# BaseBoard5.net
KiCad netlist of a schematic drawn in EAGLE
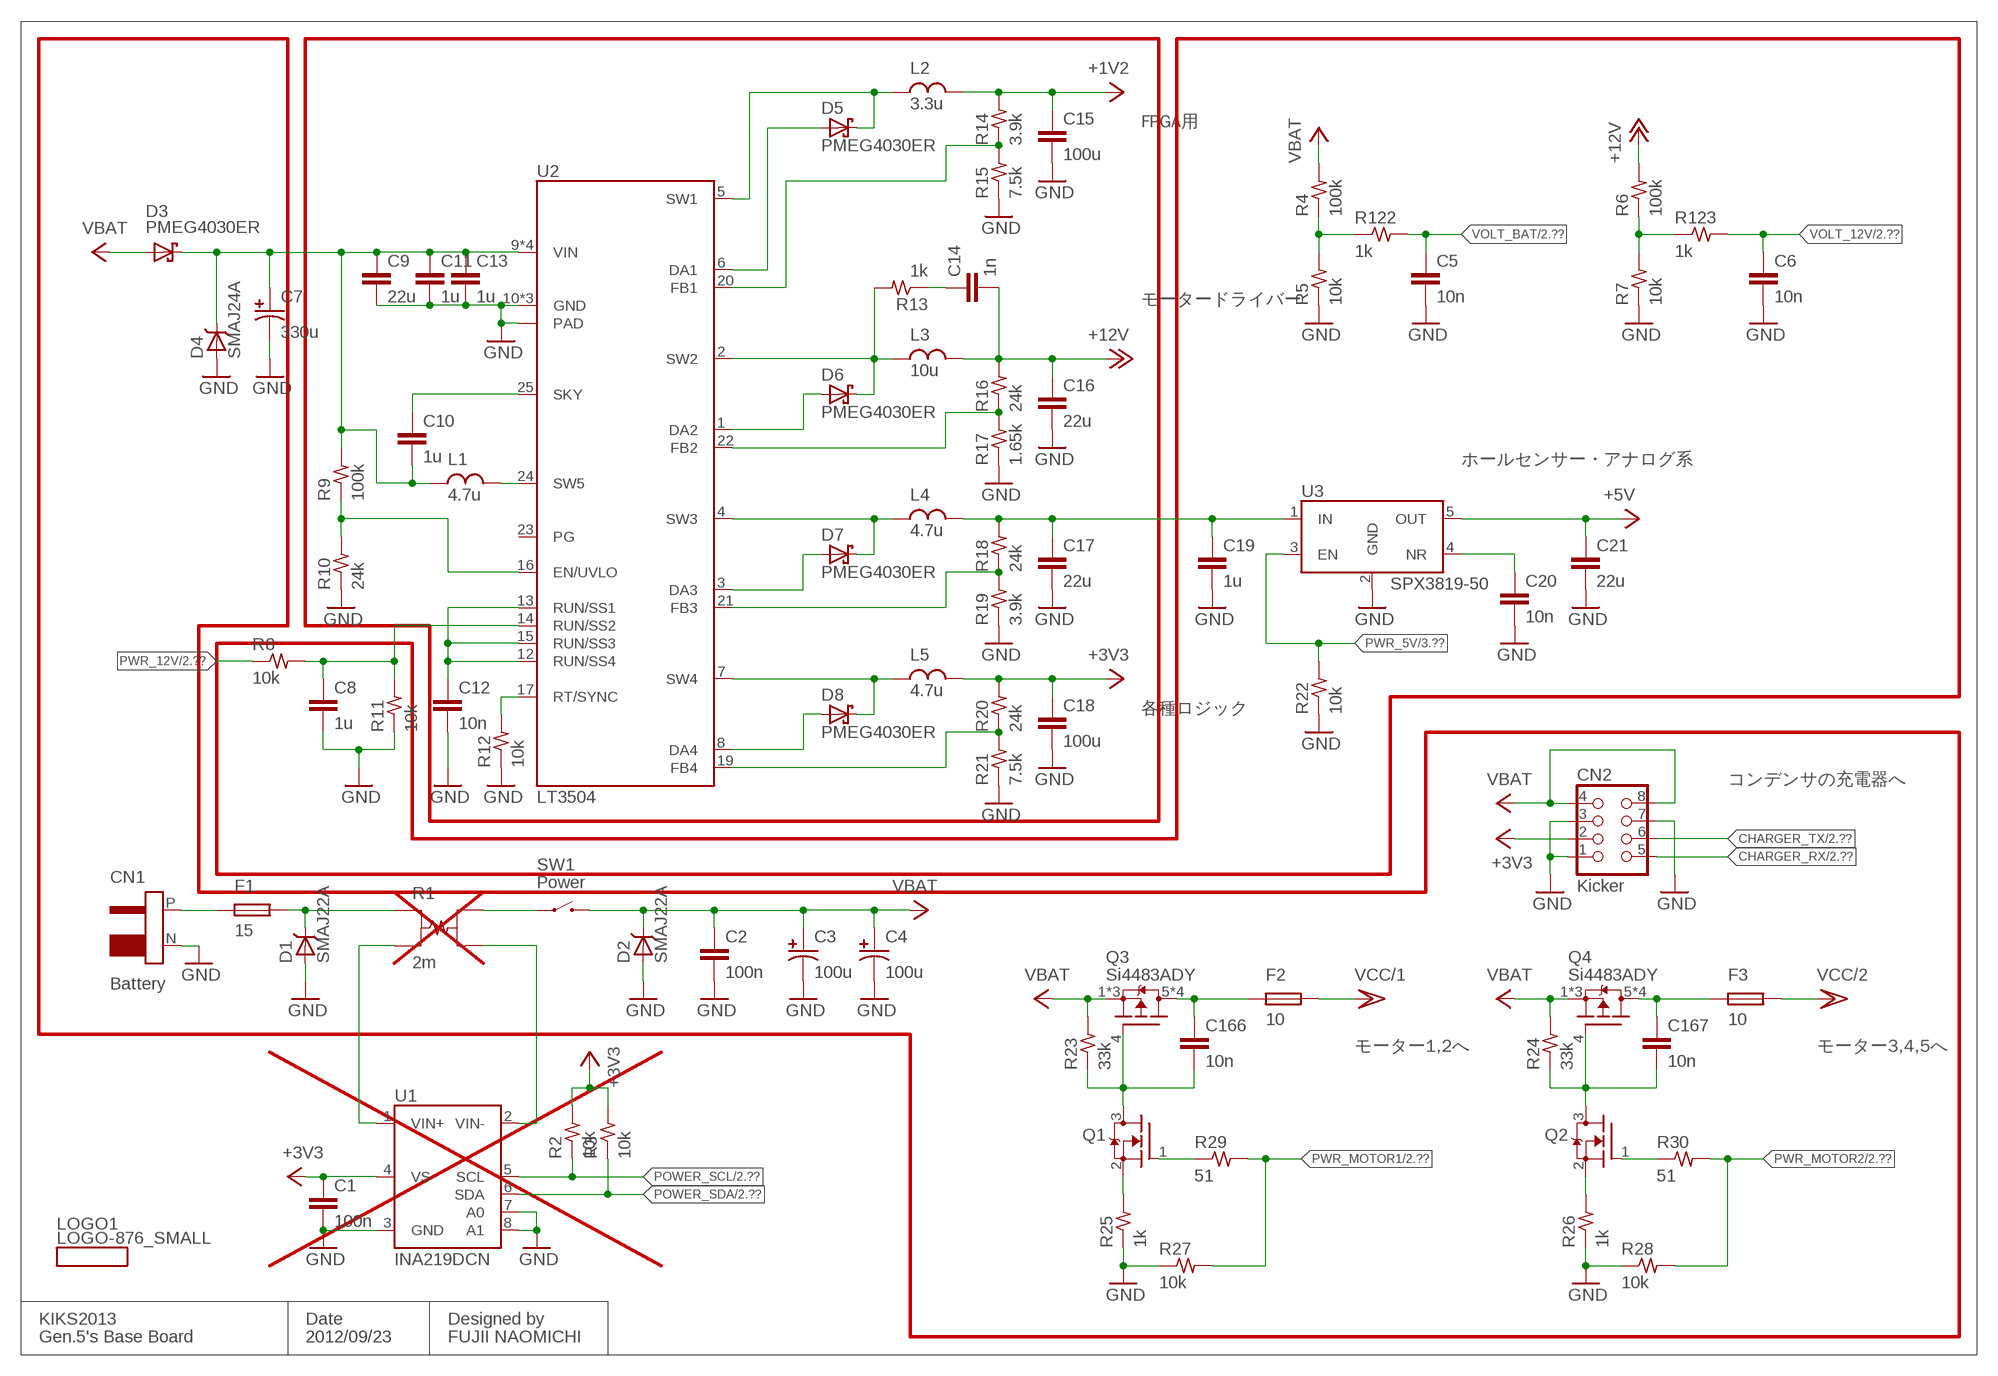
[diagram p0: schematic, sheet 1]
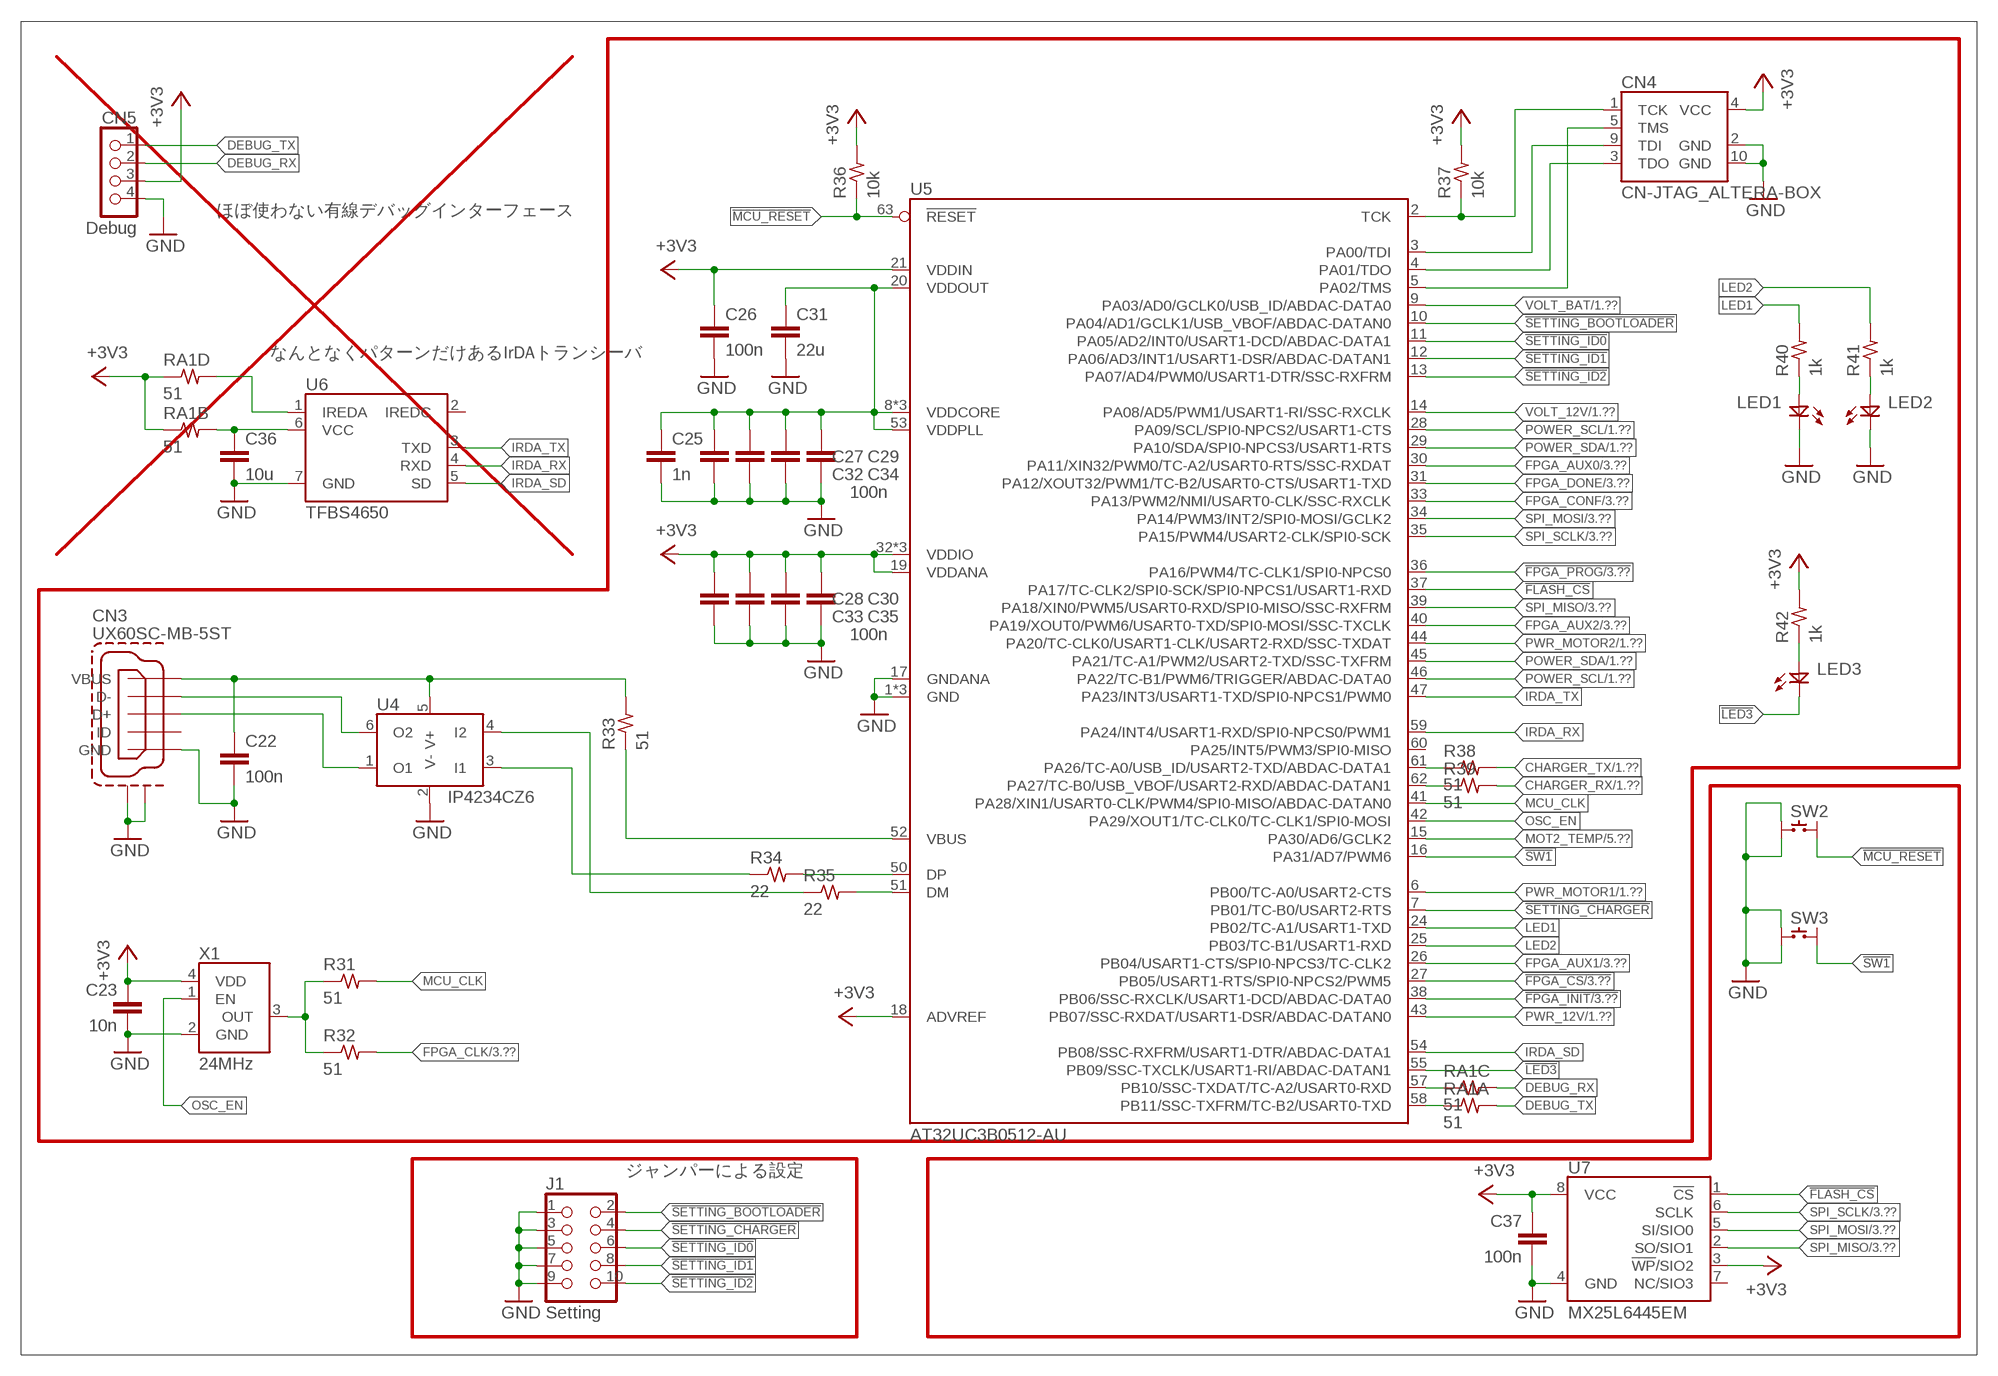
[diagram p1: schematic, sheet 2]
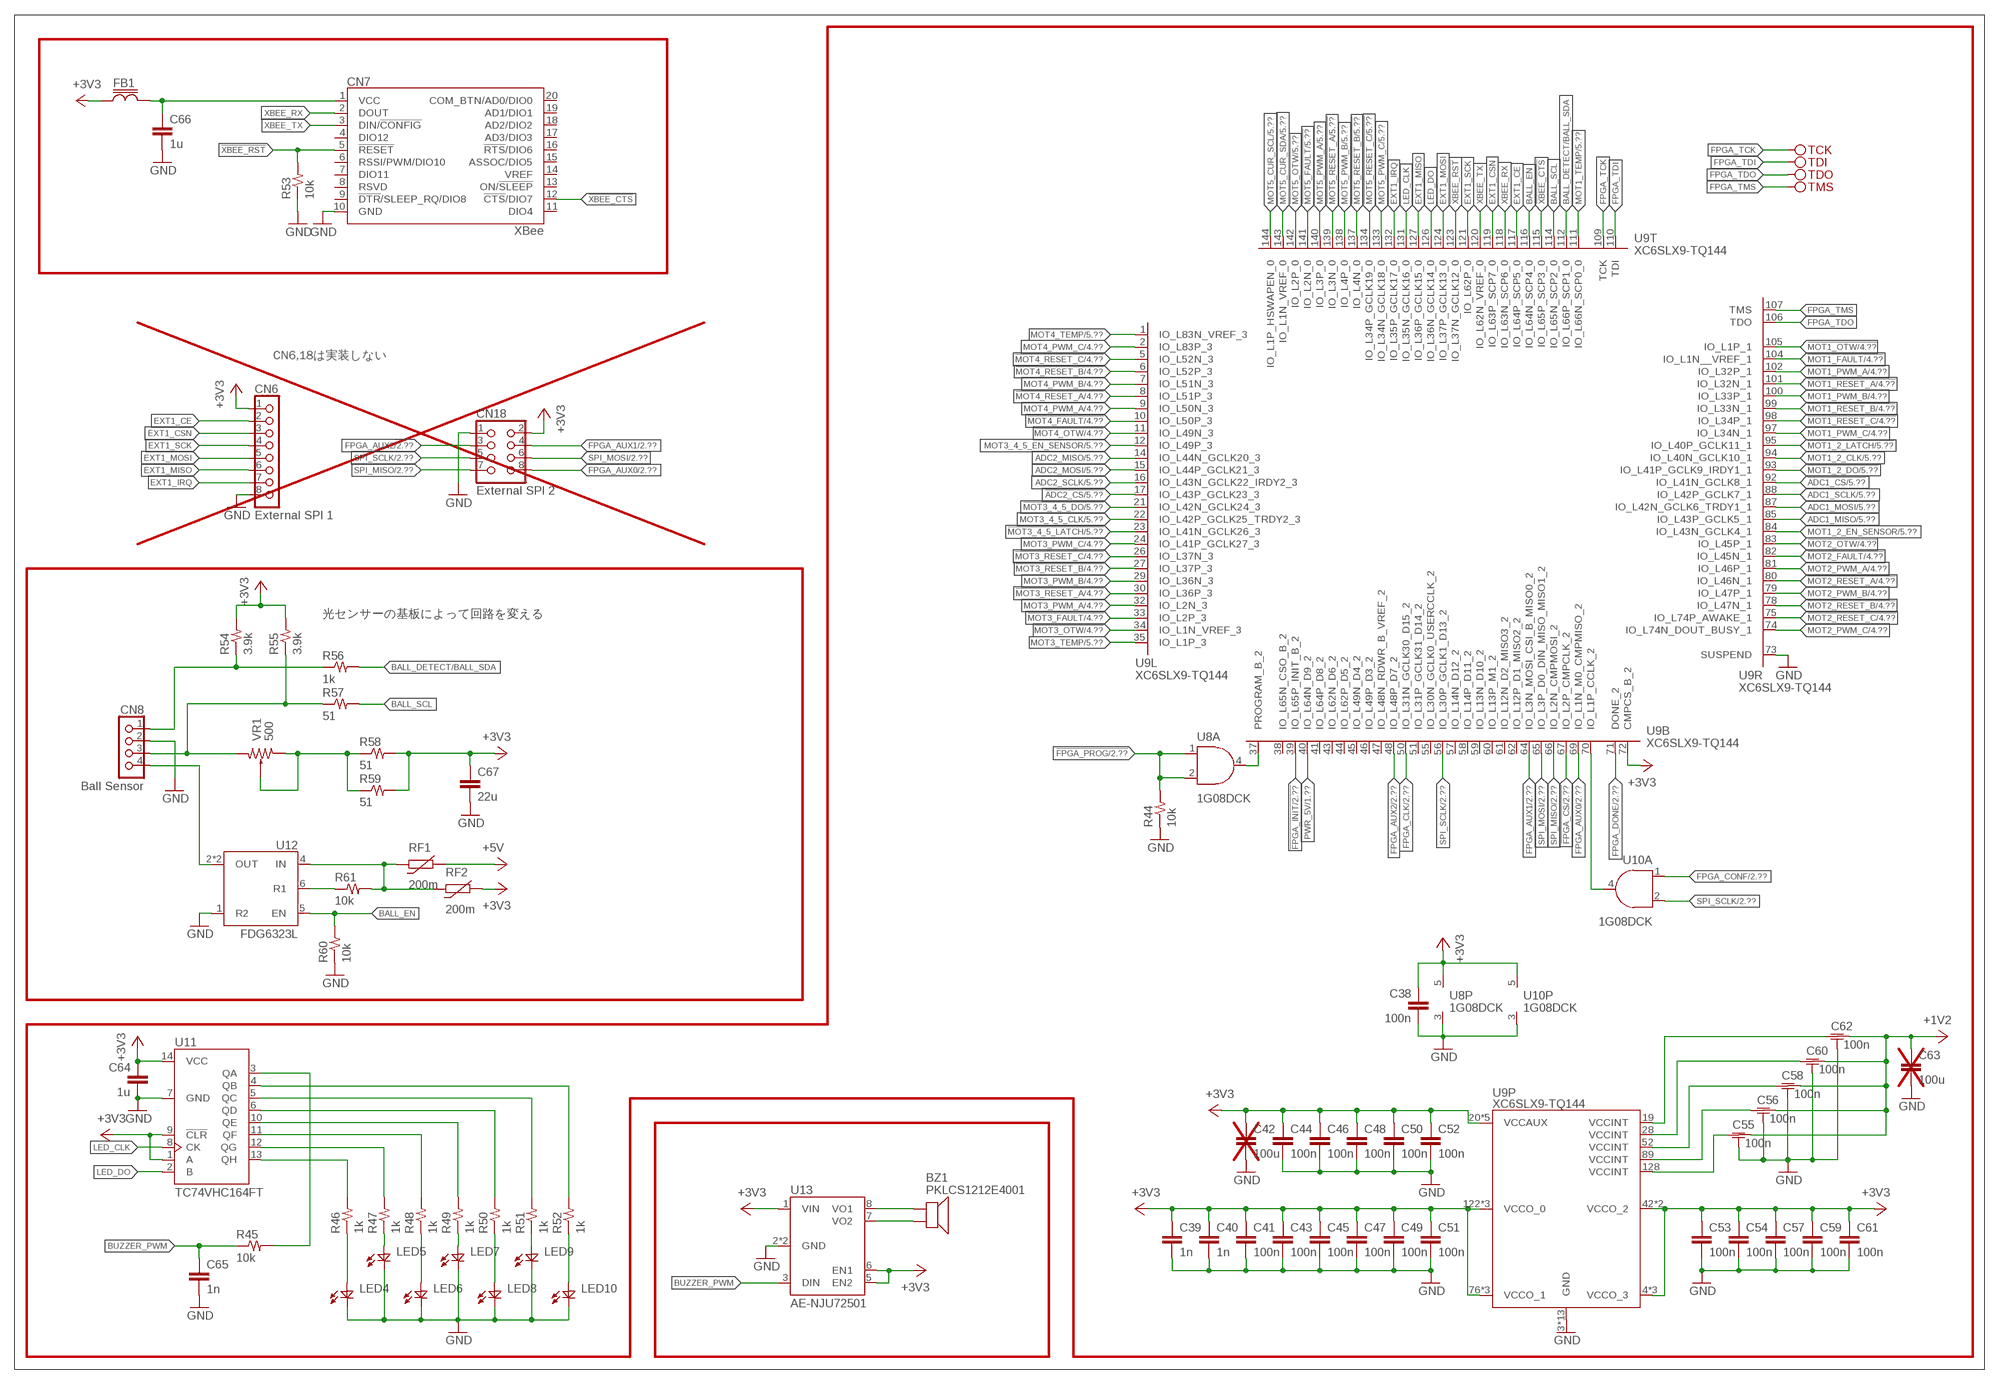
[diagram p2: schematic, sheet 3]
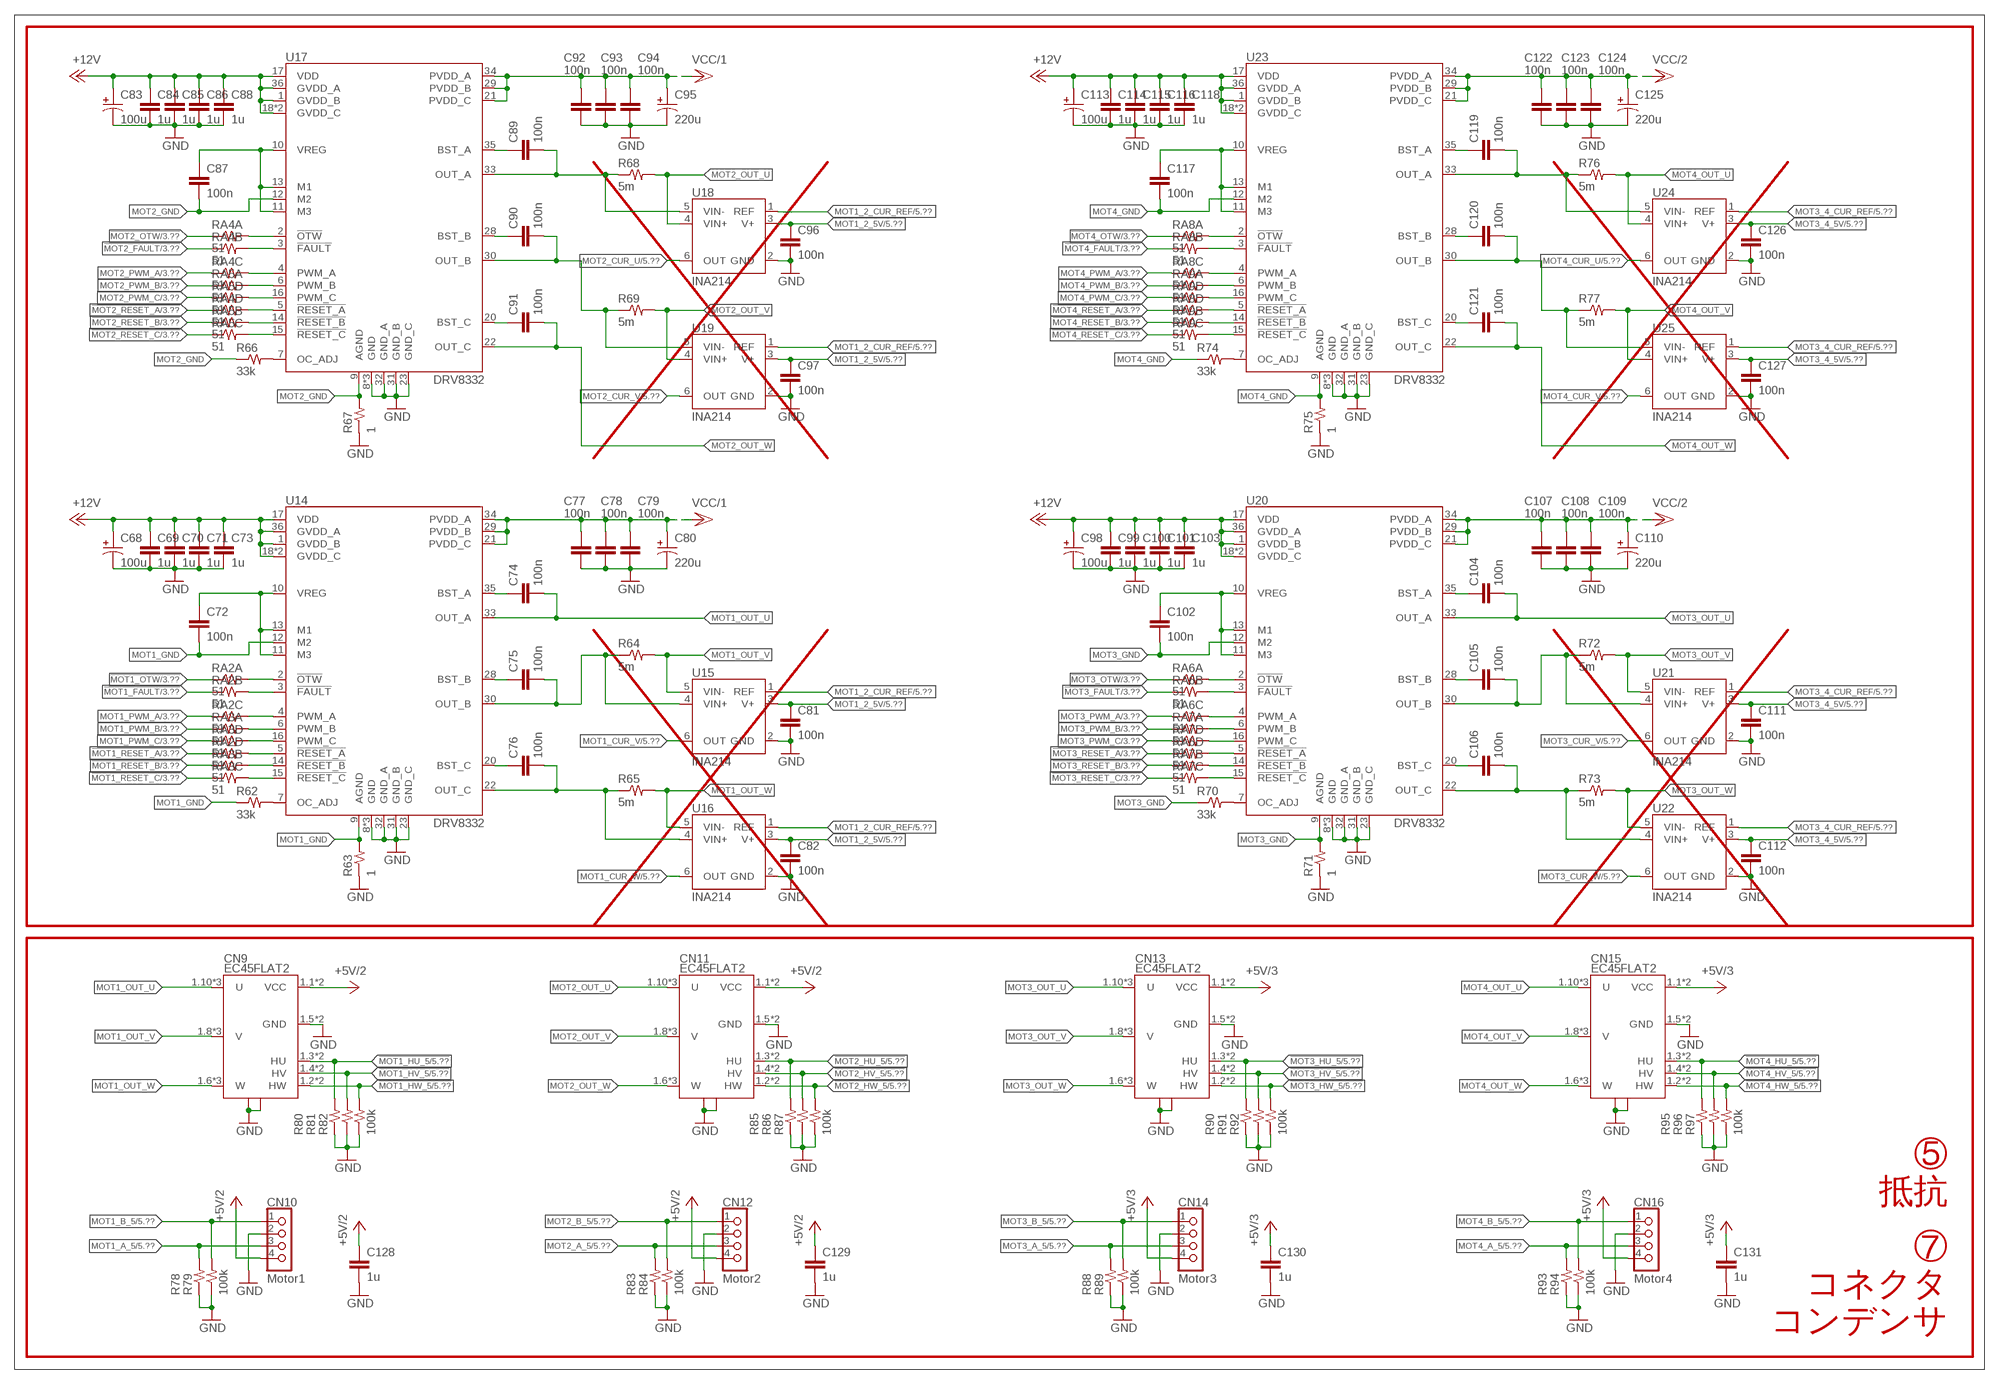
[diagram p3: schematic, sheet 4]
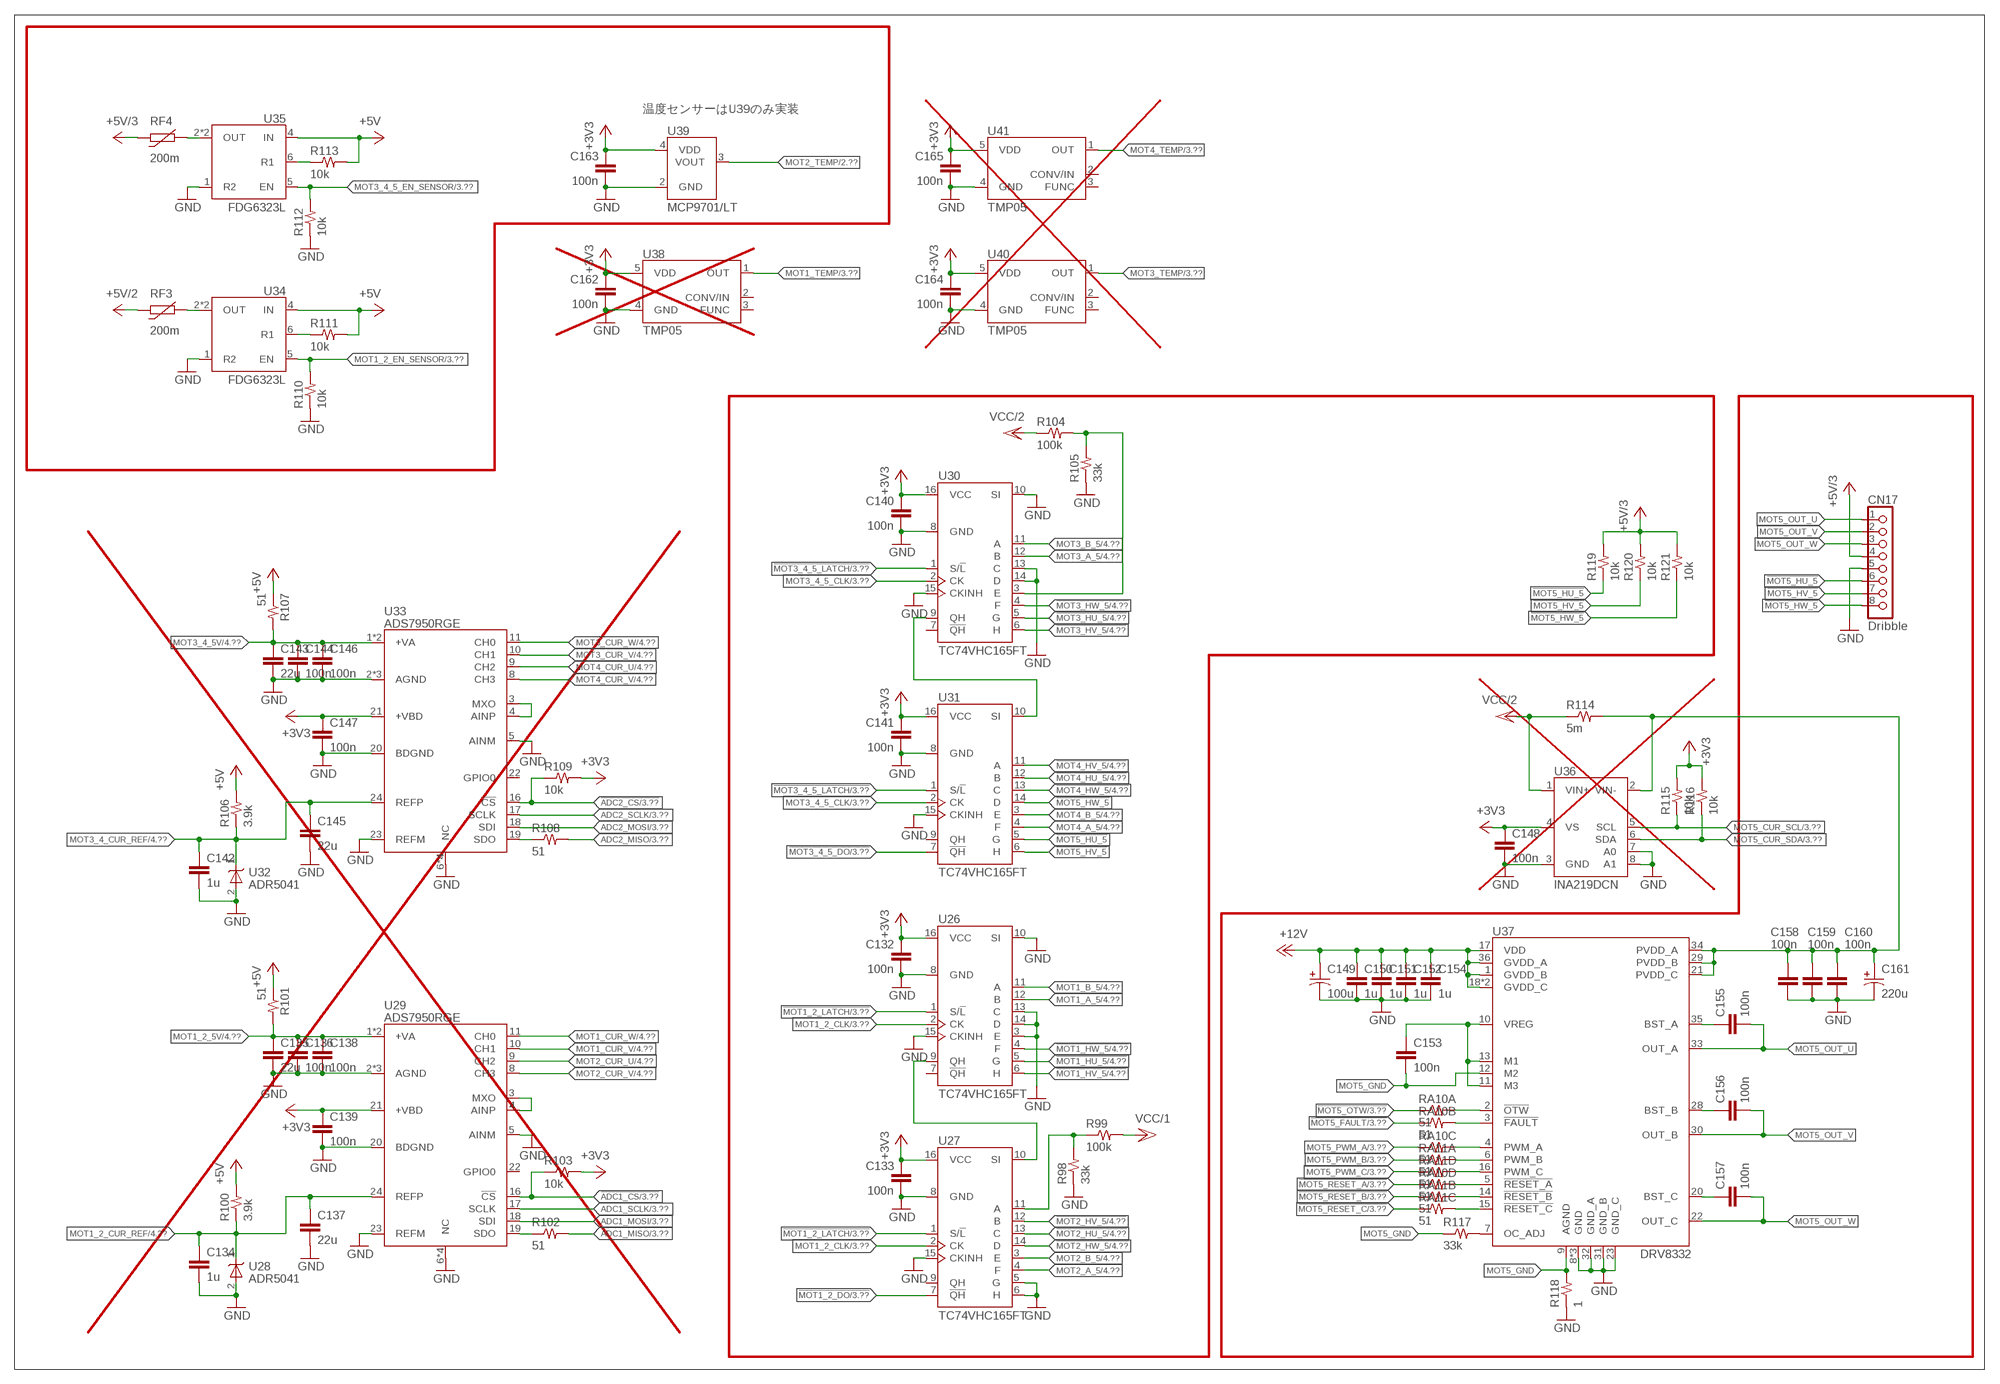
[diagram p4: schematic, sheet 5]

(export (version "E")
  (design (tool "Eeschema 10.0.6"))
  (components
    (comp (ref "C1")
      (value "100n")
      (footprint "eagle-import:1005")
      (libsource (lib "eagle-import") (part "C1005"))
    )
    (comp (ref "C2")
      (value "100n")
      (footprint "eagle-import:1608")
      (libsource (lib "eagle-import") (part "C1608"))
    )
    (comp (ref "C3")
      (value "100u")
      (footprint "eagle-import:ES-6.3")
      (libsource (lib "eagle-import") (part "CPOLS-6.3"))
    )
    (comp (ref "C4")
      (value "100u")
      (footprint "eagle-import:ES-6.3")
      (libsource (lib "eagle-import") (part "CPOLS-6.3"))
    )
    (comp (ref "C5")
      (value "10n")
      (footprint "eagle-import:1005")
      (libsource (lib "eagle-import") (part "C1005"))
    )
    (comp (ref "C6")
      (value "10n")
      (footprint "eagle-import:1005")
      (libsource (lib "eagle-import") (part "C1005"))
    )
    (comp (ref "C7")
      (value "330u")
      (footprint "eagle-import:ES2-8")
      (libsource (lib "eagle-import") (part "CPOLS2-8"))
    )
    (comp (ref "C8")
      (value "1u")
      (footprint "eagle-import:1005")
      (libsource (lib "eagle-import") (part "C1005"))
    )
    (comp (ref "C9")
      (value "22u")
      (footprint "eagle-import:3225")
      (libsource (lib "eagle-import") (part "C3225"))
    )
    (comp (ref "C10")
      (value "1u")
      (footprint "eagle-import:1608")
      (libsource (lib "eagle-import") (part "C1608"))
    )
    (comp (ref "C11")
      (value "1u")
      (footprint "eagle-import:1608")
      (libsource (lib "eagle-import") (part "C1608"))
    )
    (comp (ref "C12")
      (value "10n")
      (footprint "eagle-import:1005")
      (libsource (lib "eagle-import") (part "C1005"))
    )
    (comp (ref "C13")
      (value "1u")
      (footprint "eagle-import:1608")
      (libsource (lib "eagle-import") (part "C1608"))
    )
    (comp (ref "C14")
      (value "1n")
      (footprint "eagle-import:1005")
      (libsource (lib "eagle-import") (part "C1005"))
    )
    (comp (ref "C15")
      (value "100u")
      (footprint "eagle-import:3225")
      (libsource (lib "eagle-import") (part "C3225"))
    )
    (comp (ref "C16")
      (value "22u")
      (footprint "eagle-import:3225")
      (libsource (lib "eagle-import") (part "C3225"))
    )
    (comp (ref "C17")
      (value "22u")
      (footprint "eagle-import:3216")
      (libsource (lib "eagle-import") (part "C3216"))
    )
    (comp (ref "C18")
      (value "100u")
      (footprint "eagle-import:3225")
      (libsource (lib "eagle-import") (part "C3225"))
    )
    (comp (ref "C19")
      (value "1u")
      (footprint "eagle-import:1005")
      (libsource (lib "eagle-import") (part "C1005"))
    )
    (comp (ref "C20")
      (value "10n")
      (footprint "eagle-import:1005")
      (libsource (lib "eagle-import") (part "C1005"))
    )
    (comp (ref "C21")
      (value "22u")
      (footprint "eagle-import:3216")
      (libsource (lib "eagle-import") (part "C3216"))
    )
    (comp (ref "C166")
      (value "10n")
      (footprint "eagle-import:1005")
      (libsource (lib "eagle-import") (part "C1005"))
    )
    (comp (ref "C167")
      (value "10n")
      (footprint "eagle-import:1005")
      (libsource (lib "eagle-import") (part "C1005"))
    )
    (comp (ref "CN1")
      (value "Battery")
      (footprint "eagle-import:T-CON")
      (libsource (lib "eagle-import") (part "T-CON"))
    )
    (comp (ref "CN2")
      (value "Kicker")
      (footprint "eagle-import:43045-0800")
      (libsource (lib "eagle-import") (part "43045-0800"))
    )
    (comp (ref "D1")
      (value "SMAJ22A")
      (footprint "eagle-import:DO-214AC")
      (libsource (lib "eagle-import") (part "ZENER-DO-214AC"))
    )
    (comp (ref "D2")
      (value "SMAJ22A")
      (footprint "eagle-import:DO-214AC")
      (libsource (lib "eagle-import") (part "ZENER-DO-214AC"))
    )
    (comp (ref "D3")
      (value "PMEG4030ER")
      (footprint "eagle-import:SOD123W")
      (libsource (lib "eagle-import") (part "SBD-SDO123W"))
    )
    (comp (ref "D4")
      (value "SMAJ24A")
      (footprint "eagle-import:DO-214AC")
      (libsource (lib "eagle-import") (part "ZENER-DO-214AC"))
    )
    (comp (ref "D5")
      (value "PMEG4030ER")
      (footprint "eagle-import:SOD123W")
      (libsource (lib "eagle-import") (part "SBD-SDO123W"))
    )
    (comp (ref "D6")
      (value "PMEG4030ER")
      (footprint "eagle-import:SOD123W")
      (libsource (lib "eagle-import") (part "SBD-SDO123W"))
    )
    (comp (ref "D7")
      (value "PMEG4030ER")
      (footprint "eagle-import:SOD123W")
      (libsource (lib "eagle-import") (part "SBD-SDO123W"))
    )
    (comp (ref "D8")
      (value "PMEG4030ER")
      (footprint "eagle-import:SOD123W")
      (libsource (lib "eagle-import") (part "SBD-SDO123W"))
    )
    (comp (ref "F1")
      (value "15")
      (footprint "eagle-import:3216")
      (libsource (lib "eagle-import") (part "F3216"))
    )
    (comp (ref "F2")
      (value "10")
      (footprint "eagle-import:3216")
      (libsource (lib "eagle-import") (part "F3216"))
    )
    (comp (ref "F3")
      (value "10")
      (footprint "eagle-import:3216")
      (libsource (lib "eagle-import") (part "F3216"))
    )
    (comp (ref "L1")
      (value "4.7u")
      (footprint "eagle-import:L2520")
      (libsource (lib "eagle-import") (part "L2520"))
    )
    (comp (ref "L2")
      (value "3.3u")
      (footprint "eagle-import:L2520")
      (libsource (lib "eagle-import") (part "L2520"))
    )
    (comp (ref "L3")
      (value "10u")
      (footprint "eagle-import:L4040")
      (libsource (lib "eagle-import") (part "L40"))
    )
    (comp (ref "L4")
      (value "4.7u")
      (footprint "eagle-import:L2520")
      (libsource (lib "eagle-import") (part "L2520"))
    )
    (comp (ref "L5")
      (value "4.7u")
      (footprint "eagle-import:L2520")
      (libsource (lib "eagle-import") (part "L2520"))
    )
    (comp (ref "LOGO1")
      (value "LOGO-876_SMALL")
      (footprint "eagle-import:LOGO-876_SMALL")
      (libsource (lib "eagle-import") (part "LOGO-876_SMALL"))
    )
    (comp (ref "Q1")
      (value "MOS-N-SOT23")
      (footprint "eagle-import:SOT23-3")
      (libsource (lib "eagle-import") (part "MOS-N-SOT23"))
    )
    (comp (ref "Q2")
      (value "MOS-N-SOT23")
      (footprint "eagle-import:SOT23-3")
      (libsource (lib "eagle-import") (part "MOS-N-SOT23"))
    )
    (comp (ref "Q3")
      (value "Si4483ADY")
      (footprint "eagle-import:SOP8")
      (libsource (lib "eagle-import") (part "MOS-P-SOP8"))
    )
    (comp (ref "Q4")
      (value "Si4483ADY")
      (footprint "eagle-import:SOP8")
      (libsource (lib "eagle-import") (part "MOS-P-SOP8"))
    )
    (comp (ref "R1")
      (value "2m")
      (footprint "eagle-import:FC4L")
      (libsource (lib "eagle-import") (part "FC4L"))
    )
    (comp (ref "R2")
      (value "10k")
      (footprint "eagle-import:1005")
      (libsource (lib "eagle-import") (part "R1005"))
    )
    (comp (ref "R3")
      (value "10k")
      (footprint "eagle-import:1005")
      (libsource (lib "eagle-import") (part "R1005"))
    )
    (comp (ref "R4")
      (value "100k")
      (footprint "eagle-import:1608")
      (libsource (lib "eagle-import") (part "R1608"))
    )
    (comp (ref "R5")
      (value "10k")
      (footprint "eagle-import:1608")
      (libsource (lib "eagle-import") (part "R1608"))
    )
    (comp (ref "R6")
      (value "100k")
      (footprint "eagle-import:1608")
      (libsource (lib "eagle-import") (part "R1608"))
    )
    (comp (ref "R7")
      (value "10k")
      (footprint "eagle-import:1608")
      (libsource (lib "eagle-import") (part "R1608"))
    )
    (comp (ref "R8")
      (value "10k")
      (footprint "eagle-import:1005")
      (libsource (lib "eagle-import") (part "R1005"))
    )
    (comp (ref "R9")
      (value "100k")
      (footprint "eagle-import:1608")
      (libsource (lib "eagle-import") (part "R1608"))
    )
    (comp (ref "R10")
      (value "24k")
      (footprint "eagle-import:1608")
      (libsource (lib "eagle-import") (part "R1608"))
    )
    (comp (ref "R11")
      (value "10k")
      (footprint "eagle-import:1005")
      (libsource (lib "eagle-import") (part "R1005"))
    )
    (comp (ref "R12")
      (value "10k")
      (footprint "eagle-import:1005")
      (libsource (lib "eagle-import") (part "R1005"))
    )
    (comp (ref "R13")
      (value "1k")
      (footprint "eagle-import:1005")
      (libsource (lib "eagle-import") (part "R1005"))
    )
    (comp (ref "R14")
      (value "3.9k")
      (footprint "eagle-import:1608")
      (libsource (lib "eagle-import") (part "R1608"))
    )
    (comp (ref "R15")
      (value "7.5k")
      (footprint "eagle-import:1608")
      (libsource (lib "eagle-import") (part "R1608"))
    )
    (comp (ref "R16")
      (value "24k")
      (footprint "eagle-import:1608")
      (libsource (lib "eagle-import") (part "R1608"))
    )
    (comp (ref "R17")
      (value "1.65k")
      (footprint "eagle-import:1608")
      (libsource (lib "eagle-import") (part "R1608"))
    )
    (comp (ref "R18")
      (value "24k")
      (footprint "eagle-import:1608")
      (libsource (lib "eagle-import") (part "R1608"))
    )
    (comp (ref "R19")
      (value "3.9k")
      (footprint "eagle-import:1608")
      (libsource (lib "eagle-import") (part "R1608"))
    )
    (comp (ref "R20")
      (value "24k")
      (footprint "eagle-import:1608")
      (libsource (lib "eagle-import") (part "R1608"))
    )
    (comp (ref "R21")
      (value "7.5k")
      (footprint "eagle-import:1608")
      (libsource (lib "eagle-import") (part "R1608"))
    )
    (comp (ref "R22")
      (value "10k")
      (footprint "eagle-import:1005")
      (libsource (lib "eagle-import") (part "R1005"))
    )
    (comp (ref "R23")
      (value "33k")
      (footprint "eagle-import:1005")
      (libsource (lib "eagle-import") (part "R1005"))
    )
    (comp (ref "R24")
      (value "33k")
      (footprint "eagle-import:1005")
      (libsource (lib "eagle-import") (part "R1005"))
    )
    (comp (ref "R25")
      (value "1k")
      (footprint "eagle-import:1005")
      (libsource (lib "eagle-import") (part "R1005"))
    )
    (comp (ref "R26")
      (value "1k")
      (footprint "eagle-import:1005")
      (libsource (lib "eagle-import") (part "R1005"))
    )
    (comp (ref "R27")
      (value "10k")
      (footprint "eagle-import:1005")
      (libsource (lib "eagle-import") (part "R1005"))
    )
    (comp (ref "R28")
      (value "10k")
      (footprint "eagle-import:1005")
      (libsource (lib "eagle-import") (part "R1005"))
    )
    (comp (ref "R29")
      (value "51")
      (footprint "eagle-import:1005")
      (libsource (lib "eagle-import") (part "R1005"))
    )
    (comp (ref "R30")
      (value "51")
      (footprint "eagle-import:1005")
      (libsource (lib "eagle-import") (part "R1005"))
    )
    (comp (ref "R122")
      (value "1k")
      (footprint "eagle-import:1005")
      (libsource (lib "eagle-import") (part "R1005"))
    )
    (comp (ref "R123")
      (value "1k")
      (footprint "eagle-import:1005")
      (libsource (lib "eagle-import") (part "R1005"))
    )
    (comp (ref "SW1")
      (value "Power")
      (footprint "eagle-import:SLE6_10A4")
      (libsource (lib "eagle-import") (part "SLEA46"))
    )
    (comp (ref "U1")
      (value "INA219DCN")
      (footprint "eagle-import:SOT23-8")
      (libsource (lib "eagle-import") (part "INA219DCN"))
    )
    (comp (ref "U2")
      (value "LT3504")
      (footprint "eagle-import:QFN28-0.5-PAD")
      (libsource (lib "eagle-import") (part "LT3504"))
    )
    (comp (ref "U3")
      (value "SPX3819-50")
      (footprint "eagle-import:SOT23-5")
      (libsource (lib "eagle-import") (part "SPX3819-50"))
    )
    (comp (ref "C22")
      (value "100n")
      (footprint "eagle-import:1005")
      (libsource (lib "eagle-import") (part "C1005"))
    )
    (comp (ref "C23")
      (value "10n")
      (footprint "eagle-import:1005")
      (libsource (lib "eagle-import") (part "C1005"))
    )
    (comp (ref "C25")
      (value "1n")
      (footprint "eagle-import:1005")
      (libsource (lib "eagle-import") (part "C1005"))
    )
    (comp (ref "C26")
      (value "100n")
      (footprint "eagle-import:1005")
      (libsource (lib "eagle-import") (part "C1005"))
    )
    (comp (ref "C27")
      (value "100n")
      (footprint "eagle-import:1005")
      (libsource (lib "eagle-import") (part "C1005"))
    )
    (comp (ref "C28")
      (value "100n")
      (footprint "eagle-import:1005")
      (libsource (lib "eagle-import") (part "C1005"))
    )
    (comp (ref "C29")
      (value "100n")
      (footprint "eagle-import:1005")
      (libsource (lib "eagle-import") (part "C1005"))
    )
    (comp (ref "C30")
      (value "100n")
      (footprint "eagle-import:1005")
      (libsource (lib "eagle-import") (part "C1005"))
    )
    (comp (ref "C31")
      (value "22u")
      (footprint "eagle-import:2012")
      (libsource (lib "eagle-import") (part "C2012"))
    )
    (comp (ref "C32")
      (value "100n")
      (footprint "eagle-import:1005")
      (libsource (lib "eagle-import") (part "C1005"))
    )
    (comp (ref "C33")
      (value "100n")
      (footprint "eagle-import:1005")
      (libsource (lib "eagle-import") (part "C1005"))
    )
    (comp (ref "C34")
      (value "100n")
      (footprint "eagle-import:1005")
      (libsource (lib "eagle-import") (part "C1005"))
    )
    (comp (ref "C35")
      (value "100n")
      (footprint "eagle-import:1005")
      (libsource (lib "eagle-import") (part "C1005"))
    )
    (comp (ref "C36")
      (value "10u")
      (footprint "eagle-import:1608")
      (libsource (lib "eagle-import") (part "C1608"))
    )
    (comp (ref "C37")
      (value "100n")
      (footprint "eagle-import:1005")
      (libsource (lib "eagle-import") (part "C1005"))
    )
    (comp (ref "CN3")
      (value "UX60SC-MB-5ST")
      (footprint "eagle-import:UX60SC-MB-5ST")
      (libsource (lib "eagle-import") (part "UX60SC-MB-5ST"))
    )
    (comp (ref "CN4")
      (value "CN-JTAG_ALTERA-BOX")
      (footprint "eagle-import:PIN2X5-BOX")
      (libsource (lib "eagle-import") (part "CN-JTAG_ALTERA-BOX"))
    )
    (comp (ref "CN5")
      (value "Debug")
      (footprint "eagle-import:70553-0003")
      (libsource (lib "eagle-import") (part "70553-0003"))
    )
    (comp (ref "J1")
      (value "Setting")
      (footprint "eagle-import:PIN2X5-2.0")
      (libsource (lib "eagle-import") (part "PIN2X5-2.0"))
    )
    (comp (ref "LED1")
      (value "LED1608")
      (footprint "eagle-import:1608")
      (libsource (lib "eagle-import") (part "LED1608"))
    )
    (comp (ref "LED2")
      (value "LED1608")
      (footprint "eagle-import:1608")
      (libsource (lib "eagle-import") (part "LED1608"))
    )
    (comp (ref "LED3")
      (value "LED1608")
      (footprint "eagle-import:1608")
      (libsource (lib "eagle-import") (part "LED1608"))
    )
    (comp (ref "R31")
      (value "51")
      (footprint "eagle-import:1005")
      (libsource (lib "eagle-import") (part "R1005"))
    )
    (comp (ref "R32")
      (value "51")
      (footprint "eagle-import:1005")
      (libsource (lib "eagle-import") (part "R1005"))
    )
    (comp (ref "R33")
      (value "51")
      (footprint "eagle-import:1005")
      (libsource (lib "eagle-import") (part "R1005"))
    )
    (comp (ref "R34")
      (value "22")
      (footprint "eagle-import:1005")
      (libsource (lib "eagle-import") (part "R1005"))
    )
    (comp (ref "R35")
      (value "22")
      (footprint "eagle-import:1005")
      (libsource (lib "eagle-import") (part "R1005"))
    )
    (comp (ref "R36")
      (value "10k")
      (footprint "eagle-import:1005")
      (libsource (lib "eagle-import") (part "R1005"))
    )
    (comp (ref "R37")
      (value "10k")
      (footprint "eagle-import:1005")
      (libsource (lib "eagle-import") (part "R1005"))
    )
    (comp (ref "R38")
      (value "51")
      (footprint "eagle-import:1005")
      (libsource (lib "eagle-import") (part "R1005"))
    )
    (comp (ref "R39")
      (value "51")
      (footprint "eagle-import:1005")
      (libsource (lib "eagle-import") (part "R1005"))
    )
    (comp (ref "R40")
      (value "1k")
      (footprint "eagle-import:1005")
      (libsource (lib "eagle-import") (part "R1005"))
    )
    (comp (ref "R41")
      (value "1k")
      (footprint "eagle-import:1005")
      (libsource (lib "eagle-import") (part "R1005"))
    )
    (comp (ref "R42")
      (value "1k")
      (footprint "eagle-import:1005")
      (libsource (lib "eagle-import") (part "R1005"))
    )
    (comp (ref "RA1")
      (value "51")
      (footprint "eagle-import:1005-A4")
      (libsource (lib "eagle-import") (part "RA4"))
    )
    (comp (ref "SW2")
      (value "EVQ-P2-RECTANGLE")
      (footprint "eagle-import:EVQ-P2_P9")
      (libsource (lib "eagle-import") (part "EVQ-?P2-RECTANGLE"))
    )
    (comp (ref "SW3")
      (value "EVQ-P2-RECTANGLE")
      (footprint "eagle-import:EVQ-P2_P9")
      (libsource (lib "eagle-import") (part "EVQ-?P2-RECTANGLE"))
    )
    (comp (ref "U4")
      (value "IP4234CZ6")
      (footprint "eagle-import:SOT23-6")
      (libsource (lib "eagle-import") (part "TPD2S017"))
    )
    (comp (ref "U5")
      (value "AT32UC3B0512-AU")
      (footprint "eagle-import:QFP64-0.5")
      (libsource (lib "eagle-import") (part "AT32UC3B0512-AU"))
    )
    (comp (ref "U6")
      (value "TFBS4650")
      (footprint "eagle-import:TFBS4650")
      (libsource (lib "eagle-import") (part "TFBS4650"))
    )
    (comp (ref "U7")
      (value "MX25L6445EM")
      (footprint "eagle-import:SOP8W")
      (libsource (lib "eagle-import") (part "MX25L6445EM"))
    )
    (comp (ref "X1")
      (value "24MHz")
      (footprint "eagle-import:OSC2520")
      (libsource (lib "eagle-import") (part "ASDMB"))
    )
    (comp (ref "C68")
      (value "100u")
      (footprint "eagle-import:E2.5-6.3")
      (libsource (lib "eagle-import") (part "CPOL2.5-6.3"))
    )
    (comp (ref "C69")
      (value "1u")
      (footprint "eagle-import:1608")
      (libsource (lib "eagle-import") (part "C1608"))
    )
    (comp (ref "C70")
      (value "1u")
      (footprint "eagle-import:1608")
      (libsource (lib "eagle-import") (part "C1608"))
    )
    (comp (ref "C71")
      (value "1u")
      (footprint "eagle-import:1608")
      (libsource (lib "eagle-import") (part "C1608"))
    )
    (comp (ref "C72")
      (value "100n")
      (footprint "eagle-import:1005")
      (libsource (lib "eagle-import") (part "C1005"))
    )
    (comp (ref "C73")
      (value "1u")
      (footprint "eagle-import:1608")
      (libsource (lib "eagle-import") (part "C1608"))
    )
    (comp (ref "C74")
      (value "100n")
      (footprint "eagle-import:1608")
      (libsource (lib "eagle-import") (part "C1608"))
    )
    (comp (ref "C75")
      (value "100n")
      (footprint "eagle-import:1608")
      (libsource (lib "eagle-import") (part "C1608"))
    )
    (comp (ref "C76")
      (value "100n")
      (footprint "eagle-import:1608")
      (libsource (lib "eagle-import") (part "C1608"))
    )
    (comp (ref "C77")
      (value "100n")
      (footprint "eagle-import:1608")
      (libsource (lib "eagle-import") (part "C1608"))
    )
    (comp (ref "C78")
      (value "100n")
      (footprint "eagle-import:1608")
      (libsource (lib "eagle-import") (part "C1608"))
    )
    (comp (ref "C79")
      (value "100n")
      (footprint "eagle-import:1608")
      (libsource (lib "eagle-import") (part "C1608"))
    )
    (comp (ref "C80")
      (value "220u")
      (footprint "eagle-import:E3.5-8")
      (libsource (lib "eagle-import") (part "CPOL3.5-8"))
    )
    (comp (ref "C81")
      (value "100n")
      (footprint "eagle-import:1005")
      (libsource (lib "eagle-import") (part "C1005"))
    )
    (comp (ref "C82")
      (value "100n")
      (footprint "eagle-import:1005")
      (libsource (lib "eagle-import") (part "C1005"))
    )
    (comp (ref "C83")
      (value "100u")
      (footprint "eagle-import:E2.5-6.3")
      (libsource (lib "eagle-import") (part "CPOL2.5-6.3"))
    )
    (comp (ref "C84")
      (value "1u")
      (footprint "eagle-import:1608")
      (libsource (lib "eagle-import") (part "C1608"))
    )
    (comp (ref "C85")
      (value "1u")
      (footprint "eagle-import:1608")
      (libsource (lib "eagle-import") (part "C1608"))
    )
    (comp (ref "C86")
      (value "1u")
      (footprint "eagle-import:1608")
      (libsource (lib "eagle-import") (part "C1608"))
    )
    (comp (ref "C87")
      (value "100n")
      (footprint "eagle-import:1005")
      (libsource (lib "eagle-import") (part "C1005"))
    )
    (comp (ref "C88")
      (value "1u")
      (footprint "eagle-import:1608")
      (libsource (lib "eagle-import") (part "C1608"))
    )
    (comp (ref "C89")
      (value "100n")
      (footprint "eagle-import:1608")
      (libsource (lib "eagle-import") (part "C1608"))
    )
    (comp (ref "C90")
      (value "100n")
      (footprint "eagle-import:1608")
      (libsource (lib "eagle-import") (part "C1608"))
    )
    (comp (ref "C91")
      (value "100n")
      (footprint "eagle-import:1608")
      (libsource (lib "eagle-import") (part "C1608"))
    )
    (comp (ref "C92")
      (value "100n")
      (footprint "eagle-import:1608")
      (libsource (lib "eagle-import") (part "C1608"))
    )
    (comp (ref "C93")
      (value "100n")
      (footprint "eagle-import:1608")
      (libsource (lib "eagle-import") (part "C1608"))
    )
    (comp (ref "C94")
      (value "100n")
      (footprint "eagle-import:1608")
      (libsource (lib "eagle-import") (part "C1608"))
    )
    (comp (ref "C95")
      (value "220u")
      (footprint "eagle-import:E3.5-8")
      (libsource (lib "eagle-import") (part "CPOL3.5-8"))
    )
    (comp (ref "C96")
      (value "100n")
      (footprint "eagle-import:1005")
      (libsource (lib "eagle-import") (part "C1005"))
    )
    (comp (ref "C97")
      (value "100n")
      (footprint "eagle-import:1005")
      (libsource (lib "eagle-import") (part "C1005"))
    )
    (comp (ref "C98")
      (value "100u")
      (footprint "eagle-import:E2.5-6.3")
      (libsource (lib "eagle-import") (part "CPOL2.5-6.3"))
    )
    (comp (ref "C99")
      (value "1u")
      (footprint "eagle-import:1608")
      (libsource (lib "eagle-import") (part "C1608"))
    )
    (comp (ref "C100")
      (value "1u")
      (footprint "eagle-import:1608")
      (libsource (lib "eagle-import") (part "C1608"))
    )
    (comp (ref "C101")
      (value "1u")
      (footprint "eagle-import:1608")
      (libsource (lib "eagle-import") (part "C1608"))
    )
    (comp (ref "C102")
      (value "100n")
      (footprint "eagle-import:1005")
      (libsource (lib "eagle-import") (part "C1005"))
    )
    (comp (ref "C103")
      (value "1u")
      (footprint "eagle-import:1608")
      (libsource (lib "eagle-import") (part "C1608"))
    )
    (comp (ref "C104")
      (value "100n")
      (footprint "eagle-import:1608")
      (libsource (lib "eagle-import") (part "C1608"))
    )
    (comp (ref "C105")
      (value "100n")
      (footprint "eagle-import:1608")
      (libsource (lib "eagle-import") (part "C1608"))
    )
    (comp (ref "C106")
      (value "100n")
      (footprint "eagle-import:1608")
      (libsource (lib "eagle-import") (part "C1608"))
    )
    (comp (ref "C107")
      (value "100n")
      (footprint "eagle-import:1608")
      (libsource (lib "eagle-import") (part "C1608"))
    )
    (comp (ref "C108")
      (value "100n")
      (footprint "eagle-import:1608")
      (libsource (lib "eagle-import") (part "C1608"))
    )
    (comp (ref "C109")
      (value "100n")
      (footprint "eagle-import:1608")
      (libsource (lib "eagle-import") (part "C1608"))
    )
    (comp (ref "C110")
      (value "220u")
      (footprint "eagle-import:E3.5-8")
      (libsource (lib "eagle-import") (part "CPOL3.5-8"))
    )
    (comp (ref "C111")
      (value "100n")
      (footprint "eagle-import:1005")
      (libsource (lib "eagle-import") (part "C1005"))
    )
    (comp (ref "C112")
      (value "100n")
      (footprint "eagle-import:1005")
      (libsource (lib "eagle-import") (part "C1005"))
    )
    (comp (ref "C113")
      (value "100u")
      (footprint "eagle-import:E2.5-6.3")
      (libsource (lib "eagle-import") (part "CPOL2.5-6.3"))
    )
    (comp (ref "C114")
      (value "1u")
      (footprint "eagle-import:1608")
      (libsource (lib "eagle-import") (part "C1608"))
    )
    (comp (ref "C115")
      (value "1u")
      (footprint "eagle-import:1608")
      (libsource (lib "eagle-import") (part "C1608"))
    )
    (comp (ref "C116")
      (value "1u")
      (footprint "eagle-import:1608")
      (libsource (lib "eagle-import") (part "C1608"))
    )
    (comp (ref "C117")
      (value "100n")
      (footprint "eagle-import:1005")
      (libsource (lib "eagle-import") (part "C1005"))
    )
    (comp (ref "C118")
      (value "1u")
      (footprint "eagle-import:1608")
      (libsource (lib "eagle-import") (part "C1608"))
    )
    (comp (ref "C119")
      (value "100n")
      (footprint "eagle-import:1608")
      (libsource (lib "eagle-import") (part "C1608"))
    )
    (comp (ref "C120")
      (value "100n")
      (footprint "eagle-import:1608")
      (libsource (lib "eagle-import") (part "C1608"))
    )
    (comp (ref "C121")
      (value "100n")
      (footprint "eagle-import:1608")
      (libsource (lib "eagle-import") (part "C1608"))
    )
    (comp (ref "C122")
      (value "100n")
      (footprint "eagle-import:1608")
      (libsource (lib "eagle-import") (part "C1608"))
    )
    (comp (ref "C123")
      (value "100n")
      (footprint "eagle-import:1608")
      (libsource (lib "eagle-import") (part "C1608"))
    )
    (comp (ref "C124")
      (value "100n")
      (footprint "eagle-import:1608")
      (libsource (lib "eagle-import") (part "C1608"))
    )
    (comp (ref "C125")
      (value "220u")
      (footprint "eagle-import:E3.5-8")
      (libsource (lib "eagle-import") (part "CPOL3.5-8"))
    )
    (comp (ref "C126")
      (value "100n")
      (footprint "eagle-import:1005")
      (libsource (lib "eagle-import") (part "C1005"))
    )
    (comp (ref "C127")
      (value "100n")
      (footprint "eagle-import:1005")
      (libsource (lib "eagle-import") (part "C1005"))
    )
    (comp (ref "C128")
      (value "1u")
      (footprint "eagle-import:1005")
      (libsource (lib "eagle-import") (part "C1005"))
    )
    (comp (ref "C129")
      (value "1u")
      (footprint "eagle-import:1005")
      (libsource (lib "eagle-import") (part "C1005"))
    )
    (comp (ref "C130")
      (value "1u")
      (footprint "eagle-import:1005")
      (libsource (lib "eagle-import") (part "C1005"))
    )
    (comp (ref "C131")
      (value "1u")
      (footprint "eagle-import:1005")
      (libsource (lib "eagle-import") (part "C1005"))
    )
    (comp (ref "CN9")
      (value "EC45FLAT2")
      (footprint "eagle-import:MOTOR_COMPLEX2")
      (libsource (lib "eagle-import") (part "EC45FLAT2"))
    )
    (comp (ref "CN10")
      (value "Motor1")
      (footprint "eagle-import:53375-04")
      (libsource (lib "eagle-import") (part "53375-0410"))
    )
    (comp (ref "CN11")
      (value "EC45FLAT2")
      (footprint "eagle-import:MOTOR_COMPLEX2")
      (libsource (lib "eagle-import") (part "EC45FLAT2"))
    )
    (comp (ref "CN12")
      (value "Motor2")
      (footprint "eagle-import:53375-04")
      (libsource (lib "eagle-import") (part "53375-0410"))
    )
    (comp (ref "CN13")
      (value "EC45FLAT2")
      (footprint "eagle-import:MOTOR_COMPLEX2")
      (libsource (lib "eagle-import") (part "EC45FLAT2"))
    )
    (comp (ref "CN14")
      (value "Motor3")
      (footprint "eagle-import:53375-04")
      (libsource (lib "eagle-import") (part "53375-0410"))
    )
    (comp (ref "CN15")
      (value "EC45FLAT2")
      (footprint "eagle-import:MOTOR_COMPLEX2")
      (libsource (lib "eagle-import") (part "EC45FLAT2"))
    )
    (comp (ref "CN16")
      (value "Motor4")
      (footprint "eagle-import:53375-04")
      (libsource (lib "eagle-import") (part "53375-0410"))
    )
    (comp (ref "R62")
      (value "33k")
      (footprint "eagle-import:1608")
      (libsource (lib "eagle-import") (part "R1608"))
    )
    (comp (ref "R63")
      (value "1")
      (footprint "eagle-import:1005")
      (libsource (lib "eagle-import") (part "R1005"))
    )
    (comp (ref "R64")
      (value "5m")
      (footprint "eagle-import:3216")
      (libsource (lib "eagle-import") (part "R3216"))
    )
    (comp (ref "R65")
      (value "5m")
      (footprint "eagle-import:3216")
      (libsource (lib "eagle-import") (part "R3216"))
    )
    (comp (ref "R66")
      (value "33k")
      (footprint "eagle-import:1608")
      (libsource (lib "eagle-import") (part "R1608"))
    )
    (comp (ref "R67")
      (value "1")
      (footprint "eagle-import:1005")
      (libsource (lib "eagle-import") (part "R1005"))
    )
    (comp (ref "R68")
      (value "5m")
      (footprint "eagle-import:3216")
      (libsource (lib "eagle-import") (part "R3216"))
    )
    (comp (ref "R69")
      (value "5m")
      (footprint "eagle-import:3216")
      (libsource (lib "eagle-import") (part "R3216"))
    )
    (comp (ref "R70")
      (value "33k")
      (footprint "eagle-import:1608")
      (libsource (lib "eagle-import") (part "R1608"))
    )
    (comp (ref "R71")
      (value "1")
      (footprint "eagle-import:1005")
      (libsource (lib "eagle-import") (part "R1005"))
    )
    (comp (ref "R72")
      (value "5m")
      (footprint "eagle-import:3216")
      (libsource (lib "eagle-import") (part "R3216"))
    )
    (comp (ref "R73")
      (value "5m")
      (footprint "eagle-import:3216")
      (libsource (lib "eagle-import") (part "R3216"))
    )
    (comp (ref "R74")
      (value "33k")
      (footprint "eagle-import:1608")
      (libsource (lib "eagle-import") (part "R1608"))
    )
    (comp (ref "R75")
      (value "1")
      (footprint "eagle-import:1005")
      (libsource (lib "eagle-import") (part "R1005"))
    )
    (comp (ref "R76")
      (value "5m")
      (footprint "eagle-import:3216")
      (libsource (lib "eagle-import") (part "R3216"))
    )
    (comp (ref "R77")
      (value "5m")
      (footprint "eagle-import:3216")
      (libsource (lib "eagle-import") (part "R3216"))
    )
    (comp (ref "R78")
      (value "100k")
      (footprint "eagle-import:1005")
      (libsource (lib "eagle-import") (part "R1005"))
    )
    (comp (ref "R79")
      (value "100k")
      (footprint "eagle-import:1005")
      (libsource (lib "eagle-import") (part "R1005"))
    )
    (comp (ref "R80")
      (value "100k")
      (footprint "eagle-import:1005")
      (libsource (lib "eagle-import") (part "R1005"))
    )
    (comp (ref "R81")
      (value "100k")
      (footprint "eagle-import:1005")
      (libsource (lib "eagle-import") (part "R1005"))
    )
    (comp (ref "R82")
      (value "100k")
      (footprint "eagle-import:1005")
      (libsource (lib "eagle-import") (part "R1005"))
    )
    (comp (ref "R83")
      (value "100k")
      (footprint "eagle-import:1005")
      (libsource (lib "eagle-import") (part "R1005"))
    )
    (comp (ref "R84")
      (value "100k")
      (footprint "eagle-import:1005")
      (libsource (lib "eagle-import") (part "R1005"))
    )
    (comp (ref "R85")
      (value "100k")
      (footprint "eagle-import:1005")
      (libsource (lib "eagle-import") (part "R1005"))
    )
    (comp (ref "R86")
      (value "100k")
      (footprint "eagle-import:1005")
      (libsource (lib "eagle-import") (part "R1005"))
    )
    (comp (ref "R87")
      (value "100k")
      (footprint "eagle-import:1005")
      (libsource (lib "eagle-import") (part "R1005"))
    )
    (comp (ref "R88")
      (value "100k")
      (footprint "eagle-import:1005")
      (libsource (lib "eagle-import") (part "R1005"))
    )
    (comp (ref "R89")
      (value "100k")
      (footprint "eagle-import:1005")
      (libsource (lib "eagle-import") (part "R1005"))
    )
    (comp (ref "R90")
      (value "100k")
      (footprint "eagle-import:1005")
      (libsource (lib "eagle-import") (part "R1005"))
    )
    (comp (ref "R91")
      (value "100k")
      (footprint "eagle-import:1005")
      (libsource (lib "eagle-import") (part "R1005"))
    )
    (comp (ref "R92")
      (value "100k")
      (footprint "eagle-import:1005")
      (libsource (lib "eagle-import") (part "R1005"))
    )
    (comp (ref "R93")
      (value "100k")
      (footprint "eagle-import:1005")
      (libsource (lib "eagle-import") (part "R1005"))
    )
    (comp (ref "R94")
      (value "100k")
      (footprint "eagle-import:1005")
      (libsource (lib "eagle-import") (part "R1005"))
    )
    (comp (ref "R95")
      (value "100k")
      (footprint "eagle-import:1005")
      (libsource (lib "eagle-import") (part "R1005"))
    )
    (comp (ref "R96")
      (value "100k")
      (footprint "eagle-import:1005")
      (libsource (lib "eagle-import") (part "R1005"))
    )
    (comp (ref "R97")
      (value "100k")
      (footprint "eagle-import:1005")
      (libsource (lib "eagle-import") (part "R1005"))
    )
    (comp (ref "RA2")
      (value "51")
      (footprint "eagle-import:1005-A4")
      (libsource (lib "eagle-import") (part "RA4"))
    )
    (comp (ref "RA3")
      (value "51")
      (footprint "eagle-import:1005-A4")
      (libsource (lib "eagle-import") (part "RA4"))
    )
    (comp (ref "RA4")
      (value "51")
      (footprint "eagle-import:1005-A4")
      (libsource (lib "eagle-import") (part "RA4"))
    )
    (comp (ref "RA5")
      (value "51")
      (footprint "eagle-import:1005-A4")
      (libsource (lib "eagle-import") (part "RA4"))
    )
    (comp (ref "RA6")
      (value "51")
      (footprint "eagle-import:1005-A4")
      (libsource (lib "eagle-import") (part "RA4"))
    )
    (comp (ref "RA7")
      (value "51")
      (footprint "eagle-import:1005-A4")
      (libsource (lib "eagle-import") (part "RA4"))
    )
    (comp (ref "RA8")
      (value "51")
      (footprint "eagle-import:1005-A4")
      (libsource (lib "eagle-import") (part "RA4"))
    )
    (comp (ref "RA9")
      (value "51")
      (footprint "eagle-import:1005-A4")
      (libsource (lib "eagle-import") (part "RA4"))
    )
    (comp (ref "U14")
      (value "DRV8332")
      (footprint "eagle-import:HSSOP36")
      (libsource (lib "eagle-import") (part "DRV8332"))
    )
    (comp (ref "U15")
      (value "INA214")
      (footprint "eagle-import:SC70-6")
      (fields (field (name "GAIN") "500"))
      (libsource (lib "eagle-import") (part "INA214"))
    )
    (comp (ref "U16")
      (value "INA214")
      (footprint "eagle-import:SC70-6")
      (fields (field (name "GAIN") "500"))
      (libsource (lib "eagle-import") (part "INA214"))
    )
    (comp (ref "U17")
      (value "DRV8332")
      (footprint "eagle-import:HSSOP36")
      (libsource (lib "eagle-import") (part "DRV8332"))
    )
    (comp (ref "U18")
      (value "INA214")
      (footprint "eagle-import:SC70-6")
      (fields (field (name "GAIN") "500"))
      (libsource (lib "eagle-import") (part "INA214"))
    )
    (comp (ref "U19")
      (value "INA214")
      (footprint "eagle-import:SC70-6")
      (fields (field (name "GAIN") "500"))
      (libsource (lib "eagle-import") (part "INA214"))
    )
    (comp (ref "U20")
      (value "DRV8332")
      (footprint "eagle-import:HSSOP36")
      (libsource (lib "eagle-import") (part "DRV8332"))
    )
    (comp (ref "U21")
      (value "INA214")
      (footprint "eagle-import:SC70-6")
      (fields (field (name "GAIN") "500"))
      (libsource (lib "eagle-import") (part "INA214"))
    )
    (comp (ref "U22")
      (value "INA214")
      (footprint "eagle-import:SC70-6")
      (fields (field (name "GAIN") "500"))
      (libsource (lib "eagle-import") (part "INA214"))
    )
    (comp (ref "U23")
      (value "DRV8332")
      (footprint "eagle-import:HSSOP36")
      (libsource (lib "eagle-import") (part "DRV8332"))
    )
    (comp (ref "U24")
      (value "INA214")
      (footprint "eagle-import:SC70-6")
      (fields (field (name "GAIN") "500"))
      (libsource (lib "eagle-import") (part "INA214"))
    )
    (comp (ref "U25")
      (value "INA214")
      (footprint "eagle-import:SC70-6")
      (fields (field (name "GAIN") "500"))
      (libsource (lib "eagle-import") (part "INA214"))
    )
    (comp (ref "BZ1")
      (value "PKLCS1212E4001")
      (footprint "eagle-import:PKLCS1212")
      (libsource (lib "eagle-import") (part "PKLCS1212E4001"))
    )
    (comp (ref "C38")
      (value "100n")
      (footprint "eagle-import:1005")
      (libsource (lib "eagle-import") (part "C1005"))
    )
    (comp (ref "C39")
      (value "1n")
      (footprint "eagle-import:1005")
      (libsource (lib "eagle-import") (part "C1005"))
    )
    (comp (ref "C40")
      (value "1n")
      (footprint "eagle-import:1005")
      (libsource (lib "eagle-import") (part "C1005"))
    )
    (comp (ref "C41")
      (value "100n")
      (footprint "eagle-import:1005")
      (libsource (lib "eagle-import") (part "C1005"))
    )
    (comp (ref "C42")
      (value "100u")
      (footprint "eagle-import:3225")
      (libsource (lib "eagle-import") (part "C3225"))
    )
    (comp (ref "C43")
      (value "100n")
      (footprint "eagle-import:1005")
      (libsource (lib "eagle-import") (part "C1005"))
    )
    (comp (ref "C44")
      (value "100n")
      (footprint "eagle-import:1005")
      (libsource (lib "eagle-import") (part "C1005"))
    )
    (comp (ref "C45")
      (value "100n")
      (footprint "eagle-import:1005")
      (libsource (lib "eagle-import") (part "C1005"))
    )
    (comp (ref "C46")
      (value "100n")
      (footprint "eagle-import:1005")
      (libsource (lib "eagle-import") (part "C1005"))
    )
    (comp (ref "C47")
      (value "100n")
      (footprint "eagle-import:1005")
      (libsource (lib "eagle-import") (part "C1005"))
    )
    (comp (ref "C48")
      (value "100n")
      (footprint "eagle-import:1005")
      (libsource (lib "eagle-import") (part "C1005"))
    )
    (comp (ref "C49")
      (value "100n")
      (footprint "eagle-import:1005")
      (libsource (lib "eagle-import") (part "C1005"))
    )
    (comp (ref "C50")
      (value "100n")
      (footprint "eagle-import:1005")
      (libsource (lib "eagle-import") (part "C1005"))
    )
    (comp (ref "C51")
      (value "100n")
      (footprint "eagle-import:1005")
      (libsource (lib "eagle-import") (part "C1005"))
    )
    (comp (ref "C52")
      (value "100n")
      (footprint "eagle-import:1005")
      (libsource (lib "eagle-import") (part "C1005"))
    )
    (comp (ref "C53")
      (value "100n")
      (footprint "eagle-import:1005")
      (libsource (lib "eagle-import") (part "C1005"))
    )
    (comp (ref "C54")
      (value "100n")
      (footprint "eagle-import:1005")
      (libsource (lib "eagle-import") (part "C1005"))
    )
    (comp (ref "C55")
      (value "100n")
      (footprint "eagle-import:NFM18")
      (libsource (lib "eagle-import") (part "CT1608"))
    )
    (comp (ref "C56")
      (value "100n")
      (footprint "eagle-import:NFM18")
      (libsource (lib "eagle-import") (part "CT1608"))
    )
    (comp (ref "C57")
      (value "100n")
      (footprint "eagle-import:1005")
      (libsource (lib "eagle-import") (part "C1005"))
    )
    (comp (ref "C58")
      (value "100n")
      (footprint "eagle-import:NFM18")
      (libsource (lib "eagle-import") (part "CT1608"))
    )
    (comp (ref "C59")
      (value "100n")
      (footprint "eagle-import:1005")
      (libsource (lib "eagle-import") (part "C1005"))
    )
    (comp (ref "C60")
      (value "100n")
      (footprint "eagle-import:NFM18")
      (libsource (lib "eagle-import") (part "CT1608"))
    )
    (comp (ref "C61")
      (value "100n")
      (footprint "eagle-import:1005")
      (libsource (lib "eagle-import") (part "C1005"))
    )
    (comp (ref "C62")
      (value "100n")
      (footprint "eagle-import:NFM18")
      (libsource (lib "eagle-import") (part "CT1608"))
    )
    (comp (ref "C63")
      (value "100u")
      (footprint "eagle-import:3225")
      (libsource (lib "eagle-import") (part "C3225"))
    )
    (comp (ref "C64")
      (value "1u")
      (footprint "eagle-import:1005")
      (libsource (lib "eagle-import") (part "C1005"))
    )
    (comp (ref "C65")
      (value "1n")
      (footprint "eagle-import:1005")
      (libsource (lib "eagle-import") (part "C1005"))
    )
    (comp (ref "C66")
      (value "1u")
      (footprint "eagle-import:1608")
      (libsource (lib "eagle-import") (part "C1608"))
    )
    (comp (ref "C67")
      (value "22u")
      (footprint "eagle-import:2012")
      (libsource (lib "eagle-import") (part "C2012"))
    )
    (comp (ref "CN6")
      (value "External SPI 1")
      (footprint "eagle-import:PIN1X8")
      (libsource (lib "eagle-import") (part "PIN1X8"))
    )
    (comp (ref "CN7")
      (value "XBee")
      (footprint "eagle-import:XBEE-TH")
      (libsource (lib "eagle-import") (part "XBEE-TH"))
    )
    (comp (ref "CN8")
      (value "Ball Sensor")
      (footprint "eagle-import:53375-04")
      (libsource (lib "eagle-import") (part "53375-0410"))
    )
    (comp (ref "CN18")
      (value "External SPI 2")
      (footprint "eagle-import:PIN2X4")
      (libsource (lib "eagle-import") (part "PIN2X4"))
    )
    (comp (ref "FB1")
      (value "FB1608")
      (footprint "eagle-import:1608")
      (libsource (lib "eagle-import") (part "FB1608"))
    )
    (comp (ref "LED4")
      (value "LED1608")
      (footprint "eagle-import:1608")
      (libsource (lib "eagle-import") (part "LED1608"))
    )
    (comp (ref "LED5")
      (value "LED1608")
      (footprint "eagle-import:1608")
      (libsource (lib "eagle-import") (part "LED1608"))
    )
    (comp (ref "LED6")
      (value "LED1608")
      (footprint "eagle-import:1608")
      (libsource (lib "eagle-import") (part "LED1608"))
    )
    (comp (ref "LED7")
      (value "LED1608")
      (footprint "eagle-import:1608")
      (libsource (lib "eagle-import") (part "LED1608"))
    )
    (comp (ref "LED8")
      (value "LED1608")
      (footprint "eagle-import:1608")
      (libsource (lib "eagle-import") (part "LED1608"))
    )
    (comp (ref "LED9")
      (value "LED1608")
      (footprint "eagle-import:1608")
      (libsource (lib "eagle-import") (part "LED1608"))
    )
    (comp (ref "LED10")
      (value "LED1608")
      (footprint "eagle-import:1608")
      (libsource (lib "eagle-import") (part "LED1608"))
    )
    (comp (ref "P1")
      (value "TCK")
      (footprint "eagle-import:PAD")
      (libsource (lib "eagle-import") (part "PAD"))
    )
    (comp (ref "P2")
      (value "TDI")
      (footprint "eagle-import:PAD")
      (libsource (lib "eagle-import") (part "PAD"))
    )
    (comp (ref "P3")
      (value "TDO")
      (footprint "eagle-import:PAD")
      (libsource (lib "eagle-import") (part "PAD"))
    )
    (comp (ref "P4")
      (value "TMS")
      (footprint "eagle-import:PAD")
      (libsource (lib "eagle-import") (part "PAD"))
    )
    (comp (ref "R44")
      (value "10k")
      (footprint "eagle-import:1005")
      (libsource (lib "eagle-import") (part "R1005"))
    )
    (comp (ref "R45")
      (value "10k")
      (footprint "eagle-import:1005")
      (libsource (lib "eagle-import") (part "R1005"))
    )
    (comp (ref "R46")
      (value "1k")
      (footprint "eagle-import:1005")
      (libsource (lib "eagle-import") (part "R1005"))
    )
    (comp (ref "R47")
      (value "1k")
      (footprint "eagle-import:1005")
      (libsource (lib "eagle-import") (part "R1005"))
    )
    (comp (ref "R48")
      (value "1k")
      (footprint "eagle-import:1005")
      (libsource (lib "eagle-import") (part "R1005"))
    )
    (comp (ref "R49")
      (value "1k")
      (footprint "eagle-import:1005")
      (libsource (lib "eagle-import") (part "R1005"))
    )
    (comp (ref "R50")
      (value "1k")
      (footprint "eagle-import:1005")
      (libsource (lib "eagle-import") (part "R1005"))
    )
    (comp (ref "R51")
      (value "1k")
      (footprint "eagle-import:1005")
      (libsource (lib "eagle-import") (part "R1005"))
    )
    (comp (ref "R52")
      (value "1k")
      (footprint "eagle-import:1005")
      (libsource (lib "eagle-import") (part "R1005"))
    )
    (comp (ref "R53")
      (value "10k")
      (footprint "eagle-import:1005")
      (libsource (lib "eagle-import") (part "R1005"))
    )
    (comp (ref "R54")
      (value "3.9k")
      (footprint "eagle-import:1608")
      (libsource (lib "eagle-import") (part "R1608"))
    )
    (comp (ref "R55")
      (value "3.9k")
      (footprint "eagle-import:1608")
      (libsource (lib "eagle-import") (part "R1608"))
    )
    (comp (ref "R56")
      (value "1k")
      (footprint "eagle-import:1005")
      (libsource (lib "eagle-import") (part "R1005"))
    )
    (comp (ref "R57")
      (value "51")
      (footprint "eagle-import:1005")
      (libsource (lib "eagle-import") (part "R1005"))
    )
    (comp (ref "R58")
      (value "51")
      (footprint "eagle-import:1005")
      (libsource (lib "eagle-import") (part "R1005"))
    )
    (comp (ref "R59")
      (value "51")
      (footprint "eagle-import:1005")
      (libsource (lib "eagle-import") (part "R1005"))
    )
    (comp (ref "R60")
      (value "10k")
      (footprint "eagle-import:1005")
      (libsource (lib "eagle-import") (part "R1005"))
    )
    (comp (ref "R61")
      (value "10k")
      (footprint "eagle-import:1005")
      (libsource (lib "eagle-import") (part "R1005"))
    )
    (comp (ref "RF1")
      (value "200m")
      (footprint "eagle-import:2012")
      (libsource (lib "eagle-import") (part "RF2012"))
    )
    (comp (ref "RF2")
      (value "200m")
      (footprint "eagle-import:2012")
      (libsource (lib "eagle-import") (part "RF2012"))
    )
    (comp (ref "U8")
      (value "1G08DCK")
      (footprint "eagle-import:SC70-5")
      (libsource (lib "eagle-import") (part "1G08DCK"))
    )
    (comp (ref "U9")
      (value "XC6SLX9-TQ144")
      (footprint "eagle-import:QFP144-0.5")
      (libsource (lib "eagle-import") (part "XC6SLX9-TQ144"))
    )
    (comp (ref "U10")
      (value "1G08DCK")
      (footprint "eagle-import:SC70-5")
      (libsource (lib "eagle-import") (part "1G08DCK"))
    )
    (comp (ref "U11")
      (value "TC74VHC164FT")
      (footprint "eagle-import:TSSOP14")
      (libsource (lib "eagle-import") (part "TC74VHC164FT"))
    )
    (comp (ref "U12")
      (value "FDG6323L")
      (footprint "eagle-import:SC70-6")
      (libsource (lib "eagle-import") (part "FDG6323L"))
    )
    (comp (ref "U13")
      (value "AE-NJU72501")
      (footprint "eagle-import:AE-NJU72501")
      (libsource (lib "eagle-import") (part "AE-NJU72501"))
    )
    (comp (ref "VR1")
      (value "500")
      (footprint "eagle-import:VR")
      (libsource (lib "eagle-import") (part "VR"))
    )
    (comp (ref "C132")
      (value "100n")
      (footprint "eagle-import:1005")
      (libsource (lib "eagle-import") (part "C1005"))
    )
    (comp (ref "C133")
      (value "100n")
      (footprint "eagle-import:1005")
      (libsource (lib "eagle-import") (part "C1005"))
    )
    (comp (ref "C134")
      (value "1u")
      (footprint "eagle-import:1005")
      (libsource (lib "eagle-import") (part "C1005"))
    )
    (comp (ref "C135")
      (value "22u")
      (footprint "eagle-import:2012")
      (libsource (lib "eagle-import") (part "C2012"))
    )
    (comp (ref "C136")
      (value "100n")
      (footprint "eagle-import:1005")
      (libsource (lib "eagle-import") (part "C1005"))
    )
    (comp (ref "C137")
      (value "22u")
      (footprint "eagle-import:2012")
      (libsource (lib "eagle-import") (part "C2012"))
    )
    (comp (ref "C138")
      (value "100n")
      (footprint "eagle-import:1005")
      (libsource (lib "eagle-import") (part "C1005"))
    )
    (comp (ref "C139")
      (value "100n")
      (footprint "eagle-import:1005")
      (libsource (lib "eagle-import") (part "C1005"))
    )
    (comp (ref "C140")
      (value "100n")
      (footprint "eagle-import:1005")
      (libsource (lib "eagle-import") (part "C1005"))
    )
    (comp (ref "C141")
      (value "100n")
      (footprint "eagle-import:1005")
      (libsource (lib "eagle-import") (part "C1005"))
    )
    (comp (ref "C142")
      (value "1u")
      (footprint "eagle-import:1005")
      (libsource (lib "eagle-import") (part "C1005"))
    )
    (comp (ref "C143")
      (value "22u")
      (footprint "eagle-import:2012")
      (libsource (lib "eagle-import") (part "C2012"))
    )
    (comp (ref "C144")
      (value "100n")
      (footprint "eagle-import:1005")
      (libsource (lib "eagle-import") (part "C1005"))
    )
    (comp (ref "C145")
      (value "22u")
      (footprint "eagle-import:2012")
      (libsource (lib "eagle-import") (part "C2012"))
    )
    (comp (ref "C146")
      (value "100n")
      (footprint "eagle-import:1005")
      (libsource (lib "eagle-import") (part "C1005"))
    )
    (comp (ref "C147")
      (value "100n")
      (footprint "eagle-import:1005")
      (libsource (lib "eagle-import") (part "C1005"))
    )
    (comp (ref "C148")
      (value "100n")
      (footprint "eagle-import:1005")
      (libsource (lib "eagle-import") (part "C1005"))
    )
    (comp (ref "C149")
      (value "100u")
      (footprint "eagle-import:E2.5-6.3")
      (libsource (lib "eagle-import") (part "CPOL2.5-6.3"))
    )
    (comp (ref "C150")
      (value "1u")
      (footprint "eagle-import:1608")
      (libsource (lib "eagle-import") (part "C1608"))
    )
    (comp (ref "C151")
      (value "1u")
      (footprint "eagle-import:1608")
      (libsource (lib "eagle-import") (part "C1608"))
    )
    (comp (ref "C152")
      (value "1u")
      (footprint "eagle-import:1608")
      (libsource (lib "eagle-import") (part "C1608"))
    )
    (comp (ref "C153")
      (value "100n")
      (footprint "eagle-import:1005")
      (libsource (lib "eagle-import") (part "C1005"))
    )
    (comp (ref "C154")
      (value "1u")
      (footprint "eagle-import:1608")
      (libsource (lib "eagle-import") (part "C1608"))
    )
    (comp (ref "C155")
      (value "100n")
      (footprint "eagle-import:1608")
      (libsource (lib "eagle-import") (part "C1608"))
    )
    (comp (ref "C156")
      (value "100n")
      (footprint "eagle-import:1608")
      (libsource (lib "eagle-import") (part "C1608"))
    )
    (comp (ref "C157")
      (value "100n")
      (footprint "eagle-import:1608")
      (libsource (lib "eagle-import") (part "C1608"))
    )
    (comp (ref "C158")
      (value "100n")
      (footprint "eagle-import:1608")
      (libsource (lib "eagle-import") (part "C1608"))
    )
    (comp (ref "C159")
      (value "100n")
      (footprint "eagle-import:1608")
      (libsource (lib "eagle-import") (part "C1608"))
    )
    (comp (ref "C160")
      (value "100n")
      (footprint "eagle-import:1608")
      (libsource (lib "eagle-import") (part "C1608"))
    )
    (comp (ref "C161")
      (value "220u")
      (footprint "eagle-import:E3.5-8")
      (libsource (lib "eagle-import") (part "CPOL3.5-8"))
    )
    (comp (ref "C162")
      (value "100n")
      (footprint "eagle-import:1005")
      (libsource (lib "eagle-import") (part "C1005"))
    )
    (comp (ref "C163")
      (value "100n")
      (footprint "eagle-import:1005")
      (libsource (lib "eagle-import") (part "C1005"))
    )
    (comp (ref "C164")
      (value "100n")
      (footprint "eagle-import:1005")
      (libsource (lib "eagle-import") (part "C1005"))
    )
    (comp (ref "C165")
      (value "100n")
      (footprint "eagle-import:1005")
      (libsource (lib "eagle-import") (part "C1005"))
    )
    (comp (ref "CN17")
      (value "Dribble")
      (footprint "eagle-import:PIN1X8")
      (libsource (lib "eagle-import") (part "PIN1X8"))
    )
    (comp (ref "R98")
      (value "33k")
      (footprint "eagle-import:1005")
      (libsource (lib "eagle-import") (part "R1005"))
    )
    (comp (ref "R99")
      (value "100k")
      (footprint "eagle-import:1005")
      (libsource (lib "eagle-import") (part "R1005"))
    )
    (comp (ref "R100")
      (value "3.9k")
      (footprint "eagle-import:1608")
      (libsource (lib "eagle-import") (part "R1608"))
    )
    (comp (ref "R101")
      (value "51")
      (footprint "eagle-import:1005")
      (libsource (lib "eagle-import") (part "R1005"))
    )
    (comp (ref "R102")
      (value "51")
      (footprint "eagle-import:1005")
      (libsource (lib "eagle-import") (part "R1005"))
    )
    (comp (ref "R103")
      (value "10k")
      (footprint "eagle-import:1005")
      (libsource (lib "eagle-import") (part "R1005"))
    )
    (comp (ref "R104")
      (value "100k")
      (footprint "eagle-import:1005")
      (libsource (lib "eagle-import") (part "R1005"))
    )
    (comp (ref "R105")
      (value "33k")
      (footprint "eagle-import:1005")
      (libsource (lib "eagle-import") (part "R1005"))
    )
    (comp (ref "R106")
      (value "3.9k")
      (footprint "eagle-import:1608")
      (libsource (lib "eagle-import") (part "R1608"))
    )
    (comp (ref "R107")
      (value "51")
      (footprint "eagle-import:1005")
      (libsource (lib "eagle-import") (part "R1005"))
    )
    (comp (ref "R108")
      (value "51")
      (footprint "eagle-import:1005")
      (libsource (lib "eagle-import") (part "R1005"))
    )
    (comp (ref "R109")
      (value "10k")
      (footprint "eagle-import:1005")
      (libsource (lib "eagle-import") (part "R1005"))
    )
    (comp (ref "R110")
      (value "10k")
      (footprint "eagle-import:1005")
      (libsource (lib "eagle-import") (part "R1005"))
    )
    (comp (ref "R111")
      (value "10k")
      (footprint "eagle-import:1005")
      (libsource (lib "eagle-import") (part "R1005"))
    )
    (comp (ref "R112")
      (value "10k")
      (footprint "eagle-import:1005")
      (libsource (lib "eagle-import") (part "R1005"))
    )
    (comp (ref "R113")
      (value "10k")
      (footprint "eagle-import:1005")
      (libsource (lib "eagle-import") (part "R1005"))
    )
    (comp (ref "R114")
      (value "5m")
      (footprint "eagle-import:3216")
      (libsource (lib "eagle-import") (part "R3216"))
    )
    (comp (ref "R115")
      (value "10k")
      (footprint "eagle-import:1005")
      (libsource (lib "eagle-import") (part "R1005"))
    )
    (comp (ref "R116")
      (value "10k")
      (footprint "eagle-import:1005")
      (libsource (lib "eagle-import") (part "R1005"))
    )
    (comp (ref "R117")
      (value "33k")
      (footprint "eagle-import:1608")
      (libsource (lib "eagle-import") (part "R1608"))
    )
    (comp (ref "R118")
      (value "1")
      (footprint "eagle-import:1005")
      (libsource (lib "eagle-import") (part "R1005"))
    )
    (comp (ref "R119")
      (value "10k")
      (footprint "eagle-import:1005")
      (libsource (lib "eagle-import") (part "R1005"))
    )
    (comp (ref "R120")
      (value "10k")
      (footprint "eagle-import:1005")
      (libsource (lib "eagle-import") (part "R1005"))
    )
    (comp (ref "R121")
      (value "10k")
      (footprint "eagle-import:1005")
      (libsource (lib "eagle-import") (part "R1005"))
    )
    (comp (ref "RA10")
      (value "51")
      (footprint "eagle-import:1005-A4")
      (libsource (lib "eagle-import") (part "RA4"))
    )
    (comp (ref "RA11")
      (value "51")
      (footprint "eagle-import:1005-A4")
      (libsource (lib "eagle-import") (part "RA4"))
    )
    (comp (ref "RF3")
      (value "200m")
      (footprint "eagle-import:2012")
      (libsource (lib "eagle-import") (part "RF2012"))
    )
    (comp (ref "RF4")
      (value "200m")
      (footprint "eagle-import:2012")
      (libsource (lib "eagle-import") (part "RF2012"))
    )
    (comp (ref "U26")
      (value "TC74VHC165FT")
      (footprint "eagle-import:TSSOP16")
      (libsource (lib "eagle-import") (part "TC74VHC165FT"))
    )
    (comp (ref "U27")
      (value "TC74VHC165FT")
      (footprint "eagle-import:TSSOP16")
      (libsource (lib "eagle-import") (part "TC74VHC165FT"))
    )
    (comp (ref "U28")
      (value "ADR5041")
      (footprint "eagle-import:SC70-3")
      (libsource (lib "eagle-import") (part "ADR5041"))
    )
    (comp (ref "U29")
      (value "ADS7950RGE")
      (footprint "eagle-import:QFN24-0.5")
      (libsource (lib "eagle-import") (part "ADS7950RGE"))
    )
    (comp (ref "U30")
      (value "TC74VHC165FT")
      (footprint "eagle-import:TSSOP16")
      (libsource (lib "eagle-import") (part "TC74VHC165FT"))
    )
    (comp (ref "U31")
      (value "TC74VHC165FT")
      (footprint "eagle-import:TSSOP16")
      (libsource (lib "eagle-import") (part "TC74VHC165FT"))
    )
    (comp (ref "U32")
      (value "ADR5041")
      (footprint "eagle-import:SC70-3")
      (libsource (lib "eagle-import") (part "ADR5041"))
    )
    (comp (ref "U33")
      (value "ADS7950RGE")
      (footprint "eagle-import:QFN24-0.5")
      (libsource (lib "eagle-import") (part "ADS7950RGE"))
    )
    (comp (ref "U34")
      (value "FDG6323L")
      (footprint "eagle-import:SC70-6")
      (libsource (lib "eagle-import") (part "FDG6323L"))
    )
    (comp (ref "U35")
      (value "FDG6323L")
      (footprint "eagle-import:SC70-6")
      (libsource (lib "eagle-import") (part "FDG6323L"))
    )
    (comp (ref "U36")
      (value "INA219DCN")
      (footprint "eagle-import:SOT23-8")
      (libsource (lib "eagle-import") (part "INA219DCN"))
    )
    (comp (ref "U37")
      (value "DRV8332")
      (footprint "eagle-import:HSSOP36")
      (libsource (lib "eagle-import") (part "DRV8332"))
    )
    (comp (ref "U38")
      (value "TMP05")
      (footprint "eagle-import:SC70-5")
      (libsource (lib "eagle-import") (part "TMP05"))
    )
    (comp (ref "U39")
      (value "MCP9701/LT")
      (footprint "eagle-import:SC70-6")
      (libsource (lib "eagle-import") (part "MCP970/LT1"))
    )
    (comp (ref "U40")
      (value "TMP05")
      (footprint "eagle-import:SC70-5")
      (libsource (lib "eagle-import") (part "TMP05"))
    )
    (comp (ref "U41")
      (value "TMP05")
      (footprint "eagle-import:SC70-5")
      (libsource (lib "eagle-import") (part "TMP05"))
    )
  )
  (nets
    (net (code "1") (name "+1V2") (class "Default")
      (node (ref "C15") (pin "1") (pinfunction "1_1") (pintype "passive"))
      (node (ref "C55") (pin "2") (pinfunction "2_2") (pintype "passive"))
      (node (ref "C56") (pin "2") (pinfunction "2_2") (pintype "passive"))
      (node (ref "C58") (pin "2") (pinfunction "2_2") (pintype "passive"))
      (node (ref "C60") (pin "2") (pinfunction "2_2") (pintype "passive"))
      (node (ref "C62") (pin "2") (pinfunction "2_2") (pintype "passive"))
      (node (ref "C63") (pin "1") (pinfunction "1_1") (pintype "passive"))
      (node (ref "L2") (pin "2") (pinfunction "2_2") (pintype "passive"))
      (node (ref "R14") (pin "2") (pinfunction "2_2") (pintype "passive"))
    )
    (net (code "2") (name "+3V3") (class "Default")
      (node (ref "C1") (pin "1") (pinfunction "1_1") (pintype "passive"))
      (node (ref "C132") (pin "1") (pinfunction "1_1") (pintype "passive"))
      (node (ref "C133") (pin "1") (pinfunction "1_1") (pintype "passive"))
      (node (ref "C139") (pin "1") (pinfunction "1_1") (pintype "passive"))
      (node (ref "C140") (pin "1") (pinfunction "1_1") (pintype "passive"))
      (node (ref "C141") (pin "1") (pinfunction "1_1") (pintype "passive"))
      (node (ref "C147") (pin "1") (pinfunction "1_1") (pintype "passive"))
      (node (ref "C148") (pin "1") (pinfunction "1_1") (pintype "passive"))
      (node (ref "C162") (pin "1") (pinfunction "1_1") (pintype "passive"))
      (node (ref "C163") (pin "1") (pinfunction "1_1") (pintype "passive"))
      (node (ref "C164") (pin "1") (pinfunction "1_1") (pintype "passive"))
      (node (ref "C165") (pin "1") (pinfunction "1_1") (pintype "passive"))
      (node (ref "C18") (pin "1") (pinfunction "1_1") (pintype "passive"))
      (node (ref "C23") (pin "1") (pinfunction "1_1") (pintype "passive"))
      (node (ref "C26") (pin "1") (pinfunction "1_1") (pintype "passive"))
      (node (ref "C28") (pin "1") (pinfunction "1_1") (pintype "passive"))
      (node (ref "C30") (pin "1") (pinfunction "1_1") (pintype "passive"))
      (node (ref "C33") (pin "1") (pinfunction "1_1") (pintype "passive"))
      (node (ref "C35") (pin "1") (pinfunction "1_1") (pintype "passive"))
      (node (ref "C37") (pin "1") (pinfunction "1_1") (pintype "passive"))
      (node (ref "C38") (pin "1") (pinfunction "1_1") (pintype "passive"))
      (node (ref "C39") (pin "1") (pinfunction "1_1") (pintype "passive"))
      (node (ref "C40") (pin "1") (pinfunction "1_1") (pintype "passive"))
      (node (ref "C41") (pin "1") (pinfunction "1_1") (pintype "passive"))
      (node (ref "C42") (pin "1") (pinfunction "1_1") (pintype "passive"))
      (node (ref "C43") (pin "1") (pinfunction "1_1") (pintype "passive"))
      (node (ref "C44") (pin "1") (pinfunction "1_1") (pintype "passive"))
      (node (ref "C45") (pin "1") (pinfunction "1_1") (pintype "passive"))
      (node (ref "C46") (pin "1") (pinfunction "1_1") (pintype "passive"))
      (node (ref "C47") (pin "1") (pinfunction "1_1") (pintype "passive"))
      (node (ref "C48") (pin "1") (pinfunction "1_1") (pintype "passive"))
      (node (ref "C49") (pin "1") (pinfunction "1_1") (pintype "passive"))
      (node (ref "C50") (pin "1") (pinfunction "1_1") (pintype "passive"))
      (node (ref "C51") (pin "1") (pinfunction "1_1") (pintype "passive"))
      (node (ref "C52") (pin "1") (pinfunction "1_1") (pintype "passive"))
      (node (ref "C53") (pin "1") (pinfunction "1_1") (pintype "passive"))
      (node (ref "C54") (pin "1") (pinfunction "1_1") (pintype "passive"))
      (node (ref "C57") (pin "1") (pinfunction "1_1") (pintype "passive"))
      (node (ref "C59") (pin "1") (pinfunction "1_1") (pintype "passive"))
      (node (ref "C61") (pin "1") (pinfunction "1_1") (pintype "passive"))
      (node (ref "C64") (pin "1") (pinfunction "1_1") (pintype "passive"))
      (node (ref "C67") (pin "1") (pinfunction "1_1") (pintype "passive"))
      (node (ref "CN18") (pin "2") (pinfunction "2_2") (pintype "passive"))
      (node (ref "CN2") (pin "2") (pinfunction "2_2") (pintype "passive"))
      (node (ref "CN4") (pin "4") (pinfunction "VCC_4") (pintype "passive"))
      (node (ref "CN5") (pin "3") (pinfunction "3_3") (pintype "passive"))
      (node (ref "CN6") (pin "1") (pinfunction "1_1") (pintype "passive"))
      (node (ref "FB1") (pin "1") (pinfunction "1_1") (pintype "passive"))
      (node (ref "L5") (pin "2") (pinfunction "2_2") (pintype "passive"))
      (node (ref "R103") (pin "2") (pinfunction "2_2") (pintype "passive"))
      (node (ref "R109") (pin "2") (pinfunction "2_2") (pintype "passive"))
      (node (ref "R115") (pin "2") (pinfunction "2_2") (pintype "passive"))
      (node (ref "R116") (pin "2") (pinfunction "2_2") (pintype "passive"))
      (node (ref "R2") (pin "2") (pinfunction "2_2") (pintype "passive"))
      (node (ref "R20") (pin "2") (pinfunction "2_2") (pintype "passive"))
      (node (ref "R3") (pin "2") (pinfunction "2_2") (pintype "passive"))
      (node (ref "R36") (pin "2") (pinfunction "2_2") (pintype "passive"))
      (node (ref "R37") (pin "2") (pinfunction "2_2") (pintype "passive"))
      (node (ref "R42") (pin "2") (pinfunction "2_2") (pintype "passive"))
      (node (ref "R54") (pin "2") (pinfunction "2_2") (pintype "passive"))
      (node (ref "R55") (pin "2") (pinfunction "2_2") (pintype "passive"))
      (node (ref "R58") (pin "2") (pinfunction "2_2") (pintype "passive"))
      (node (ref "R59") (pin "2") (pinfunction "2_2") (pintype "passive"))
      (node (ref "RA1") (pin "B1") (pinfunction "1_B1") (pintype "passive"))
      (node (ref "RA1") (pin "D1") (pinfunction "1_D1") (pintype "passive"))
      (node (ref "RF2") (pin "2") (pinfunction "2_2") (pintype "passive"))
      (node (ref "U1") (pin "4") (pinfunction "VS_4") (pintype "input"))
      (node (ref "U10") (pin "5") (pinfunction "VCC_5") (pintype "bidirectional"))
      (node (ref "U11") (pin "1") (pinfunction "A_1") (pintype "bidirectional"))
      (node (ref "U11") (pin "14") (pinfunction "VCC_14") (pintype "bidirectional"))
      (node (ref "U11") (pin "9") (pinfunction "~{CLR}_9") (pintype "bidirectional"))
      (node (ref "U13") (pin "1") (pinfunction "VIN_1") (pintype "bidirectional"))
      (node (ref "U13") (pin "5") (pinfunction "EN2_5") (pintype "bidirectional"))
      (node (ref "U13") (pin "6") (pinfunction "EN1_6") (pintype "bidirectional"))
      (node (ref "U26") (pin "16") (pinfunction "VCC_16") (pintype "bidirectional"))
      (node (ref "U27") (pin "16") (pinfunction "VCC_16") (pintype "bidirectional"))
      (node (ref "U29") (pin "21") (pinfunction "+VBD_21") (pintype "bidirectional"))
      (node (ref "U30") (pin "16") (pinfunction "VCC_16") (pintype "bidirectional"))
      (node (ref "U31") (pin "16") (pinfunction "VCC_16") (pintype "bidirectional"))
      (node (ref "U33") (pin "21") (pinfunction "+VBD_21") (pintype "bidirectional"))
      (node (ref "U36") (pin "4") (pinfunction "VS_4") (pintype "input"))
      (node (ref "U38") (pin "5") (pinfunction "VDD_5") (pintype "bidirectional"))
      (node (ref "U39") (pin "4") (pinfunction "VDD_4") (pintype "bidirectional"))
      (node (ref "U40") (pin "5") (pinfunction "VDD_5") (pintype "bidirectional"))
      (node (ref "U41") (pin "5") (pinfunction "VDD_5") (pintype "bidirectional"))
      (node (ref "U5") (pin "18") (pinfunction "ADVREF_18") (pintype "bidirectional"))
      (node (ref "U5") (pin "19") (pinfunction "VDDANA_19") (pintype "bidirectional"))
      (node (ref "U5") (pin "21") (pinfunction "VDDIN_21") (pintype "bidirectional"))
      (node (ref "U5") (pin "32") (pinfunction "VDDIO_32") (pintype "bidirectional"))
      (node (ref "U5") (pin "48") (pinfunction "VDDIO_48") (pintype "bidirectional"))
      (node (ref "U5") (pin "64") (pinfunction "VDDIO_64") (pintype "bidirectional"))
      (node (ref "U7") (pin "3") (pinfunction "~{WP}/SIO2_3") (pintype "bidirectional"))
      (node (ref "U7") (pin "8") (pinfunction "VCC_8") (pintype "bidirectional"))
      (node (ref "U8") (pin "5") (pinfunction "VCC_5") (pintype "bidirectional"))
      (node (ref "U9") (pin "103") (pinfunction "VCCO_1_103") (pintype "bidirectional"))
      (node (ref "U9") (pin "122") (pinfunction "VCCO_0_122") (pintype "bidirectional"))
      (node (ref "U9") (pin "125") (pinfunction "VCCO_0_125") (pintype "bidirectional"))
      (node (ref "U9") (pin "129") (pinfunction "VCCAUX_129") (pintype "bidirectional"))
      (node (ref "U9") (pin "135") (pinfunction "VCCO_0_135") (pintype "bidirectional"))
      (node (ref "U9") (pin "18") (pinfunction "VCCO_3_18") (pintype "bidirectional"))
      (node (ref "U9") (pin "20") (pinfunction "VCCAUX_20") (pintype "bidirectional"))
      (node (ref "U9") (pin "31") (pinfunction "VCCO_3_31") (pintype "bidirectional"))
      (node (ref "U9") (pin "36") (pinfunction "VCCAUX_36") (pintype "bidirectional"))
      (node (ref "U9") (pin "4") (pinfunction "VCCO_3_4") (pintype "bidirectional"))
      (node (ref "U9") (pin "42") (pinfunction "VCCO_2_42") (pintype "bidirectional"))
      (node (ref "U9") (pin "53") (pinfunction "VCCAUX_53") (pintype "bidirectional"))
      (node (ref "U9") (pin "63") (pinfunction "VCCO_2_63") (pintype "bidirectional"))
      (node (ref "U9") (pin "72") (pinfunction "CMPCS_B_2_72") (pintype "bidirectional"))
      (node (ref "U9") (pin "76") (pinfunction "VCCO_1_76") (pintype "bidirectional"))
      (node (ref "U9") (pin "86") (pinfunction "VCCO_1_86") (pintype "bidirectional"))
      (node (ref "U9") (pin "90") (pinfunction "VCCAUX_90") (pintype "bidirectional"))
      (node (ref "X1") (pin "4") (pinfunction "VDD_4") (pintype "bidirectional"))
    )
    (net (code "3") (name "+5V") (class "Default")
      (node (ref "C21") (pin "1") (pinfunction "1_1") (pintype "passive"))
      (node (ref "R100") (pin "2") (pinfunction "2_2") (pintype "passive"))
      (node (ref "R101") (pin "1") (pinfunction "1_1") (pintype "passive"))
      (node (ref "R106") (pin "2") (pinfunction "2_2") (pintype "passive"))
      (node (ref "R107") (pin "1") (pinfunction "1_1") (pintype "passive"))
      (node (ref "R111") (pin "2") (pinfunction "2_2") (pintype "passive"))
      (node (ref "R113") (pin "2") (pinfunction "2_2") (pintype "passive"))
      (node (ref "RF1") (pin "2") (pinfunction "2_2") (pintype "passive"))
      (node (ref "U3") (pin "5") (pinfunction "OUT_5") (pintype "bidirectional"))
      (node (ref "U34") (pin "4") (pinfunction "IN_4") (pintype "bidirectional"))
      (node (ref "U35") (pin "4") (pinfunction "IN_4") (pintype "bidirectional"))
    )
    (net (code "4") (name "+5V{slash}2") (class "Default")
      (node (ref "C128") (pin "1") (pinfunction "1_1") (pintype "passive"))
      (node (ref "C129") (pin "1") (pinfunction "1_1") (pintype "passive"))
      (node (ref "CN10") (pin "4") (pinfunction "4_4") (pintype "passive"))
      (node (ref "CN11") (pin "1.1") (pinfunction "VCC_1.1") (pintype "bidirectional"))
      (node (ref "CN11") (pin "2.8") (pinfunction "VCC_2.8") (pintype "bidirectional"))
      (node (ref "CN12") (pin "4") (pinfunction "4_4") (pintype "passive"))
      (node (ref "CN9") (pin "1.1") (pinfunction "VCC_1.1") (pintype "bidirectional"))
      (node (ref "CN9") (pin "2.8") (pinfunction "VCC_2.8") (pintype "bidirectional"))
      (node (ref "RF3") (pin "1") (pinfunction "1_1") (pintype "passive"))
    )
    (net (code "5") (name "+5V{slash}3") (class "Default")
      (node (ref "C130") (pin "1") (pinfunction "1_1") (pintype "passive"))
      (node (ref "C131") (pin "1") (pinfunction "1_1") (pintype "passive"))
      (node (ref "CN13") (pin "1.1") (pinfunction "VCC_1.1") (pintype "bidirectional"))
      (node (ref "CN13") (pin "2.8") (pinfunction "VCC_2.8") (pintype "bidirectional"))
      (node (ref "CN14") (pin "4") (pinfunction "4_4") (pintype "passive"))
      (node (ref "CN15") (pin "1.1") (pinfunction "VCC_1.1") (pintype "bidirectional"))
      (node (ref "CN15") (pin "2.8") (pinfunction "VCC_2.8") (pintype "bidirectional"))
      (node (ref "CN16") (pin "4") (pinfunction "4_4") (pintype "passive"))
      (node (ref "CN17") (pin "4") (pinfunction "4_4") (pintype "passive"))
      (node (ref "R119") (pin "2") (pinfunction "2_2") (pintype "passive"))
      (node (ref "R120") (pin "2") (pinfunction "2_2") (pintype "passive"))
      (node (ref "R121") (pin "2") (pinfunction "2_2") (pintype "passive"))
      (node (ref "RF4") (pin "1") (pinfunction "1_1") (pintype "passive"))
    )
    (net (code "6") (name "+12V") (class "Default")
      (node (ref "C100") (pin "1") (pinfunction "1_1") (pintype "passive"))
      (node (ref "C101") (pin "1") (pinfunction "1_1") (pintype "passive"))
      (node (ref "C103") (pin "1") (pinfunction "1_1") (pintype "passive"))
      (node (ref "C113") (pin "P") (pinfunction "P_P") (pintype "passive"))
      (node (ref "C114") (pin "1") (pinfunction "1_1") (pintype "passive"))
      (node (ref "C115") (pin "1") (pinfunction "1_1") (pintype "passive"))
      (node (ref "C116") (pin "1") (pinfunction "1_1") (pintype "passive"))
      (node (ref "C118") (pin "1") (pinfunction "1_1") (pintype "passive"))
      (node (ref "C14") (pin "2") (pinfunction "2_2") (pintype "passive"))
      (node (ref "C149") (pin "P") (pinfunction "P_P") (pintype "passive"))
      (node (ref "C150") (pin "1") (pinfunction "1_1") (pintype "passive"))
      (node (ref "C151") (pin "1") (pinfunction "1_1") (pintype "passive"))
      (node (ref "C152") (pin "1") (pinfunction "1_1") (pintype "passive"))
      (node (ref "C154") (pin "1") (pinfunction "1_1") (pintype "passive"))
      (node (ref "C16") (pin "1") (pinfunction "1_1") (pintype "passive"))
      (node (ref "C68") (pin "P") (pinfunction "P_P") (pintype "passive"))
      (node (ref "C69") (pin "1") (pinfunction "1_1") (pintype "passive"))
      (node (ref "C70") (pin "1") (pinfunction "1_1") (pintype "passive"))
      (node (ref "C71") (pin "1") (pinfunction "1_1") (pintype "passive"))
      (node (ref "C73") (pin "1") (pinfunction "1_1") (pintype "passive"))
      (node (ref "C83") (pin "P") (pinfunction "P_P") (pintype "passive"))
      (node (ref "C84") (pin "1") (pinfunction "1_1") (pintype "passive"))
      (node (ref "C85") (pin "1") (pinfunction "1_1") (pintype "passive"))
      (node (ref "C86") (pin "1") (pinfunction "1_1") (pintype "passive"))
      (node (ref "C88") (pin "1") (pinfunction "1_1") (pintype "passive"))
      (node (ref "C98") (pin "P") (pinfunction "P_P") (pintype "passive"))
      (node (ref "C99") (pin "1") (pinfunction "1_1") (pintype "passive"))
      (node (ref "L3") (pin "2") (pinfunction "2_2") (pintype "passive"))
      (node (ref "R16") (pin "2") (pinfunction "2_2") (pintype "passive"))
      (node (ref "R6") (pin "2") (pinfunction "2_2") (pintype "passive"))
      (node (ref "U14") (pin "1") (pinfunction "GVDD_B_1") (pintype "bidirectional"))
      (node (ref "U14") (pin "17") (pinfunction "VDD_17") (pintype "bidirectional"))
      (node (ref "U14") (pin "18") (pinfunction "GVDD_C_18") (pintype "bidirectional"))
      (node (ref "U14") (pin "19") (pinfunction "GVDD_C_19") (pintype "bidirectional"))
      (node (ref "U14") (pin "36") (pinfunction "GVDD_A_36") (pintype "bidirectional"))
      (node (ref "U17") (pin "1") (pinfunction "GVDD_B_1") (pintype "bidirectional"))
      (node (ref "U17") (pin "17") (pinfunction "VDD_17") (pintype "bidirectional"))
      (node (ref "U17") (pin "18") (pinfunction "GVDD_C_18") (pintype "bidirectional"))
      (node (ref "U17") (pin "19") (pinfunction "GVDD_C_19") (pintype "bidirectional"))
      (node (ref "U17") (pin "36") (pinfunction "GVDD_A_36") (pintype "bidirectional"))
      (node (ref "U20") (pin "1") (pinfunction "GVDD_B_1") (pintype "bidirectional"))
      (node (ref "U20") (pin "17") (pinfunction "VDD_17") (pintype "bidirectional"))
      (node (ref "U20") (pin "18") (pinfunction "GVDD_C_18") (pintype "bidirectional"))
      (node (ref "U20") (pin "19") (pinfunction "GVDD_C_19") (pintype "bidirectional"))
      (node (ref "U20") (pin "36") (pinfunction "GVDD_A_36") (pintype "bidirectional"))
      (node (ref "U23") (pin "1") (pinfunction "GVDD_B_1") (pintype "bidirectional"))
      (node (ref "U23") (pin "17") (pinfunction "VDD_17") (pintype "bidirectional"))
      (node (ref "U23") (pin "18") (pinfunction "GVDD_C_18") (pintype "bidirectional"))
      (node (ref "U23") (pin "19") (pinfunction "GVDD_C_19") (pintype "bidirectional"))
      (node (ref "U23") (pin "36") (pinfunction "GVDD_A_36") (pintype "bidirectional"))
      (node (ref "U37") (pin "1") (pinfunction "GVDD_B_1") (pintype "bidirectional"))
      (node (ref "U37") (pin "17") (pinfunction "VDD_17") (pintype "bidirectional"))
      (node (ref "U37") (pin "18") (pinfunction "GVDD_C_18") (pintype "bidirectional"))
      (node (ref "U37") (pin "19") (pinfunction "GVDD_C_19") (pintype "bidirectional"))
      (node (ref "U37") (pin "36") (pinfunction "GVDD_A_36") (pintype "bidirectional"))
    )
    (net (code "7") (name "ADC1_MISO") (class "Default")
      (node (ref "R102") (pin "2") (pinfunction "2_2") (pintype "passive"))
      (node (ref "U9") (pin "85") (pinfunction "IO_L43P_GCLK5_1_85") (pintype "bidirectional"))
    )
    (net (code "8") (name "ADC1_MOSI") (class "Default")
      (node (ref "U29") (pin "18") (pinfunction "SDI_18") (pintype "bidirectional"))
      (node (ref "U9") (pin "87") (pinfunction "IO_L42N_GCLK6_TRDY1_1_87") (pintype "bidirectional"))
    )
    (net (code "9") (name "ADC1_SCLK") (class "Default")
      (node (ref "U29") (pin "17") (pinfunction "SCLK_17") (pintype "bidirectional"))
      (node (ref "U9") (pin "88") (pinfunction "IO_L42P_GCLK7_1_88") (pintype "bidirectional"))
    )
    (net (code "10") (name "ADC2_MISO") (class "Default")
      (node (ref "R108") (pin "2") (pinfunction "2_2") (pintype "passive"))
      (node (ref "U9") (pin "14") (pinfunction "IO_L44N_GCLK20_3_14") (pintype "bidirectional"))
    )
    (net (code "11") (name "ADC2_MOSI") (class "Default")
      (node (ref "U33") (pin "18") (pinfunction "SDI_18") (pintype "bidirectional"))
      (node (ref "U9") (pin "15") (pinfunction "IO_L44P_GCLK21_3_15") (pintype "bidirectional"))
    )
    (net (code "12") (name "ADC2_SCLK") (class "Default")
      (node (ref "U33") (pin "17") (pinfunction "SCLK_17") (pintype "bidirectional"))
      (node (ref "U9") (pin "16") (pinfunction "IO_L43N_GCLK22_IRDY2_3_16") (pintype "bidirectional"))
    )
    (net (code "13") (name "BALL_DETECT{slash}BALL_SDA") (class "Default")
      (node (ref "R56") (pin "2") (pinfunction "2_2") (pintype "passive"))
      (node (ref "U9") (pin "112") (pinfunction "IO_L66P_SCP1_0_112") (pintype "bidirectional"))
    )
    (net (code "14") (name "BALL_EN") (class "Default")
      (node (ref "R60") (pin "2") (pinfunction "2_2") (pintype "passive"))
      (node (ref "U12") (pin "5") (pinfunction "EN_5") (pintype "bidirectional"))
      (node (ref "U9") (pin "116") (pinfunction "IO_L64N_SCP4_0_116") (pintype "bidirectional"))
    )
    (net (code "15") (name "BALL_SCL") (class "Default")
      (node (ref "R57") (pin "2") (pinfunction "2_2") (pintype "passive"))
      (node (ref "U9") (pin "114") (pinfunction "IO_L65N_SCP2_0_114") (pintype "bidirectional"))
    )
    (net (code "16") (name "BUZZER_PWM") (class "Default")
      (node (ref "C65") (pin "1") (pinfunction "1_1") (pintype "passive"))
      (node (ref "R45") (pin "1") (pinfunction "1_1") (pintype "passive"))
      (node (ref "U13") (pin "3") (pinfunction "DIN_3") (pintype "bidirectional"))
    )
    (net (code "17") (name "CHARGER_RX") (class "Default")
      (node (ref "CN2") (pin "5") (pinfunction "5_5") (pintype "passive"))
      (node (ref "R39") (pin "2") (pinfunction "2_2") (pintype "passive"))
    )
    (net (code "18") (name "CHARGER_TX") (class "Default")
      (node (ref "CN2") (pin "6") (pinfunction "6_6") (pintype "passive"))
      (node (ref "R38") (pin "2") (pinfunction "2_2") (pintype "passive"))
    )
    (net (code "19") (name "DEBUG_RX") (class "Default")
      (node (ref "CN5") (pin "2") (pinfunction "2_2") (pintype "passive"))
      (node (ref "RA1") (pin "C2") (pinfunction "2_C2") (pintype "passive"))
    )
    (net (code "20") (name "DEBUG_TX") (class "Default")
      (node (ref "CN5") (pin "1") (pinfunction "1_1") (pintype "passive"))
      (node (ref "RA1") (pin "A2") (pinfunction "2_A2") (pintype "passive"))
    )
    (net (code "21") (name "EXT1_CE") (class "Default")
      (node (ref "CN6") (pin "2") (pinfunction "2_2") (pintype "passive"))
      (node (ref "U9") (pin "117") (pinfunction "IO_L64P_SCP5_0_117") (pintype "bidirectional"))
    )
    (net (code "22") (name "EXT1_CSN") (class "Default")
      (node (ref "CN6") (pin "3") (pinfunction "3_3") (pintype "passive"))
      (node (ref "U9") (pin "119") (pinfunction "IO_L63P_SCP7_0_119") (pintype "bidirectional"))
    )
    (net (code "23") (name "EXT1_IRQ") (class "Default")
      (node (ref "CN6") (pin "7") (pinfunction "7_7") (pintype "passive"))
      (node (ref "U9") (pin "132") (pinfunction "IO_L35P_GCLK17_0_132") (pintype "bidirectional"))
    )
    (net (code "24") (name "EXT1_MISO") (class "Default")
      (node (ref "CN6") (pin "6") (pinfunction "6_6") (pintype "passive"))
      (node (ref "U9") (pin "127") (pinfunction "IO_L36P_GCLK15_0_127") (pintype "bidirectional"))
    )
    (net (code "25") (name "EXT1_MOSI") (class "Default")
      (node (ref "CN6") (pin "5") (pinfunction "5_5") (pintype "passive"))
      (node (ref "U9") (pin "124") (pinfunction "IO_L37P_GCLK13_0_124") (pintype "bidirectional"))
    )
    (net (code "26") (name "EXT1_SCK") (class "Default")
      (node (ref "CN6") (pin "4") (pinfunction "4_4") (pintype "passive"))
      (node (ref "U9") (pin "121") (pinfunction "IO_L62P_0_121") (pintype "bidirectional"))
    )
    (net (code "27") (name "FPGA_AUX0") (class "Default")
      (node (ref "CN18") (pin "8") (pinfunction "8_8") (pintype "passive"))
      (node (ref "U5") (pin "30") (pinfunction "PA11/XIN32/PWM0/TC-A2/USART0-RTS/SSC-RXDAT_30") (pintype "bidirectional"))
      (node (ref "U9") (pin "69") (pinfunction "IO_L1N_M0_CMPMISO_2_69") (pintype "bidirectional"))
    )
    (net (code "28") (name "FPGA_AUX1") (class "Default")
      (node (ref "CN18") (pin "4") (pinfunction "4_4") (pintype "passive"))
      (node (ref "U5") (pin "26") (pinfunction "PB04/USART1-CTS/SPI0-NPCS3/TC-CLK2_26") (pintype "bidirectional"))
      (node (ref "U9") (pin "64") (pinfunction "IO_L3N_MOSI_CSI_B_MISO0_2_64") (pintype "bidirectional"))
    )
    (net (code "29") (name "FPGA_AUX2") (class "Default")
      (node (ref "CN18") (pin "3") (pinfunction "3_3") (pintype "passive"))
      (node (ref "U5") (pin "40") (pinfunction "PA19/XOUT0/PWM6/USART0-TXD/SPI0-MOSI/SSC-TXCLK_40") (pintype "bidirectional"))
      (node (ref "U9") (pin "48") (pinfunction "IO_L48P_D7_2_48") (pintype "bidirectional"))
    )
    (net (code "30") (name "FPGA_CLK") (class "Default")
      (node (ref "R32") (pin "2") (pinfunction "2_2") (pintype "passive"))
      (node (ref "U9") (pin "50") (pinfunction "IO_L31N_GCLK30_D15_2_50") (pintype "bidirectional"))
    )
    (net (code "31") (name "FPGA_CONF") (class "Default")
      (node (ref "U10") (pin "1") (pinfunction "A_1") (pintype "bidirectional"))
      (node (ref "U5") (pin "33") (pinfunction "PA13/PWM2/NMI/USART0-CLK/SSC-RXCLK_33") (pintype "bidirectional"))
    )
    (net (code "32") (name "FPGA_DONE") (class "Default")
      (node (ref "U5") (pin "31") (pinfunction "PA12/XOUT32/PWM1/TC-B2/USART0-CTS/USART1-TXD_31") (pintype "bidirectional"))
      (node (ref "U9") (pin "71") (pinfunction "DONE_2_71") (pintype "bidirectional"))
    )
    (net (code "33") (name "FPGA_TCK") (class "Default")
      (node (ref "P1") (pin "1") (pinfunction "P$1_1") (pintype "passive"))
      (node (ref "U9") (pin "109") (pinfunction "TCK_109") (pintype "bidirectional"))
    )
    (net (code "34") (name "FPGA_TDI") (class "Default")
      (node (ref "P2") (pin "1") (pinfunction "P$1_1") (pintype "passive"))
      (node (ref "U9") (pin "110") (pinfunction "TDI_110") (pintype "bidirectional"))
    )
    (net (code "35") (name "FPGA_TDO") (class "Default")
      (node (ref "P3") (pin "1") (pinfunction "P$1_1") (pintype "passive"))
      (node (ref "U9") (pin "106") (pinfunction "TDO_106") (pintype "bidirectional"))
    )
    (net (code "36") (name "FPGA_TMS") (class "Default")
      (node (ref "P4") (pin "1") (pinfunction "P$1_1") (pintype "passive"))
      (node (ref "U9") (pin "107") (pinfunction "TMS_107") (pintype "bidirectional"))
    )
    (net (code "37") (name "GND") (class "Default")
      (node (ref "C1") (pin "2") (pinfunction "2_2") (pintype "passive"))
      (node (ref "C100") (pin "2") (pinfunction "2_2") (pintype "passive"))
      (node (ref "C101") (pin "2") (pinfunction "2_2") (pintype "passive"))
      (node (ref "C103") (pin "2") (pinfunction "2_2") (pintype "passive"))
      (node (ref "C107") (pin "2") (pinfunction "2_2") (pintype "passive"))
      (node (ref "C108") (pin "2") (pinfunction "2_2") (pintype "passive"))
      (node (ref "C109") (pin "2") (pinfunction "2_2") (pintype "passive"))
      (node (ref "C11") (pin "2") (pinfunction "2_2") (pintype "passive"))
      (node (ref "C110") (pin "N") (pinfunction "N_N") (pintype "passive"))
      (node (ref "C111") (pin "2") (pinfunction "2_2") (pintype "passive"))
      (node (ref "C112") (pin "2") (pinfunction "2_2") (pintype "passive"))
      (node (ref "C113") (pin "N") (pinfunction "N_N") (pintype "passive"))
      (node (ref "C114") (pin "2") (pinfunction "2_2") (pintype "passive"))
      (node (ref "C115") (pin "2") (pinfunction "2_2") (pintype "passive"))
      (node (ref "C116") (pin "2") (pinfunction "2_2") (pintype "passive"))
      (node (ref "C118") (pin "2") (pinfunction "2_2") (pintype "passive"))
      (node (ref "C12") (pin "2") (pinfunction "2_2") (pintype "passive"))
      (node (ref "C122") (pin "2") (pinfunction "2_2") (pintype "passive"))
      (node (ref "C123") (pin "2") (pinfunction "2_2") (pintype "passive"))
      (node (ref "C124") (pin "2") (pinfunction "2_2") (pintype "passive"))
      (node (ref "C125") (pin "N") (pinfunction "N_N") (pintype "passive"))
      (node (ref "C126") (pin "2") (pinfunction "2_2") (pintype "passive"))
      (node (ref "C127") (pin "2") (pinfunction "2_2") (pintype "passive"))
      (node (ref "C128") (pin "2") (pinfunction "2_2") (pintype "passive"))
      (node (ref "C129") (pin "2") (pinfunction "2_2") (pintype "passive"))
      (node (ref "C13") (pin "2") (pinfunction "2_2") (pintype "passive"))
      (node (ref "C130") (pin "2") (pinfunction "2_2") (pintype "passive"))
      (node (ref "C131") (pin "2") (pinfunction "2_2") (pintype "passive"))
      (node (ref "C132") (pin "2") (pinfunction "2_2") (pintype "passive"))
      (node (ref "C133") (pin "2") (pinfunction "2_2") (pintype "passive"))
      (node (ref "C134") (pin "2") (pinfunction "2_2") (pintype "passive"))
      (node (ref "C135") (pin "2") (pinfunction "2_2") (pintype "passive"))
      (node (ref "C136") (pin "2") (pinfunction "2_2") (pintype "passive"))
      (node (ref "C137") (pin "2") (pinfunction "2_2") (pintype "passive"))
      (node (ref "C138") (pin "2") (pinfunction "2_2") (pintype "passive"))
      (node (ref "C139") (pin "2") (pinfunction "2_2") (pintype "passive"))
      (node (ref "C140") (pin "2") (pinfunction "2_2") (pintype "passive"))
      (node (ref "C141") (pin "2") (pinfunction "2_2") (pintype "passive"))
      (node (ref "C142") (pin "2") (pinfunction "2_2") (pintype "passive"))
      (node (ref "C143") (pin "2") (pinfunction "2_2") (pintype "passive"))
      (node (ref "C144") (pin "2") (pinfunction "2_2") (pintype "passive"))
      (node (ref "C145") (pin "2") (pinfunction "2_2") (pintype "passive"))
      (node (ref "C146") (pin "2") (pinfunction "2_2") (pintype "passive"))
      (node (ref "C147") (pin "2") (pinfunction "2_2") (pintype "passive"))
      (node (ref "C148") (pin "2") (pinfunction "2_2") (pintype "passive"))
      (node (ref "C149") (pin "N") (pinfunction "N_N") (pintype "passive"))
      (node (ref "C15") (pin "2") (pinfunction "2_2") (pintype "passive"))
      (node (ref "C150") (pin "2") (pinfunction "2_2") (pintype "passive"))
      (node (ref "C151") (pin "2") (pinfunction "2_2") (pintype "passive"))
      (node (ref "C152") (pin "2") (pinfunction "2_2") (pintype "passive"))
      (node (ref "C154") (pin "2") (pinfunction "2_2") (pintype "passive"))
      (node (ref "C158") (pin "2") (pinfunction "2_2") (pintype "passive"))
      (node (ref "C159") (pin "2") (pinfunction "2_2") (pintype "passive"))
      (node (ref "C16") (pin "2") (pinfunction "2_2") (pintype "passive"))
      (node (ref "C160") (pin "2") (pinfunction "2_2") (pintype "passive"))
      (node (ref "C161") (pin "N") (pinfunction "N_N") (pintype "passive"))
      (node (ref "C162") (pin "2") (pinfunction "2_2") (pintype "passive"))
      (node (ref "C163") (pin "2") (pinfunction "2_2") (pintype "passive"))
      (node (ref "C164") (pin "2") (pinfunction "2_2") (pintype "passive"))
      (node (ref "C165") (pin "2") (pinfunction "2_2") (pintype "passive"))
      (node (ref "C17") (pin "2") (pinfunction "2_2") (pintype "passive"))
      (node (ref "C18") (pin "2") (pinfunction "2_2") (pintype "passive"))
      (node (ref "C19") (pin "2") (pinfunction "2_2") (pintype "passive"))
      (node (ref "C2") (pin "2") (pinfunction "2_2") (pintype "passive"))
      (node (ref "C20") (pin "2") (pinfunction "2_2") (pintype "passive"))
      (node (ref "C21") (pin "2") (pinfunction "2_2") (pintype "passive"))
      (node (ref "C22") (pin "2") (pinfunction "2_2") (pintype "passive"))
      (node (ref "C23") (pin "2") (pinfunction "2_2") (pintype "passive"))
      (node (ref "C25") (pin "2") (pinfunction "2_2") (pintype "passive"))
      (node (ref "C26") (pin "2") (pinfunction "2_2") (pintype "passive"))
      (node (ref "C27") (pin "2") (pinfunction "2_2") (pintype "passive"))
      (node (ref "C28") (pin "2") (pinfunction "2_2") (pintype "passive"))
      (node (ref "C29") (pin "2") (pinfunction "2_2") (pintype "passive"))
      (node (ref "C3") (pin "N") (pinfunction "N_N") (pintype "passive"))
      (node (ref "C30") (pin "2") (pinfunction "2_2") (pintype "passive"))
      (node (ref "C31") (pin "2") (pinfunction "2_2") (pintype "passive"))
      (node (ref "C32") (pin "2") (pinfunction "2_2") (pintype "passive"))
      (node (ref "C33") (pin "2") (pinfunction "2_2") (pintype "passive"))
      (node (ref "C34") (pin "2") (pinfunction "2_2") (pintype "passive"))
      (node (ref "C35") (pin "2") (pinfunction "2_2") (pintype "passive"))
      (node (ref "C36") (pin "2") (pinfunction "2_2") (pintype "passive"))
      (node (ref "C37") (pin "2") (pinfunction "2_2") (pintype "passive"))
      (node (ref "C38") (pin "2") (pinfunction "2_2") (pintype "passive"))
      (node (ref "C39") (pin "2") (pinfunction "2_2") (pintype "passive"))
      (node (ref "C4") (pin "N") (pinfunction "N_N") (pintype "passive"))
      (node (ref "C40") (pin "2") (pinfunction "2_2") (pintype "passive"))
      (node (ref "C41") (pin "2") (pinfunction "2_2") (pintype "passive"))
      (node (ref "C42") (pin "2") (pinfunction "2_2") (pintype "passive"))
      (node (ref "C43") (pin "2") (pinfunction "2_2") (pintype "passive"))
      (node (ref "C44") (pin "2") (pinfunction "2_2") (pintype "passive"))
      (node (ref "C45") (pin "2") (pinfunction "2_2") (pintype "passive"))
      (node (ref "C46") (pin "2") (pinfunction "2_2") (pintype "passive"))
      (node (ref "C47") (pin "2") (pinfunction "2_2") (pintype "passive"))
      (node (ref "C48") (pin "2") (pinfunction "2_2") (pintype "passive"))
      (node (ref "C49") (pin "2") (pinfunction "2_2") (pintype "passive"))
      (node (ref "C5") (pin "2") (pinfunction "2_2") (pintype "passive"))
      (node (ref "C50") (pin "2") (pinfunction "2_2") (pintype "passive"))
      (node (ref "C51") (pin "2") (pinfunction "2_2") (pintype "passive"))
      (node (ref "C52") (pin "2") (pinfunction "2_2") (pintype "passive"))
      (node (ref "C53") (pin "2") (pinfunction "2_2") (pintype "passive"))
      (node (ref "C54") (pin "2") (pinfunction "2_2") (pintype "passive"))
      (node (ref "C55") (pin "GND") (pinfunction "GND_GND") (pintype "passive"))
      (node (ref "C56") (pin "GND") (pinfunction "GND_GND") (pintype "passive"))
      (node (ref "C57") (pin "2") (pinfunction "2_2") (pintype "passive"))
      (node (ref "C58") (pin "GND") (pinfunction "GND_GND") (pintype "passive"))
      (node (ref "C59") (pin "2") (pinfunction "2_2") (pintype "passive"))
      (node (ref "C6") (pin "2") (pinfunction "2_2") (pintype "passive"))
      (node (ref "C60") (pin "GND") (pinfunction "GND_GND") (pintype "passive"))
      (node (ref "C61") (pin "2") (pinfunction "2_2") (pintype "passive"))
      (node (ref "C62") (pin "GND") (pinfunction "GND_GND") (pintype "passive"))
      (node (ref "C63") (pin "2") (pinfunction "2_2") (pintype "passive"))
      (node (ref "C64") (pin "2") (pinfunction "2_2") (pintype "passive"))
      (node (ref "C65") (pin "2") (pinfunction "2_2") (pintype "passive"))
      (node (ref "C66") (pin "2") (pinfunction "2_2") (pintype "passive"))
      (node (ref "C67") (pin "2") (pinfunction "2_2") (pintype "passive"))
      (node (ref "C68") (pin "N") (pinfunction "N_N") (pintype "passive"))
      (node (ref "C69") (pin "2") (pinfunction "2_2") (pintype "passive"))
      (node (ref "C7") (pin "N") (pinfunction "N_N") (pintype "passive"))
      (node (ref "C70") (pin "2") (pinfunction "2_2") (pintype "passive"))
      (node (ref "C71") (pin "2") (pinfunction "2_2") (pintype "passive"))
      (node (ref "C73") (pin "2") (pinfunction "2_2") (pintype "passive"))
      (node (ref "C77") (pin "2") (pinfunction "2_2") (pintype "passive"))
      (node (ref "C78") (pin "2") (pinfunction "2_2") (pintype "passive"))
      (node (ref "C79") (pin "2") (pinfunction "2_2") (pintype "passive"))
      (node (ref "C8") (pin "2") (pinfunction "2_2") (pintype "passive"))
      (node (ref "C80") (pin "N") (pinfunction "N_N") (pintype "passive"))
      (node (ref "C81") (pin "2") (pinfunction "2_2") (pintype "passive"))
      (node (ref "C82") (pin "2") (pinfunction "2_2") (pintype "passive"))
      (node (ref "C83") (pin "N") (pinfunction "N_N") (pintype "passive"))
      (node (ref "C84") (pin "2") (pinfunction "2_2") (pintype "passive"))
      (node (ref "C85") (pin "2") (pinfunction "2_2") (pintype "passive"))
      (node (ref "C86") (pin "2") (pinfunction "2_2") (pintype "passive"))
      (node (ref "C88") (pin "2") (pinfunction "2_2") (pintype "passive"))
      (node (ref "C9") (pin "2") (pinfunction "2_2") (pintype "passive"))
      (node (ref "C92") (pin "2") (pinfunction "2_2") (pintype "passive"))
      (node (ref "C93") (pin "2") (pinfunction "2_2") (pintype "passive"))
      (node (ref "C94") (pin "2") (pinfunction "2_2") (pintype "passive"))
      (node (ref "C95") (pin "N") (pinfunction "N_N") (pintype "passive"))
      (node (ref "C96") (pin "2") (pinfunction "2_2") (pintype "passive"))
      (node (ref "C97") (pin "2") (pinfunction "2_2") (pintype "passive"))
      (node (ref "C98") (pin "N") (pinfunction "N_N") (pintype "passive"))
      (node (ref "C99") (pin "2") (pinfunction "2_2") (pintype "passive"))
      (node (ref "CN1") (pin "N") (pinfunction "N_N") (pintype "passive"))
      (node (ref "CN10") (pin "2") (pinfunction "2_2") (pintype "passive"))
      (node (ref "CN11") (pin "1.5") (pinfunction "GND_1.5") (pintype "bidirectional"))
      (node (ref "CN11") (pin "2.1") (pinfunction "GND_2.1") (pintype "bidirectional"))
      (node (ref "CN11") (pin "S1") (pinfunction "S1_S1") (pintype "bidirectional"))
      (node (ref "CN11") (pin "S2") (pinfunction "S2_S2") (pintype "bidirectional"))
      (node (ref "CN12") (pin "2") (pinfunction "2_2") (pintype "passive"))
      (node (ref "CN13") (pin "1.5") (pinfunction "GND_1.5") (pintype "bidirectional"))
      (node (ref "CN13") (pin "2.1") (pinfunction "GND_2.1") (pintype "bidirectional"))
      (node (ref "CN13") (pin "S1") (pinfunction "S1_S1") (pintype "bidirectional"))
      (node (ref "CN13") (pin "S2") (pinfunction "S2_S2") (pintype "bidirectional"))
      (node (ref "CN14") (pin "2") (pinfunction "2_2") (pintype "passive"))
      (node (ref "CN15") (pin "1.5") (pinfunction "GND_1.5") (pintype "bidirectional"))
      (node (ref "CN15") (pin "2.1") (pinfunction "GND_2.1") (pintype "bidirectional"))
      (node (ref "CN15") (pin "S1") (pinfunction "S1_S1") (pintype "bidirectional"))
      (node (ref "CN15") (pin "S2") (pinfunction "S2_S2") (pintype "bidirectional"))
      (node (ref "CN16") (pin "2") (pinfunction "2_2") (pintype "passive"))
      (node (ref "CN17") (pin "5") (pinfunction "5_5") (pintype "passive"))
      (node (ref "CN18") (pin "1") (pinfunction "1_1") (pintype "passive"))
      (node (ref "CN2") (pin "1") (pinfunction "1_1") (pintype "passive"))
      (node (ref "CN2") (pin "3") (pinfunction "3_3") (pintype "passive"))
      (node (ref "CN2") (pin "7") (pinfunction "7_7") (pintype "passive"))
      (node (ref "CN3") (pin "5") (pinfunction "GND_5") (pintype "passive"))
      (node (ref "CN3") (pin "S1") (pinfunction "S1_S1") (pintype "passive"))
      (node (ref "CN3") (pin "S2") (pinfunction "S2_S2") (pintype "passive"))
      (node (ref "CN4") (pin "10") (pinfunction "GND_10") (pintype "passive"))
      (node (ref "CN4") (pin "2") (pinfunction "GND_2") (pintype "passive"))
      (node (ref "CN5") (pin "4") (pinfunction "4_4") (pintype "passive"))
      (node (ref "CN6") (pin "8") (pinfunction "8_8") (pintype "passive"))
      (node (ref "CN7") (pin "10") (pinfunction "GND_10") (pintype "bidirectional"))
      (node (ref "CN8") (pin "2") (pinfunction "2_2") (pintype "passive"))
      (node (ref "CN9") (pin "1.5") (pinfunction "GND_1.5") (pintype "bidirectional"))
      (node (ref "CN9") (pin "2.1") (pinfunction "GND_2.1") (pintype "bidirectional"))
      (node (ref "CN9") (pin "S1") (pinfunction "S1_S1") (pintype "bidirectional"))
      (node (ref "CN9") (pin "S2") (pinfunction "S2_S2") (pintype "bidirectional"))
      (node (ref "D1") (pin "A") (pinfunction "A_A") (pintype "passive"))
      (node (ref "D2") (pin "A") (pinfunction "A_A") (pintype "passive"))
      (node (ref "D4") (pin "A") (pinfunction "A_A") (pintype "passive"))
      (node (ref "J1") (pin "1") (pinfunction "1_1") (pintype "passive"))
      (node (ref "J1") (pin "3") (pinfunction "3_3") (pintype "passive"))
      (node (ref "J1") (pin "5") (pinfunction "5_5") (pintype "passive"))
      (node (ref "J1") (pin "7") (pinfunction "7_7") (pintype "passive"))
      (node (ref "J1") (pin "9") (pinfunction "9_9") (pintype "passive"))
      (node (ref "LED1") (pin "K") (pinfunction "K_K") (pintype "passive"))
      (node (ref "LED10") (pin "K") (pinfunction "K_K") (pintype "passive"))
      (node (ref "LED2") (pin "K") (pinfunction "K_K") (pintype "passive"))
      (node (ref "LED4") (pin "K") (pinfunction "K_K") (pintype "passive"))
      (node (ref "LED5") (pin "K") (pinfunction "K_K") (pintype "passive"))
      (node (ref "LED6") (pin "K") (pinfunction "K_K") (pintype "passive"))
      (node (ref "LED7") (pin "K") (pinfunction "K_K") (pintype "passive"))
      (node (ref "LED8") (pin "K") (pinfunction "K_K") (pintype "passive"))
      (node (ref "LED9") (pin "K") (pinfunction "K_K") (pintype "passive"))
      (node (ref "R10") (pin "1") (pinfunction "1_1") (pintype "passive"))
      (node (ref "R105") (pin "1") (pinfunction "1_1") (pintype "passive"))
      (node (ref "R11") (pin "1") (pinfunction "1_1") (pintype "passive"))
      (node (ref "R110") (pin "1") (pinfunction "1_1") (pintype "passive"))
      (node (ref "R112") (pin "1") (pinfunction "1_1") (pintype "passive"))
      (node (ref "R118") (pin "1") (pinfunction "1_1") (pintype "passive"))
      (node (ref "R12") (pin "1") (pinfunction "1_1") (pintype "passive"))
      (node (ref "R15") (pin "1") (pinfunction "1_1") (pintype "passive"))
      (node (ref "R17") (pin "1") (pinfunction "1_1") (pintype "passive"))
      (node (ref "R19") (pin "1") (pinfunction "1_1") (pintype "passive"))
      (node (ref "R21") (pin "1") (pinfunction "1_1") (pintype "passive"))
      (node (ref "R22") (pin "1") (pinfunction "1_1") (pintype "passive"))
      (node (ref "R25") (pin "1") (pinfunction "1_1") (pintype "passive"))
      (node (ref "R26") (pin "1") (pinfunction "1_1") (pintype "passive"))
      (node (ref "R27") (pin "1") (pinfunction "1_1") (pintype "passive"))
      (node (ref "R28") (pin "1") (pinfunction "1_1") (pintype "passive"))
      (node (ref "R44") (pin "1") (pinfunction "1_1") (pintype "passive"))
      (node (ref "R5") (pin "1") (pinfunction "1_1") (pintype "passive"))
      (node (ref "R53") (pin "1") (pinfunction "1_1") (pintype "passive"))
      (node (ref "R60") (pin "1") (pinfunction "1_1") (pintype "passive"))
      (node (ref "R63") (pin "1") (pinfunction "1_1") (pintype "passive"))
      (node (ref "R67") (pin "1") (pinfunction "1_1") (pintype "passive"))
      (node (ref "R7") (pin "1") (pinfunction "1_1") (pintype "passive"))
      (node (ref "R71") (pin "1") (pinfunction "1_1") (pintype "passive"))
      (node (ref "R75") (pin "1") (pinfunction "1_1") (pintype "passive"))
      (node (ref "R78") (pin "1") (pinfunction "1_1") (pintype "passive"))
      (node (ref "R79") (pin "1") (pinfunction "1_1") (pintype "passive"))
      (node (ref "R80") (pin "1") (pinfunction "1_1") (pintype "passive"))
      (node (ref "R81") (pin "1") (pinfunction "1_1") (pintype "passive"))
      (node (ref "R82") (pin "1") (pinfunction "1_1") (pintype "passive"))
      (node (ref "R83") (pin "1") (pinfunction "1_1") (pintype "passive"))
      (node (ref "R84") (pin "1") (pinfunction "1_1") (pintype "passive"))
      (node (ref "R85") (pin "1") (pinfunction "1_1") (pintype "passive"))
      (node (ref "R86") (pin "1") (pinfunction "1_1") (pintype "passive"))
      (node (ref "R87") (pin "1") (pinfunction "1_1") (pintype "passive"))
      (node (ref "R88") (pin "1") (pinfunction "1_1") (pintype "passive"))
      (node (ref "R89") (pin "1") (pinfunction "1_1") (pintype "passive"))
      (node (ref "R90") (pin "1") (pinfunction "1_1") (pintype "passive"))
      (node (ref "R91") (pin "1") (pinfunction "1_1") (pintype "passive"))
      (node (ref "R92") (pin "1") (pinfunction "1_1") (pintype "passive"))
      (node (ref "R93") (pin "1") (pinfunction "1_1") (pintype "passive"))
      (node (ref "R94") (pin "1") (pinfunction "1_1") (pintype "passive"))
      (node (ref "R95") (pin "1") (pinfunction "1_1") (pintype "passive"))
      (node (ref "R96") (pin "1") (pinfunction "1_1") (pintype "passive"))
      (node (ref "R97") (pin "1") (pinfunction "1_1") (pintype "passive"))
      (node (ref "R98") (pin "1") (pinfunction "1_1") (pintype "passive"))
      (node (ref "SW2") (pin "A1") (pinfunction "A1_A1") (pintype "passive"))
      (node (ref "SW2") (pin "A2") (pinfunction "A2_A2") (pintype "passive"))
      (node (ref "SW3") (pin "A1") (pinfunction "A1_A1") (pintype "passive"))
      (node (ref "SW3") (pin "A2") (pinfunction "A2_A2") (pintype "passive"))
      (node (ref "U1") (pin "3") (pinfunction "GND_3") (pintype "input"))
      (node (ref "U1") (pin "7") (pinfunction "A0_7") (pintype "input"))
      (node (ref "U1") (pin "8") (pinfunction "A1_8") (pintype "input"))
      (node (ref "U10") (pin "3") (pinfunction "GND_3") (pintype "bidirectional"))
      (node (ref "U11") (pin "7") (pinfunction "GND_7") (pintype "bidirectional"))
      (node (ref "U12") (pin "1") (pinfunction "R2_1") (pintype "bidirectional"))
      (node (ref "U13") (pin "2") (pinfunction "GND_2") (pintype "bidirectional"))
      (node (ref "U13") (pin "4") (pinfunction "GND_4") (pintype "bidirectional"))
      (node (ref "U14") (pin "23") (pinfunction "GND_C_23") (pintype "bidirectional"))
      (node (ref "U14") (pin "24") (pinfunction "GND_24") (pintype "bidirectional"))
      (node (ref "U14") (pin "25") (pinfunction "GND_25") (pintype "bidirectional"))
      (node (ref "U14") (pin "31") (pinfunction "GND_B_31") (pintype "bidirectional"))
      (node (ref "U14") (pin "32") (pinfunction "GND_A_32") (pintype "bidirectional"))
      (node (ref "U14") (pin "8") (pinfunction "GND_8") (pintype "bidirectional"))
      (node (ref "U15") (pin "2") (pinfunction "GND_2") (pintype "input"))
      (node (ref "U16") (pin "2") (pinfunction "GND_2") (pintype "input"))
      (node (ref "U17") (pin "23") (pinfunction "GND_C_23") (pintype "bidirectional"))
      (node (ref "U17") (pin "24") (pinfunction "GND_24") (pintype "bidirectional"))
      (node (ref "U17") (pin "25") (pinfunction "GND_25") (pintype "bidirectional"))
      (node (ref "U17") (pin "31") (pinfunction "GND_B_31") (pintype "bidirectional"))
      (node (ref "U17") (pin "32") (pinfunction "GND_A_32") (pintype "bidirectional"))
      (node (ref "U17") (pin "8") (pinfunction "GND_8") (pintype "bidirectional"))
      (node (ref "U18") (pin "2") (pinfunction "GND_2") (pintype "input"))
      (node (ref "U19") (pin "2") (pinfunction "GND_2") (pintype "input"))
      (node (ref "U2") (pin "10") (pinfunction "GND_10") (pintype "bidirectional"))
      (node (ref "U2") (pin "18") (pinfunction "GND_18") (pintype "bidirectional"))
      (node (ref "U2") (pin "27") (pinfunction "GND_27") (pintype "bidirectional"))
      (node (ref "U2") (pin "PAD") (pinfunction "PAD_PAD") (pintype "bidirectional"))
      (node (ref "U20") (pin "23") (pinfunction "GND_C_23") (pintype "bidirectional"))
      (node (ref "U20") (pin "24") (pinfunction "GND_24") (pintype "bidirectional"))
      (node (ref "U20") (pin "25") (pinfunction "GND_25") (pintype "bidirectional"))
      (node (ref "U20") (pin "31") (pinfunction "GND_B_31") (pintype "bidirectional"))
      (node (ref "U20") (pin "32") (pinfunction "GND_A_32") (pintype "bidirectional"))
      (node (ref "U20") (pin "8") (pinfunction "GND_8") (pintype "bidirectional"))
      (node (ref "U21") (pin "2") (pinfunction "GND_2") (pintype "input"))
      (node (ref "U22") (pin "2") (pinfunction "GND_2") (pintype "input"))
      (node (ref "U23") (pin "23") (pinfunction "GND_C_23") (pintype "bidirectional"))
      (node (ref "U23") (pin "24") (pinfunction "GND_24") (pintype "bidirectional"))
      (node (ref "U23") (pin "25") (pinfunction "GND_25") (pintype "bidirectional"))
      (node (ref "U23") (pin "31") (pinfunction "GND_B_31") (pintype "bidirectional"))
      (node (ref "U23") (pin "32") (pinfunction "GND_A_32") (pintype "bidirectional"))
      (node (ref "U23") (pin "8") (pinfunction "GND_8") (pintype "bidirectional"))
      (node (ref "U24") (pin "2") (pinfunction "GND_2") (pintype "input"))
      (node (ref "U25") (pin "2") (pinfunction "GND_2") (pintype "input"))
      (node (ref "U26") (pin "10") (pinfunction "SI_10") (pintype "bidirectional"))
      (node (ref "U26") (pin "13") (pinfunction "C_13") (pintype "bidirectional"))
      (node (ref "U26") (pin "14") (pinfunction "D_14") (pintype "bidirectional"))
      (node (ref "U26") (pin "15") (pinfunction "CKINH_15") (pintype "bidirectional"))
      (node (ref "U26") (pin "3") (pinfunction "E_3") (pintype "bidirectional"))
      (node (ref "U26") (pin "8") (pinfunction "GND_8") (pintype "bidirectional"))
      (node (ref "U27") (pin "15") (pinfunction "CKINH_15") (pintype "bidirectional"))
      (node (ref "U27") (pin "5") (pinfunction "G_5") (pintype "bidirectional"))
      (node (ref "U27") (pin "6") (pinfunction "H_6") (pintype "bidirectional"))
      (node (ref "U27") (pin "8") (pinfunction "GND_8") (pintype "bidirectional"))
      (node (ref "U28") (pin "2") (pinfunction "A_2") (pintype "passive"))
      (node (ref "U29") (pin "12") (pinfunction "NC_12") (pintype "bidirectional"))
      (node (ref "U29") (pin "13") (pinfunction "NC_13") (pintype "bidirectional"))
      (node (ref "U29") (pin "15") (pinfunction "AGND_15") (pintype "bidirectional"))
      (node (ref "U29") (pin "2") (pinfunction "AGND_2") (pintype "bidirectional"))
      (node (ref "U29") (pin "20") (pinfunction "BDGND_20") (pintype "bidirectional"))
      (node (ref "U29") (pin "23") (pinfunction "REFM_23") (pintype "bidirectional"))
      (node (ref "U29") (pin "5") (pinfunction "AINM_5") (pintype "bidirectional"))
      (node (ref "U29") (pin "6") (pinfunction "NC_6") (pintype "bidirectional"))
      (node (ref "U29") (pin "7") (pinfunction "NC_7") (pintype "bidirectional"))
      (node (ref "U29") (pin "P") (pinfunction "AGND_P") (pintype "bidirectional"))
      (node (ref "U3") (pin "2") (pinfunction "GND_2") (pintype "bidirectional"))
      (node (ref "U30") (pin "10") (pinfunction "SI_10") (pintype "bidirectional"))
      (node (ref "U30") (pin "13") (pinfunction "C_13") (pintype "bidirectional"))
      (node (ref "U30") (pin "14") (pinfunction "D_14") (pintype "bidirectional"))
      (node (ref "U30") (pin "15") (pinfunction "CKINH_15") (pintype "bidirectional"))
      (node (ref "U30") (pin "8") (pinfunction "GND_8") (pintype "bidirectional"))
      (node (ref "U31") (pin "15") (pinfunction "CKINH_15") (pintype "bidirectional"))
      (node (ref "U31") (pin "8") (pinfunction "GND_8") (pintype "bidirectional"))
      (node (ref "U32") (pin "2") (pinfunction "A_2") (pintype "passive"))
      (node (ref "U33") (pin "12") (pinfunction "NC_12") (pintype "bidirectional"))
      (node (ref "U33") (pin "13") (pinfunction "NC_13") (pintype "bidirectional"))
      (node (ref "U33") (pin "15") (pinfunction "AGND_15") (pintype "bidirectional"))
      (node (ref "U33") (pin "2") (pinfunction "AGND_2") (pintype "bidirectional"))
      (node (ref "U33") (pin "20") (pinfunction "BDGND_20") (pintype "bidirectional"))
      (node (ref "U33") (pin "23") (pinfunction "REFM_23") (pintype "bidirectional"))
      (node (ref "U33") (pin "5") (pinfunction "AINM_5") (pintype "bidirectional"))
      (node (ref "U33") (pin "6") (pinfunction "NC_6") (pintype "bidirectional"))
      (node (ref "U33") (pin "7") (pinfunction "NC_7") (pintype "bidirectional"))
      (node (ref "U33") (pin "P") (pinfunction "AGND_P") (pintype "bidirectional"))
      (node (ref "U34") (pin "1") (pinfunction "R2_1") (pintype "bidirectional"))
      (node (ref "U35") (pin "1") (pinfunction "R2_1") (pintype "bidirectional"))
      (node (ref "U36") (pin "3") (pinfunction "GND_3") (pintype "input"))
      (node (ref "U36") (pin "7") (pinfunction "A0_7") (pintype "input"))
      (node (ref "U36") (pin "8") (pinfunction "A1_8") (pintype "input"))
      (node (ref "U37") (pin "23") (pinfunction "GND_C_23") (pintype "bidirectional"))
      (node (ref "U37") (pin "24") (pinfunction "GND_24") (pintype "bidirectional"))
      (node (ref "U37") (pin "25") (pinfunction "GND_25") (pintype "bidirectional"))
      (node (ref "U37") (pin "31") (pinfunction "GND_B_31") (pintype "bidirectional"))
      (node (ref "U37") (pin "32") (pinfunction "GND_A_32") (pintype "bidirectional"))
      (node (ref "U37") (pin "8") (pinfunction "GND_8") (pintype "bidirectional"))
      (node (ref "U38") (pin "4") (pinfunction "GND_4") (pintype "bidirectional"))
      (node (ref "U39") (pin "2") (pinfunction "GND_2") (pintype "bidirectional"))
      (node (ref "U4") (pin "2") (pinfunction "V-_2") (pintype "bidirectional"))
      (node (ref "U40") (pin "4") (pinfunction "GND_4") (pintype "bidirectional"))
      (node (ref "U41") (pin "4") (pinfunction "GND_4") (pintype "bidirectional"))
      (node (ref "U5") (pin "1") (pinfunction "GND_1") (pintype "bidirectional"))
      (node (ref "U5") (pin "17") (pinfunction "GNDANA_17") (pintype "bidirectional"))
      (node (ref "U5") (pin "23") (pinfunction "GND_23") (pintype "bidirectional"))
      (node (ref "U5") (pin "49") (pinfunction "GND_49") (pintype "bidirectional"))
      (node (ref "U6") (pin "7") (pinfunction "GND_7") (pintype "bidirectional"))
      (node (ref "U7") (pin "4") (pinfunction "GND_4") (pintype "bidirectional"))
      (node (ref "U8") (pin "3") (pinfunction "GND_3") (pintype "bidirectional"))
      (node (ref "U9") (pin "108") (pinfunction "GND_108") (pintype "bidirectional"))
      (node (ref "U9") (pin "113") (pinfunction "GND_113") (pintype "bidirectional"))
      (node (ref "U9") (pin "13") (pinfunction "GND_13") (pintype "bidirectional"))
      (node (ref "U9") (pin "130") (pinfunction "GND_130") (pintype "bidirectional"))
      (node (ref "U9") (pin "136") (pinfunction "GND_136") (pintype "bidirectional"))
      (node (ref "U9") (pin "25") (pinfunction "GND_25") (pintype "bidirectional"))
      (node (ref "U9") (pin "3") (pinfunction "GND_3") (pintype "bidirectional"))
      (node (ref "U9") (pin "49") (pinfunction "GND_49") (pintype "bidirectional"))
      (node (ref "U9") (pin "54") (pinfunction "GND_54") (pintype "bidirectional"))
      (node (ref "U9") (pin "68") (pinfunction "GND_68") (pintype "bidirectional"))
      (node (ref "U9") (pin "73") (pinfunction "SUSPEND_73") (pintype "bidirectional"))
      (node (ref "U9") (pin "77") (pinfunction "GND_77") (pintype "bidirectional"))
      (node (ref "U9") (pin "91") (pinfunction "GND_91") (pintype "bidirectional"))
      (node (ref "U9") (pin "96") (pinfunction "GND_96") (pintype "bidirectional"))
      (node (ref "X1") (pin "2") (pinfunction "GND_2") (pintype "bidirectional"))
    )
    (net (code "38") (name "IRDA_RX") (class "Default")
      (node (ref "U5") (pin "59") (pinfunction "PA24/INT4/USART1-RXD/SPI0-NPCS0/PWM1_59") (pintype "bidirectional"))
      (node (ref "U6") (pin "4") (pinfunction "RXD_4") (pintype "bidirectional"))
    )
    (net (code "39") (name "IRDA_SD") (class "Default")
      (node (ref "U5") (pin "54") (pinfunction "PB08/SSC-RXFRM/USART1-DTR/ABDAC-DATA1_54") (pintype "bidirectional"))
      (node (ref "U6") (pin "5") (pinfunction "SD_5") (pintype "bidirectional"))
    )
    (net (code "40") (name "IRDA_TX") (class "Default")
      (node (ref "U5") (pin "47") (pinfunction "PA23/INT3/USART1-TXD/SPI0-NPCS1/PWM0_47") (pintype "bidirectional"))
      (node (ref "U6") (pin "3") (pinfunction "TXD_3") (pintype "bidirectional"))
    )
    (net (code "41") (name "LED1") (class "Default")
      (node (ref "R40") (pin "2") (pinfunction "2_2") (pintype "passive"))
      (node (ref "U5") (pin "24") (pinfunction "PB02/TC-A1/USART1-TXD_24") (pintype "bidirectional"))
    )
    (net (code "42") (name "LED2") (class "Default")
      (node (ref "R41") (pin "2") (pinfunction "2_2") (pintype "passive"))
      (node (ref "U5") (pin "25") (pinfunction "PB03/TC-B1/USART1-RXD_25") (pintype "bidirectional"))
    )
    (net (code "43") (name "LED_CLK") (class "Default")
      (node (ref "U11") (pin "8") (pinfunction "CK_8") (pintype "bidirectional"))
      (node (ref "U9") (pin "131") (pinfunction "IO_L35N_GCLK16_0_131") (pintype "bidirectional"))
    )
    (net (code "44") (name "LED_DO") (class "Default")
      (node (ref "U11") (pin "2") (pinfunction "B_2") (pintype "bidirectional"))
      (node (ref "U9") (pin "126") (pinfunction "IO_L36N_GCLK14_0_126") (pintype "bidirectional"))
    )
    (net (code "45") (name "MCU_CLK") (class "Default")
      (node (ref "R31") (pin "2") (pinfunction "2_2") (pintype "passive"))
      (node (ref "U5") (pin "41") (pinfunction "PA28/XIN1/USART0-CLK/PWM4/SPI0-MISO/ABDAC-DATAN0_41") (pintype "bidirectional"))
    )
    (net (code "46") (name "MOT1_2_5V") (class "Default")
      (node (ref "C135") (pin "1") (pinfunction "1_1") (pintype "passive"))
      (node (ref "C136") (pin "1") (pinfunction "1_1") (pintype "passive"))
      (node (ref "C138") (pin "1") (pinfunction "1_1") (pintype "passive"))
      (node (ref "C81") (pin "1") (pinfunction "1_1") (pintype "passive"))
      (node (ref "C82") (pin "1") (pinfunction "1_1") (pintype "passive"))
      (node (ref "C96") (pin "1") (pinfunction "1_1") (pintype "passive"))
      (node (ref "C97") (pin "1") (pinfunction "1_1") (pintype "passive"))
      (node (ref "R101") (pin "2") (pinfunction "2_2") (pintype "passive"))
      (node (ref "U15") (pin "3") (pinfunction "V+_3") (pintype "input"))
      (node (ref "U16") (pin "3") (pinfunction "V+_3") (pintype "input"))
      (node (ref "U18") (pin "3") (pinfunction "V+_3") (pintype "input"))
      (node (ref "U19") (pin "3") (pinfunction "V+_3") (pintype "input"))
      (node (ref "U29") (pin "1") (pinfunction "+VA_1") (pintype "bidirectional"))
      (node (ref "U29") (pin "14") (pinfunction "+VA_14") (pintype "bidirectional"))
    )
    (net (code "47") (name "MOT1_2_CLK") (class "Default")
      (node (ref "U26") (pin "2") (pinfunction "CK_2") (pintype "bidirectional"))
      (node (ref "U27") (pin "2") (pinfunction "CK_2") (pintype "bidirectional"))
      (node (ref "U9") (pin "94") (pinfunction "IO_L40N_GCLK10_1_94") (pintype "bidirectional"))
    )
    (net (code "48") (name "MOT1_2_CUR_REF") (class "Default")
      (node (ref "C134") (pin "1") (pinfunction "1_1") (pintype "passive"))
      (node (ref "C137") (pin "1") (pinfunction "1_1") (pintype "passive"))
      (node (ref "R100") (pin "1") (pinfunction "1_1") (pintype "passive"))
      (node (ref "U15") (pin "1") (pinfunction "REF_1") (pintype "input"))
      (node (ref "U16") (pin "1") (pinfunction "REF_1") (pintype "input"))
      (node (ref "U18") (pin "1") (pinfunction "REF_1") (pintype "input"))
      (node (ref "U19") (pin "1") (pinfunction "REF_1") (pintype "input"))
      (node (ref "U28") (pin "1") (pinfunction "K_1") (pintype "passive"))
      (node (ref "U29") (pin "24") (pinfunction "REFP_24") (pintype "bidirectional"))
    )
    (net (code "49") (name "MOT1_2_EN_SENSOR") (class "Default")
      (node (ref "R110") (pin "2") (pinfunction "2_2") (pintype "passive"))
      (node (ref "U34") (pin "5") (pinfunction "EN_5") (pintype "bidirectional"))
      (node (ref "U9") (pin "84") (pinfunction "IO_L43N_GCLK4_1_84") (pintype "bidirectional"))
    )
    (net (code "50") (name "MOT1_A_5") (class "Default")
      (node (ref "CN10") (pin "3") (pinfunction "3_3") (pintype "passive"))
      (node (ref "R78") (pin "2") (pinfunction "2_2") (pintype "passive"))
      (node (ref "U26") (pin "12") (pinfunction "B_12") (pintype "bidirectional"))
    )
    (net (code "51") (name "MOT1_B_5") (class "Default")
      (node (ref "CN10") (pin "1") (pinfunction "1_1") (pintype "passive"))
      (node (ref "R79") (pin "2") (pinfunction "2_2") (pintype "passive"))
      (node (ref "U26") (pin "11") (pinfunction "A_11") (pintype "bidirectional"))
    )
    (net (code "52") (name "MOT1_CUR_V") (class "Default")
      (node (ref "U15") (pin "6") (pinfunction "OUT_6") (pintype "output"))
      (node (ref "U29") (pin "10") (pinfunction "CH1_10") (pintype "bidirectional"))
    )
    (net (code "53") (name "MOT1_CUR_W") (class "Default")
      (node (ref "U16") (pin "6") (pinfunction "OUT_6") (pintype "output"))
      (node (ref "U29") (pin "11") (pinfunction "CH0_11") (pintype "bidirectional"))
    )
    (net (code "54") (name "MOT1_GND") (class "Default")
      (node (ref "C72") (pin "2") (pinfunction "2_2") (pintype "passive"))
      (node (ref "R62") (pin "1") (pinfunction "1_1") (pintype "passive"))
      (node (ref "R63") (pin "2") (pinfunction "2_2") (pintype "passive"))
      (node (ref "U14") (pin "12") (pinfunction "M2_12") (pintype "bidirectional"))
      (node (ref "U14") (pin "9") (pinfunction "AGND_9") (pintype "bidirectional"))
    )
    (net (code "55") (name "MOT1_OUT_U") (class "Default")
      (node (ref "C74") (pin "2") (pinfunction "2_2") (pintype "passive"))
      (node (ref "CN9") (pin "1.10") (pinfunction "U_1.10") (pintype "bidirectional"))
      (node (ref "CN9") (pin "1.11") (pinfunction "U_1.11") (pintype "bidirectional"))
      (node (ref "CN9") (pin "2.5") (pinfunction "U_2.5") (pintype "bidirectional"))
      (node (ref "U14") (pin "33") (pinfunction "OUT_A_33") (pintype "bidirectional"))
    )
    (net (code "56") (name "MOT1_OUT_V") (class "Default")
      (node (ref "CN9") (pin "1.8") (pinfunction "V_1.8") (pintype "bidirectional"))
      (node (ref "CN9") (pin "1.9") (pinfunction "V_1.9") (pintype "bidirectional"))
      (node (ref "CN9") (pin "2.6") (pinfunction "V_2.6") (pintype "bidirectional"))
      (node (ref "R64") (pin "2") (pinfunction "2_2") (pintype "passive"))
      (node (ref "U15") (pin "5") (pinfunction "VIN-_5") (pintype "input"))
    )
    (net (code "57") (name "MOT1_OUT_W") (class "Default")
      (node (ref "CN9") (pin "1.6") (pinfunction "W_1.6") (pintype "bidirectional"))
      (node (ref "CN9") (pin "1.7") (pinfunction "W_1.7") (pintype "bidirectional"))
      (node (ref "CN9") (pin "2.7") (pinfunction "W_2.7") (pintype "bidirectional"))
      (node (ref "R65") (pin "2") (pinfunction "2_2") (pintype "passive"))
      (node (ref "U16") (pin "5") (pinfunction "VIN-_5") (pintype "input"))
    )
    (net (code "58") (name "MOT1_PWM_A") (class "Default")
      (node (ref "RA2") (pin "C1") (pinfunction "1_C1") (pintype "passive"))
      (node (ref "U9") (pin "102") (pinfunction "IO_L32P_1_102") (pintype "bidirectional"))
    )
    (net (code "59") (name "MOT1_PWM_B") (class "Default")
      (node (ref "RA3") (pin "A1") (pinfunction "1_A1") (pintype "passive"))
      (node (ref "U9") (pin "100") (pinfunction "IO_L33P_1_100") (pintype "bidirectional"))
    )
    (net (code "60") (name "MOT1_PWM_C") (class "Default")
      (node (ref "RA3") (pin "D1") (pinfunction "1_D1") (pintype "passive"))
      (node (ref "U9") (pin "97") (pinfunction "IO_L34N_1_97") (pintype "bidirectional"))
    )
    (net (code "61") (name "MOT1_TEMP") (class "Default")
      (node (ref "U38") (pin "1") (pinfunction "OUT_1") (pintype "bidirectional"))
      (node (ref "U9") (pin "111") (pinfunction "IO_L66N_SCP0_0_111") (pintype "bidirectional"))
    )
    (net (code "62") (name "MOT2_A_5") (class "Default")
      (node (ref "CN12") (pin "3") (pinfunction "3_3") (pintype "passive"))
      (node (ref "R83") (pin "2") (pinfunction "2_2") (pintype "passive"))
      (node (ref "U27") (pin "4") (pinfunction "F_4") (pintype "bidirectional"))
    )
    (net (code "63") (name "MOT2_B_5") (class "Default")
      (node (ref "CN12") (pin "1") (pinfunction "1_1") (pintype "passive"))
      (node (ref "R84") (pin "2") (pinfunction "2_2") (pintype "passive"))
      (node (ref "U27") (pin "3") (pinfunction "E_3") (pintype "bidirectional"))
    )
    (net (code "64") (name "MOT2_CUR_U") (class "Default")
      (node (ref "U18") (pin "6") (pinfunction "OUT_6") (pintype "output"))
      (node (ref "U29") (pin "9") (pinfunction "CH2_9") (pintype "bidirectional"))
    )
    (net (code "65") (name "MOT2_CUR_V") (class "Default")
      (node (ref "U19") (pin "6") (pinfunction "OUT_6") (pintype "output"))
      (node (ref "U29") (pin "8") (pinfunction "CH3_8") (pintype "bidirectional"))
    )
    (net (code "66") (name "MOT2_GND") (class "Default")
      (node (ref "C87") (pin "2") (pinfunction "2_2") (pintype "passive"))
      (node (ref "R66") (pin "1") (pinfunction "1_1") (pintype "passive"))
      (node (ref "R67") (pin "2") (pinfunction "2_2") (pintype "passive"))
      (node (ref "U17") (pin "12") (pinfunction "M2_12") (pintype "bidirectional"))
      (node (ref "U17") (pin "9") (pinfunction "AGND_9") (pintype "bidirectional"))
    )
    (net (code "67") (name "MOT2_OUT_U") (class "Default")
      (node (ref "CN11") (pin "1.10") (pinfunction "U_1.10") (pintype "bidirectional"))
      (node (ref "CN11") (pin "1.11") (pinfunction "U_1.11") (pintype "bidirectional"))
      (node (ref "CN11") (pin "2.5") (pinfunction "U_2.5") (pintype "bidirectional"))
      (node (ref "R68") (pin "2") (pinfunction "2_2") (pintype "passive"))
      (node (ref "U18") (pin "4") (pinfunction "VIN+_4") (pintype "input"))
    )
    (net (code "68") (name "MOT2_OUT_V") (class "Default")
      (node (ref "CN11") (pin "1.8") (pinfunction "V_1.8") (pintype "bidirectional"))
      (node (ref "CN11") (pin "1.9") (pinfunction "V_1.9") (pintype "bidirectional"))
      (node (ref "CN11") (pin "2.6") (pinfunction "V_2.6") (pintype "bidirectional"))
      (node (ref "R69") (pin "2") (pinfunction "2_2") (pintype "passive"))
      (node (ref "U19") (pin "4") (pinfunction "VIN+_4") (pintype "input"))
    )
    (net (code "69") (name "MOT2_OUT_W") (class "Default")
      (node (ref "C91") (pin "2") (pinfunction "2_2") (pintype "passive"))
      (node (ref "CN11") (pin "1.6") (pinfunction "W_1.6") (pintype "bidirectional"))
      (node (ref "CN11") (pin "1.7") (pinfunction "W_1.7") (pintype "bidirectional"))
      (node (ref "CN11") (pin "2.7") (pinfunction "W_2.7") (pintype "bidirectional"))
      (node (ref "U17") (pin "22") (pinfunction "OUT_C_22") (pintype "bidirectional"))
    )
    (net (code "70") (name "MOT2_PWM_A") (class "Default")
      (node (ref "RA4") (pin "C1") (pinfunction "1_C1") (pintype "passive"))
      (node (ref "U9") (pin "81") (pinfunction "IO_L46P_1_81") (pintype "bidirectional"))
    )
    (net (code "71") (name "MOT2_PWM_B") (class "Default")
      (node (ref "RA5") (pin "A1") (pinfunction "1_A1") (pintype "passive"))
      (node (ref "U9") (pin "79") (pinfunction "IO_L47P_1_79") (pintype "bidirectional"))
    )
    (net (code "72") (name "MOT2_PWM_C") (class "Default")
      (node (ref "RA5") (pin "D1") (pinfunction "1_D1") (pintype "passive"))
      (node (ref "U9") (pin "74") (pinfunction "IO_L74N_DOUT_BUSY_1_74") (pintype "bidirectional"))
    )
    (net (code "73") (name "MOT2_TEMP") (class "Default")
      (node (ref "U39") (pin "3") (pinfunction "VOUT_3") (pintype "bidirectional"))
      (node (ref "U5") (pin "15") (pinfunction "PA30/AD6/GCLK2_15") (pintype "bidirectional"))
    )
    (net (code "74") (name "MOT3_4_5V") (class "Default")
      (node (ref "C111") (pin "1") (pinfunction "1_1") (pintype "passive"))
      (node (ref "C112") (pin "1") (pinfunction "1_1") (pintype "passive"))
      (node (ref "C126") (pin "1") (pinfunction "1_1") (pintype "passive"))
      (node (ref "C127") (pin "1") (pinfunction "1_1") (pintype "passive"))
      (node (ref "C143") (pin "1") (pinfunction "1_1") (pintype "passive"))
      (node (ref "C144") (pin "1") (pinfunction "1_1") (pintype "passive"))
      (node (ref "C146") (pin "1") (pinfunction "1_1") (pintype "passive"))
      (node (ref "R107") (pin "2") (pinfunction "2_2") (pintype "passive"))
      (node (ref "U21") (pin "3") (pinfunction "V+_3") (pintype "input"))
      (node (ref "U22") (pin "3") (pinfunction "V+_3") (pintype "input"))
      (node (ref "U24") (pin "3") (pinfunction "V+_3") (pintype "input"))
      (node (ref "U25") (pin "3") (pinfunction "V+_3") (pintype "input"))
      (node (ref "U33") (pin "1") (pinfunction "+VA_1") (pintype "bidirectional"))
      (node (ref "U33") (pin "14") (pinfunction "+VA_14") (pintype "bidirectional"))
    )
    (net (code "75") (name "MOT3_4_5_CLK") (class "Default")
      (node (ref "U30") (pin "2") (pinfunction "CK_2") (pintype "bidirectional"))
      (node (ref "U31") (pin "2") (pinfunction "CK_2") (pintype "bidirectional"))
      (node (ref "U9") (pin "22") (pinfunction "IO_L42P_GCLK25_TRDY2_3_22") (pintype "bidirectional"))
    )
    (net (code "76") (name "MOT3_4_5_EN_SENSOR") (class "Default")
      (node (ref "R112") (pin "2") (pinfunction "2_2") (pintype "passive"))
      (node (ref "U35") (pin "5") (pinfunction "EN_5") (pintype "bidirectional"))
      (node (ref "U9") (pin "12") (pinfunction "IO_L49P_3_12") (pintype "bidirectional"))
    )
    (net (code "77") (name "MOT3_4_CUR_REF") (class "Default")
      (node (ref "C142") (pin "1") (pinfunction "1_1") (pintype "passive"))
      (node (ref "C145") (pin "1") (pinfunction "1_1") (pintype "passive"))
      (node (ref "R106") (pin "1") (pinfunction "1_1") (pintype "passive"))
      (node (ref "U21") (pin "1") (pinfunction "REF_1") (pintype "input"))
      (node (ref "U22") (pin "1") (pinfunction "REF_1") (pintype "input"))
      (node (ref "U24") (pin "1") (pinfunction "REF_1") (pintype "input"))
      (node (ref "U25") (pin "1") (pinfunction "REF_1") (pintype "input"))
      (node (ref "U32") (pin "1") (pinfunction "K_1") (pintype "passive"))
      (node (ref "U33") (pin "24") (pinfunction "REFP_24") (pintype "bidirectional"))
    )
    (net (code "78") (name "MOT3_A_5") (class "Default")
      (node (ref "CN14") (pin "3") (pinfunction "3_3") (pintype "passive"))
      (node (ref "R88") (pin "2") (pinfunction "2_2") (pintype "passive"))
      (node (ref "U30") (pin "12") (pinfunction "B_12") (pintype "bidirectional"))
    )
    (net (code "79") (name "MOT3_B_5") (class "Default")
      (node (ref "CN14") (pin "1") (pinfunction "1_1") (pintype "passive"))
      (node (ref "R89") (pin "2") (pinfunction "2_2") (pintype "passive"))
      (node (ref "U30") (pin "11") (pinfunction "A_11") (pintype "bidirectional"))
    )
    (net (code "80") (name "MOT3_CUR_V") (class "Default")
      (node (ref "U21") (pin "6") (pinfunction "OUT_6") (pintype "output"))
      (node (ref "U33") (pin "10") (pinfunction "CH1_10") (pintype "bidirectional"))
    )
    (net (code "81") (name "MOT3_CUR_W") (class "Default")
      (node (ref "U22") (pin "6") (pinfunction "OUT_6") (pintype "output"))
      (node (ref "U33") (pin "11") (pinfunction "CH0_11") (pintype "bidirectional"))
    )
    (net (code "82") (name "MOT3_GND") (class "Default")
      (node (ref "C102") (pin "2") (pinfunction "2_2") (pintype "passive"))
      (node (ref "R70") (pin "1") (pinfunction "1_1") (pintype "passive"))
      (node (ref "R71") (pin "2") (pinfunction "2_2") (pintype "passive"))
      (node (ref "U20") (pin "12") (pinfunction "M2_12") (pintype "bidirectional"))
      (node (ref "U20") (pin "9") (pinfunction "AGND_9") (pintype "bidirectional"))
    )
    (net (code "83") (name "MOT3_OUT_U") (class "Default")
      (node (ref "C104") (pin "2") (pinfunction "2_2") (pintype "passive"))
      (node (ref "CN13") (pin "1.10") (pinfunction "U_1.10") (pintype "bidirectional"))
      (node (ref "CN13") (pin "1.11") (pinfunction "U_1.11") (pintype "bidirectional"))
      (node (ref "CN13") (pin "2.5") (pinfunction "U_2.5") (pintype "bidirectional"))
      (node (ref "U20") (pin "33") (pinfunction "OUT_A_33") (pintype "bidirectional"))
    )
    (net (code "84") (name "MOT3_OUT_V") (class "Default")
      (node (ref "CN13") (pin "1.8") (pinfunction "V_1.8") (pintype "bidirectional"))
      (node (ref "CN13") (pin "1.9") (pinfunction "V_1.9") (pintype "bidirectional"))
      (node (ref "CN13") (pin "2.6") (pinfunction "V_2.6") (pintype "bidirectional"))
      (node (ref "R72") (pin "2") (pinfunction "2_2") (pintype "passive"))
      (node (ref "U21") (pin "5") (pinfunction "VIN-_5") (pintype "input"))
    )
    (net (code "85") (name "MOT3_OUT_W") (class "Default")
      (node (ref "CN13") (pin "1.6") (pinfunction "W_1.6") (pintype "bidirectional"))
      (node (ref "CN13") (pin "1.7") (pinfunction "W_1.7") (pintype "bidirectional"))
      (node (ref "CN13") (pin "2.7") (pinfunction "W_2.7") (pintype "bidirectional"))
      (node (ref "R73") (pin "2") (pinfunction "2_2") (pintype "passive"))
      (node (ref "U22") (pin "5") (pinfunction "VIN-_5") (pintype "input"))
    )
    (net (code "86") (name "MOT3_PWM_A") (class "Default")
      (node (ref "RA6") (pin "C1") (pinfunction "1_C1") (pintype "passive"))
      (node (ref "U9") (pin "32") (pinfunction "IO_L2N_3_32") (pintype "bidirectional"))
    )
    (net (code "87") (name "MOT3_PWM_B") (class "Default")
      (node (ref "RA7") (pin "A1") (pinfunction "1_A1") (pintype "passive"))
      (node (ref "U9") (pin "29") (pinfunction "IO_L36N_3_29") (pintype "bidirectional"))
    )
    (net (code "88") (name "MOT3_PWM_C") (class "Default")
      (node (ref "RA7") (pin "D1") (pinfunction "1_D1") (pintype "passive"))
      (node (ref "U9") (pin "24") (pinfunction "IO_L41P_GCLK27_3_24") (pintype "bidirectional"))
    )
    (net (code "89") (name "MOT3_TEMP") (class "Default")
      (node (ref "U40") (pin "1") (pinfunction "OUT_1") (pintype "bidirectional"))
      (node (ref "U9") (pin "35") (pinfunction "IO_L1P_3_35") (pintype "bidirectional"))
    )
    (net (code "90") (name "MOT4_A_5") (class "Default")
      (node (ref "CN16") (pin "3") (pinfunction "3_3") (pintype "passive"))
      (node (ref "R93") (pin "2") (pinfunction "2_2") (pintype "passive"))
      (node (ref "U31") (pin "4") (pinfunction "F_4") (pintype "bidirectional"))
    )
    (net (code "91") (name "MOT4_B_5") (class "Default")
      (node (ref "CN16") (pin "1") (pinfunction "1_1") (pintype "passive"))
      (node (ref "R94") (pin "2") (pinfunction "2_2") (pintype "passive"))
      (node (ref "U31") (pin "3") (pinfunction "E_3") (pintype "bidirectional"))
    )
    (net (code "92") (name "MOT4_CUR_U") (class "Default")
      (node (ref "U24") (pin "6") (pinfunction "OUT_6") (pintype "output"))
      (node (ref "U33") (pin "9") (pinfunction "CH2_9") (pintype "bidirectional"))
    )
    (net (code "93") (name "MOT4_CUR_V") (class "Default")
      (node (ref "U25") (pin "6") (pinfunction "OUT_6") (pintype "output"))
      (node (ref "U33") (pin "8") (pinfunction "CH3_8") (pintype "bidirectional"))
    )
    (net (code "94") (name "MOT4_GND") (class "Default")
      (node (ref "C117") (pin "2") (pinfunction "2_2") (pintype "passive"))
      (node (ref "R74") (pin "1") (pinfunction "1_1") (pintype "passive"))
      (node (ref "R75") (pin "2") (pinfunction "2_2") (pintype "passive"))
      (node (ref "U23") (pin "12") (pinfunction "M2_12") (pintype "bidirectional"))
      (node (ref "U23") (pin "9") (pinfunction "AGND_9") (pintype "bidirectional"))
    )
    (net (code "95") (name "MOT4_OUT_U") (class "Default")
      (node (ref "CN15") (pin "1.10") (pinfunction "U_1.10") (pintype "bidirectional"))
      (node (ref "CN15") (pin "1.11") (pinfunction "U_1.11") (pintype "bidirectional"))
      (node (ref "CN15") (pin "2.5") (pinfunction "U_2.5") (pintype "bidirectional"))
      (node (ref "R76") (pin "2") (pinfunction "2_2") (pintype "passive"))
      (node (ref "U24") (pin "4") (pinfunction "VIN+_4") (pintype "input"))
    )
    (net (code "96") (name "MOT4_OUT_V") (class "Default")
      (node (ref "CN15") (pin "1.8") (pinfunction "V_1.8") (pintype "bidirectional"))
      (node (ref "CN15") (pin "1.9") (pinfunction "V_1.9") (pintype "bidirectional"))
      (node (ref "CN15") (pin "2.6") (pinfunction "V_2.6") (pintype "bidirectional"))
      (node (ref "R77") (pin "2") (pinfunction "2_2") (pintype "passive"))
      (node (ref "U25") (pin "4") (pinfunction "VIN+_4") (pintype "input"))
    )
    (net (code "97") (name "MOT4_OUT_W") (class "Default")
      (node (ref "C121") (pin "2") (pinfunction "2_2") (pintype "passive"))
      (node (ref "CN15") (pin "1.6") (pinfunction "W_1.6") (pintype "bidirectional"))
      (node (ref "CN15") (pin "1.7") (pinfunction "W_1.7") (pintype "bidirectional"))
      (node (ref "CN15") (pin "2.7") (pinfunction "W_2.7") (pintype "bidirectional"))
      (node (ref "U23") (pin "22") (pinfunction "OUT_C_22") (pintype "bidirectional"))
    )
    (net (code "98") (name "MOT4_PWM_A") (class "Default")
      (node (ref "RA8") (pin "C1") (pinfunction "1_C1") (pintype "passive"))
      (node (ref "U9") (pin "9") (pinfunction "IO_L50N_3_9") (pintype "bidirectional"))
    )
    (net (code "99") (name "MOT4_PWM_B") (class "Default")
      (node (ref "RA9") (pin "A1") (pinfunction "1_A1") (pintype "passive"))
      (node (ref "U9") (pin "7") (pinfunction "IO_L51N_3_7") (pintype "bidirectional"))
    )
    (net (code "100") (name "MOT4_PWM_C") (class "Default")
      (node (ref "RA9") (pin "D1") (pinfunction "1_D1") (pintype "passive"))
      (node (ref "U9") (pin "2") (pinfunction "IO_L83P_3_2") (pintype "bidirectional"))
    )
    (net (code "101") (name "MOT4_TEMP") (class "Default")
      (node (ref "U41") (pin "1") (pinfunction "OUT_1") (pintype "bidirectional"))
      (node (ref "U9") (pin "1") (pinfunction "IO_L83N_VREF_3_1") (pintype "bidirectional"))
    )
    (net (code "102") (name "MOT5_CUR_SCL") (class "Default")
      (node (ref "R115") (pin "1") (pinfunction "1_1") (pintype "passive"))
      (node (ref "U36") (pin "5") (pinfunction "SCL_5") (pintype "bidirectional"))
      (node (ref "U9") (pin "144") (pinfunction "IO_L1P_HSWAPEN_0_144") (pintype "bidirectional"))
    )
    (net (code "103") (name "MOT5_CUR_SDA") (class "Default")
      (node (ref "R116") (pin "1") (pinfunction "1_1") (pintype "passive"))
      (node (ref "U36") (pin "6") (pinfunction "SDA_6") (pintype "bidirectional"))
      (node (ref "U9") (pin "143") (pinfunction "IO_L1N_VREF_0_143") (pintype "bidirectional"))
    )
    (net (code "104") (name "MOT5_GND") (class "Default")
      (node (ref "C153") (pin "2") (pinfunction "2_2") (pintype "passive"))
      (node (ref "R117") (pin "1") (pinfunction "1_1") (pintype "passive"))
      (node (ref "R118") (pin "2") (pinfunction "2_2") (pintype "passive"))
      (node (ref "U37") (pin "12") (pinfunction "M2_12") (pintype "bidirectional"))
      (node (ref "U37") (pin "9") (pinfunction "AGND_9") (pintype "bidirectional"))
    )
    (net (code "105") (name "MOT5_OUT_U") (class "Default")
      (node (ref "C155") (pin "2") (pinfunction "2_2") (pintype "passive"))
      (node (ref "CN17") (pin "1") (pinfunction "1_1") (pintype "passive"))
      (node (ref "U37") (pin "33") (pinfunction "OUT_A_33") (pintype "bidirectional"))
    )
    (net (code "106") (name "MOT5_OUT_V") (class "Default")
      (node (ref "C156") (pin "2") (pinfunction "2_2") (pintype "passive"))
      (node (ref "CN17") (pin "2") (pinfunction "2_2") (pintype "passive"))
      (node (ref "U37") (pin "30") (pinfunction "OUT_B_30") (pintype "bidirectional"))
    )
    (net (code "107") (name "MOT5_OUT_W") (class "Default")
      (node (ref "C157") (pin "2") (pinfunction "2_2") (pintype "passive"))
      (node (ref "CN17") (pin "3") (pinfunction "3_3") (pintype "passive"))
      (node (ref "U37") (pin "22") (pinfunction "OUT_C_22") (pintype "bidirectional"))
    )
    (net (code "108") (name "MOT5_PWM_A") (class "Default")
      (node (ref "RA10") (pin "C1") (pinfunction "1_C1") (pintype "passive"))
      (node (ref "U9") (pin "140") (pinfunction "IO_L3P_0_140") (pintype "bidirectional"))
    )
    (net (code "109") (name "MOT5_PWM_B") (class "Default")
      (node (ref "RA11") (pin "A1") (pinfunction "1_A1") (pintype "passive"))
      (node (ref "U9") (pin "138") (pinfunction "IO_L4P_0_138") (pintype "bidirectional"))
    )
    (net (code "110") (name "MOT5_PWM_C") (class "Default")
      (node (ref "RA11") (pin "D1") (pinfunction "1_D1") (pintype "passive"))
      (node (ref "U9") (pin "133") (pinfunction "IO_L34N_GCLK18_0_133") (pintype "bidirectional"))
    )
    (net (code "111") (name "Net-(C10-Pad2)") (class "Default")
      (node (ref "C10") (pin "2") (pinfunction "2_2") (pintype "passive"))
      (node (ref "C11") (pin "1") (pinfunction "1_1") (pintype "passive"))
      (node (ref "C13") (pin "1") (pinfunction "1_1") (pintype "passive"))
      (node (ref "C7") (pin "P") (pinfunction "P_P") (pintype "passive"))
      (node (ref "C9") (pin "1") (pinfunction "1_1") (pintype "passive"))
      (node (ref "D3") (pin "K") (pinfunction "K_K") (pintype "passive"))
      (node (ref "D4") (pin "K") (pinfunction "K_K") (pintype "passive"))
      (node (ref "L1") (pin "1") (pinfunction "1_1") (pintype "passive"))
      (node (ref "R9") (pin "2") (pinfunction "2_2") (pintype "passive"))
      (node (ref "U2") (pin "11") (pinfunction "VIN_11") (pintype "bidirectional"))
      (node (ref "U2") (pin "26") (pinfunction "VIN_26") (pintype "bidirectional"))
      (node (ref "U2") (pin "28") (pinfunction "VIN_28") (pintype "bidirectional"))
      (node (ref "U2") (pin "9") (pinfunction "VIN_9") (pintype "bidirectional"))
    )
    (net (code "112") (name "Net-(C14-Pad1)") (class "Default")
      (node (ref "C14") (pin "1") (pinfunction "1_1") (pintype "passive"))
      (node (ref "R13") (pin "1") (pinfunction "1_1") (pintype "passive"))
    )
    (net (code "113") (name "Net-(C55-Pad1)") (class "Default")
      (node (ref "C55") (pin "1") (pinfunction "1_1") (pintype "passive"))
      (node (ref "U9") (pin "128") (pinfunction "VCCINT_128") (pintype "bidirectional"))
    )
    (net (code "114") (name "Net-(C56-Pad1)") (class "Default")
      (node (ref "C56") (pin "1") (pinfunction "1_1") (pintype "passive"))
      (node (ref "U9") (pin "89") (pinfunction "VCCINT_89") (pintype "bidirectional"))
    )
    (net (code "115") (name "Net-(C58-Pad1)") (class "Default")
      (node (ref "C58") (pin "1") (pinfunction "1_1") (pintype "passive"))
      (node (ref "U9") (pin "52") (pinfunction "VCCINT_52") (pintype "bidirectional"))
    )
    (net (code "116") (name "Net-(C60-Pad1)") (class "Default")
      (node (ref "C60") (pin "1") (pinfunction "1_1") (pintype "passive"))
      (node (ref "U9") (pin "28") (pinfunction "VCCINT_28") (pintype "bidirectional"))
    )
    (net (code "117") (name "Net-(C62-Pad1)") (class "Default")
      (node (ref "C62") (pin "1") (pinfunction "1_1") (pintype "passive"))
      (node (ref "U9") (pin "19") (pinfunction "VCCINT_19") (pintype "bidirectional"))
    )
    (net (code "118") (name "Net-(C166-Pad1)") (class "Default")
      (node (ref "C166") (pin "1") (pinfunction "1_1") (pintype "passive"))
      (node (ref "F2") (pin "1") (pinfunction "1_1") (pintype "passive"))
      (node (ref "Q3") (pin "5") (pinfunction "D_5") (pintype "passive"))
      (node (ref "Q3") (pin "6") (pinfunction "D_6") (pintype "passive"))
      (node (ref "Q3") (pin "7") (pinfunction "D_7") (pintype "passive"))
      (node (ref "Q3") (pin "8") (pinfunction "D_8") (pintype "passive"))
    )
    (net (code "119") (name "Net-(C167-Pad1)") (class "Default")
      (node (ref "C167") (pin "1") (pinfunction "1_1") (pintype "passive"))
      (node (ref "F3") (pin "1") (pinfunction "1_1") (pintype "passive"))
      (node (ref "Q4") (pin "5") (pinfunction "D_5") (pintype "passive"))
      (node (ref "Q4") (pin "6") (pinfunction "D_6") (pintype "passive"))
      (node (ref "Q4") (pin "7") (pinfunction "D_7") (pintype "passive"))
      (node (ref "Q4") (pin "8") (pinfunction "D_8") (pintype "passive"))
    )
    (net (code "120") (name "Net-(CN1-PadP)") (class "Default")
      (node (ref "CN1") (pin "P") (pinfunction "P_P") (pintype "passive"))
      (node (ref "F1") (pin "1") (pinfunction "1_1") (pintype "passive"))
    )
    (net (code "121") (name "Net-(CN3-D+)") (class "Default")
      (node (ref "CN3") (pin "3") (pinfunction "D+_3") (pintype "passive"))
      (node (ref "U4") (pin "1") (pinfunction "O1_1") (pintype "bidirectional"))
    )
    (net (code "122") (name "Net-(CN3-D-)") (class "Default")
      (node (ref "CN3") (pin "2") (pinfunction "D-_2") (pintype "passive"))
      (node (ref "U4") (pin "6") (pinfunction "O2_6") (pintype "bidirectional"))
    )
    (net (code "123") (name "Net-(CN3-VBUS)") (class "Default")
      (node (ref "C22") (pin "1") (pinfunction "1_1") (pintype "passive"))
      (node (ref "CN3") (pin "1") (pinfunction "VBUS_1") (pintype "passive"))
      (node (ref "R33") (pin "2") (pinfunction "2_2") (pintype "passive"))
      (node (ref "U4") (pin "5") (pinfunction "V+_5") (pintype "bidirectional"))
    )
    (net (code "124") (name "Net-(CN4-TCK)") (class "Default")
      (node (ref "CN4") (pin "1") (pinfunction "TCK_1") (pintype "passive"))
      (node (ref "R37") (pin "1") (pinfunction "1_1") (pintype "passive"))
      (node (ref "U5") (pin "2") (pinfunction "TCK_2") (pintype "bidirectional"))
    )
    (net (code "125") (name "Net-(CN4-TDI)") (class "Default")
      (node (ref "CN4") (pin "9") (pinfunction "TDI_9") (pintype "passive"))
      (node (ref "U5") (pin "3") (pinfunction "PA00/TDI_3") (pintype "bidirectional"))
    )
    (net (code "126") (name "Net-(CN4-TDO)") (class "Default")
      (node (ref "CN4") (pin "3") (pinfunction "TDO_3") (pintype "passive"))
      (node (ref "U5") (pin "4") (pinfunction "PA01/TDO_4") (pintype "bidirectional"))
    )
    (net (code "127") (name "Net-(CN4-TMS)") (class "Default")
      (node (ref "CN4") (pin "5") (pinfunction "TMS_5") (pintype "passive"))
      (node (ref "U5") (pin "5") (pinfunction "PA02/TMS_5") (pintype "bidirectional"))
    )
    (net (code "128") (name "Net-(CN7-VCC)") (class "Default")
      (node (ref "C66") (pin "1") (pinfunction "1_1") (pintype "passive"))
      (node (ref "CN7") (pin "1") (pinfunction "VCC_1") (pintype "bidirectional"))
      (node (ref "FB1") (pin "2") (pinfunction "2_2") (pintype "passive"))
    )
    (net (code "129") (name "Net-(CN8-Pad1)") (class "Default")
      (node (ref "CN8") (pin "1") (pinfunction "1_1") (pintype "passive"))
      (node (ref "R54") (pin "1") (pinfunction "1_1") (pintype "passive"))
      (node (ref "R56") (pin "1") (pinfunction "1_1") (pintype "passive"))
    )
    (net (code "130") (name "Net-(CN8-Pad3)") (class "Default")
      (node (ref "CN8") (pin "3") (pinfunction "3_3") (pintype "passive"))
      (node (ref "R55") (pin "1") (pinfunction "1_1") (pintype "passive"))
      (node (ref "R57") (pin "1") (pinfunction "1_1") (pintype "passive"))
      (node (ref "VR1") (pin "A") (pinfunction "A_A") (pintype "passive"))
    )
    (net (code "131") (name "Net-(CN8-Pad4)") (class "Default")
      (node (ref "CN8") (pin "4") (pinfunction "4_4") (pintype "passive"))
      (node (ref "U12") (pin "2") (pinfunction "OUT_2") (pintype "bidirectional"))
      (node (ref "U12") (pin "3") (pinfunction "OUT_3") (pintype "bidirectional"))
    )
    (net (code "132") (name "Net-(D1-PadK)") (class "Default")
      (node (ref "D1") (pin "K") (pinfunction "K_K") (pintype "passive"))
      (node (ref "F1") (pin "2") (pinfunction "2_2") (pintype "passive"))
      (node (ref "R1") (pin "V1") (pinfunction "V1_V1") (pintype "passive"))
    )
    (net (code "133") (name "Net-(LED1-PadA)") (class "Default")
      (node (ref "LED1") (pin "A") (pinfunction "A_A") (pintype "passive"))
      (node (ref "R40") (pin "1") (pinfunction "1_1") (pintype "passive"))
    )
    (net (code "134") (name "Net-(LED2-PadA)") (class "Default")
      (node (ref "LED2") (pin "A") (pinfunction "A_A") (pintype "passive"))
      (node (ref "R41") (pin "1") (pinfunction "1_1") (pintype "passive"))
    )
    (net (code "135") (name "Net-(LED3-PadA)") (class "Default")
      (node (ref "LED3") (pin "A") (pinfunction "A_A") (pintype "passive"))
      (node (ref "R42") (pin "1") (pinfunction "1_1") (pintype "passive"))
    )
    (net (code "136") (name "Net-(LED4-PadA)") (class "Default")
      (node (ref "LED4") (pin "A") (pinfunction "A_A") (pintype "passive"))
      (node (ref "R46") (pin "1") (pinfunction "1_1") (pintype "passive"))
    )
    (net (code "137") (name "Net-(LED5-PadA)") (class "Default")
      (node (ref "LED5") (pin "A") (pinfunction "A_A") (pintype "passive"))
      (node (ref "R47") (pin "1") (pinfunction "1_1") (pintype "passive"))
    )
    (net (code "138") (name "Net-(LED6-PadA)") (class "Default")
      (node (ref "LED6") (pin "A") (pinfunction "A_A") (pintype "passive"))
      (node (ref "R48") (pin "1") (pinfunction "1_1") (pintype "passive"))
    )
    (net (code "139") (name "Net-(LED7-PadA)") (class "Default")
      (node (ref "LED7") (pin "A") (pinfunction "A_A") (pintype "passive"))
      (node (ref "R49") (pin "1") (pinfunction "1_1") (pintype "passive"))
    )
    (net (code "140") (name "Net-(LED8-PadA)") (class "Default")
      (node (ref "LED8") (pin "A") (pinfunction "A_A") (pintype "passive"))
      (node (ref "R50") (pin "1") (pinfunction "1_1") (pintype "passive"))
    )
    (net (code "141") (name "Net-(LED9-PadA)") (class "Default")
      (node (ref "LED9") (pin "A") (pinfunction "A_A") (pintype "passive"))
      (node (ref "R51") (pin "1") (pinfunction "1_1") (pintype "passive"))
    )
    (net (code "142") (name "Net-(LED10-PadA)") (class "Default")
      (node (ref "LED10") (pin "A") (pinfunction "A_A") (pintype "passive"))
      (node (ref "R52") (pin "1") (pinfunction "1_1") (pintype "passive"))
    )
    (net (code "143") (name "Net-(Q1-D)") (class "Default")
      (node (ref "C166") (pin "2") (pinfunction "2_2") (pintype "passive"))
      (node (ref "Q1") (pin "3") (pinfunction "D_3") (pintype "passive"))
      (node (ref "Q3") (pin "4") (pinfunction "G_4") (pintype "passive"))
      (node (ref "R23") (pin "1") (pinfunction "1_1") (pintype "passive"))
    )
    (net (code "144") (name "Net-(Q1-G)") (class "Default")
      (node (ref "Q1") (pin "1") (pinfunction "G_1") (pintype "passive"))
      (node (ref "R29") (pin "1") (pinfunction "1_1") (pintype "passive"))
    )
    (net (code "145") (name "Net-(Q1-S)") (class "Default")
      (node (ref "Q1") (pin "2") (pinfunction "S_2") (pintype "passive"))
      (node (ref "R25") (pin "2") (pinfunction "2_2") (pintype "passive"))
    )
    (net (code "146") (name "Net-(Q2-D)") (class "Default")
      (node (ref "C167") (pin "2") (pinfunction "2_2") (pintype "passive"))
      (node (ref "Q2") (pin "3") (pinfunction "D_3") (pintype "passive"))
      (node (ref "Q4") (pin "4") (pinfunction "G_4") (pintype "passive"))
      (node (ref "R24") (pin "1") (pinfunction "1_1") (pintype "passive"))
    )
    (net (code "147") (name "Net-(Q2-G)") (class "Default")
      (node (ref "Q2") (pin "1") (pinfunction "G_1") (pintype "passive"))
      (node (ref "R30") (pin "1") (pinfunction "1_1") (pintype "passive"))
    )
    (net (code "148") (name "Net-(Q2-S)") (class "Default")
      (node (ref "Q2") (pin "2") (pinfunction "S_2") (pintype "passive"))
      (node (ref "R26") (pin "2") (pinfunction "2_2") (pintype "passive"))
    )
    (net (code "149") (name "Net-(R58-Pad1)") (class "Default")
      (node (ref "R58") (pin "1") (pinfunction "1_1") (pintype "passive"))
      (node (ref "R59") (pin "1") (pinfunction "1_1") (pintype "passive"))
      (node (ref "VR1") (pin "B") (pinfunction "B_B") (pintype "passive"))
      (node (ref "VR1") (pin "W") (pinfunction "W_W") (pintype "passive"))
    )
    (net (code "150") (name "Net-(R122-Pad1)") (class "Default")
      (node (ref "R122") (pin "1") (pinfunction "1_1") (pintype "passive"))
      (node (ref "R4") (pin "1") (pinfunction "1_1") (pintype "passive"))
      (node (ref "R5") (pin "2") (pinfunction "2_2") (pintype "passive"))
    )
    (net (code "151") (name "Net-(R123-Pad1)") (class "Default")
      (node (ref "R123") (pin "1") (pinfunction "1_1") (pintype "passive"))
      (node (ref "R6") (pin "1") (pinfunction "1_1") (pintype "passive"))
      (node (ref "R7") (pin "2") (pinfunction "2_2") (pintype "passive"))
    )
    (net (code "152") (name "Net-(RA1A-1)") (class "Default")
      (node (ref "RA1") (pin "A1") (pinfunction "1_A1") (pintype "passive"))
      (node (ref "U5") (pin "58") (pinfunction "PB11/SSC-TXFRM/TC-B2/USART0-TXD_58") (pintype "bidirectional"))
    )
    (net (code "153") (name "Net-(RA1B-2)") (class "Default")
      (node (ref "C36") (pin "1") (pinfunction "1_1") (pintype "passive"))
      (node (ref "RA1") (pin "B2") (pinfunction "2_B2") (pintype "passive"))
      (node (ref "U6") (pin "6") (pinfunction "VCC_6") (pintype "bidirectional"))
    )
    (net (code "154") (name "Net-(RA1C-1)") (class "Default")
      (node (ref "RA1") (pin "C1") (pinfunction "1_C1") (pintype "passive"))
      (node (ref "U5") (pin "57") (pinfunction "PB10/SSC-TXDAT/TC-A2/USART0-RXD_57") (pintype "bidirectional"))
    )
    (net (code "155") (name "Net-(RA1D-2)") (class "Default")
      (node (ref "RA1") (pin "D2") (pinfunction "2_D2") (pintype "passive"))
      (node (ref "U6") (pin "1") (pinfunction "IREDA_1") (pintype "bidirectional"))
    )
    (net (code "156") (name "Net-(RA2A-2)") (class "Default")
      (node (ref "RA2") (pin "A2") (pinfunction "2_A2") (pintype "passive"))
      (node (ref "U14") (pin "2") (pinfunction "~{OTW}_2") (pintype "bidirectional"))
    )
    (net (code "157") (name "Net-(RA2B-2)") (class "Default")
      (node (ref "RA2") (pin "B2") (pinfunction "2_B2") (pintype "passive"))
      (node (ref "U14") (pin "3") (pinfunction "~{FAULT}_3") (pintype "bidirectional"))
    )
    (net (code "158") (name "Net-(RA2C-2)") (class "Default")
      (node (ref "RA2") (pin "C2") (pinfunction "2_C2") (pintype "passive"))
      (node (ref "U14") (pin "4") (pinfunction "PWM_A_4") (pintype "bidirectional"))
    )
    (net (code "159") (name "Net-(RA2D-2)") (class "Default")
      (node (ref "RA2") (pin "D2") (pinfunction "2_D2") (pintype "passive"))
      (node (ref "U14") (pin "5") (pinfunction "~{RESET_A}_5") (pintype "bidirectional"))
    )
    (net (code "160") (name "Net-(RA3A-2)") (class "Default")
      (node (ref "RA3") (pin "A2") (pinfunction "2_A2") (pintype "passive"))
      (node (ref "U14") (pin "6") (pinfunction "PWM_B_6") (pintype "bidirectional"))
    )
    (net (code "161") (name "Net-(RA3B-2)") (class "Default")
      (node (ref "RA3") (pin "B2") (pinfunction "2_B2") (pintype "passive"))
      (node (ref "U14") (pin "14") (pinfunction "~{RESET_B}_14") (pintype "bidirectional"))
    )
    (net (code "162") (name "Net-(RA3C-2)") (class "Default")
      (node (ref "RA3") (pin "C2") (pinfunction "2_C2") (pintype "passive"))
      (node (ref "U14") (pin "15") (pinfunction "~{RESET_C}_15") (pintype "bidirectional"))
    )
    (net (code "163") (name "Net-(RA3D-2)") (class "Default")
      (node (ref "RA3") (pin "D2") (pinfunction "2_D2") (pintype "passive"))
      (node (ref "U14") (pin "16") (pinfunction "PWM_C_16") (pintype "bidirectional"))
    )
    (net (code "164") (name "Net-(RA4A-2)") (class "Default")
      (node (ref "RA4") (pin "A2") (pinfunction "2_A2") (pintype "passive"))
      (node (ref "U17") (pin "2") (pinfunction "~{OTW}_2") (pintype "bidirectional"))
    )
    (net (code "165") (name "Net-(RA4B-2)") (class "Default")
      (node (ref "RA4") (pin "B2") (pinfunction "2_B2") (pintype "passive"))
      (node (ref "U17") (pin "3") (pinfunction "~{FAULT}_3") (pintype "bidirectional"))
    )
    (net (code "166") (name "Net-(RA4C-2)") (class "Default")
      (node (ref "RA4") (pin "C2") (pinfunction "2_C2") (pintype "passive"))
      (node (ref "U17") (pin "4") (pinfunction "PWM_A_4") (pintype "bidirectional"))
    )
    (net (code "167") (name "Net-(RA4D-2)") (class "Default")
      (node (ref "RA4") (pin "D2") (pinfunction "2_D2") (pintype "passive"))
      (node (ref "U17") (pin "5") (pinfunction "~{RESET_A}_5") (pintype "bidirectional"))
    )
    (net (code "168") (name "Net-(RA5A-2)") (class "Default")
      (node (ref "RA5") (pin "A2") (pinfunction "2_A2") (pintype "passive"))
      (node (ref "U17") (pin "6") (pinfunction "PWM_B_6") (pintype "bidirectional"))
    )
    (net (code "169") (name "Net-(RA5B-2)") (class "Default")
      (node (ref "RA5") (pin "B2") (pinfunction "2_B2") (pintype "passive"))
      (node (ref "U17") (pin "14") (pinfunction "~{RESET_B}_14") (pintype "bidirectional"))
    )
    (net (code "170") (name "Net-(RA5C-2)") (class "Default")
      (node (ref "RA5") (pin "C2") (pinfunction "2_C2") (pintype "passive"))
      (node (ref "U17") (pin "15") (pinfunction "~{RESET_C}_15") (pintype "bidirectional"))
    )
    (net (code "171") (name "Net-(RA5D-2)") (class "Default")
      (node (ref "RA5") (pin "D2") (pinfunction "2_D2") (pintype "passive"))
      (node (ref "U17") (pin "16") (pinfunction "PWM_C_16") (pintype "bidirectional"))
    )
    (net (code "172") (name "Net-(RA6A-2)") (class "Default")
      (node (ref "RA6") (pin "A2") (pinfunction "2_A2") (pintype "passive"))
      (node (ref "U20") (pin "2") (pinfunction "~{OTW}_2") (pintype "bidirectional"))
    )
    (net (code "173") (name "Net-(RA6B-2)") (class "Default")
      (node (ref "RA6") (pin "B2") (pinfunction "2_B2") (pintype "passive"))
      (node (ref "U20") (pin "3") (pinfunction "~{FAULT}_3") (pintype "bidirectional"))
    )
    (net (code "174") (name "Net-(RA6C-2)") (class "Default")
      (node (ref "RA6") (pin "C2") (pinfunction "2_C2") (pintype "passive"))
      (node (ref "U20") (pin "4") (pinfunction "PWM_A_4") (pintype "bidirectional"))
    )
    (net (code "175") (name "Net-(RA6D-2)") (class "Default")
      (node (ref "RA6") (pin "D2") (pinfunction "2_D2") (pintype "passive"))
      (node (ref "U20") (pin "5") (pinfunction "~{RESET_A}_5") (pintype "bidirectional"))
    )
    (net (code "176") (name "Net-(RA7A-2)") (class "Default")
      (node (ref "RA7") (pin "A2") (pinfunction "2_A2") (pintype "passive"))
      (node (ref "U20") (pin "6") (pinfunction "PWM_B_6") (pintype "bidirectional"))
    )
    (net (code "177") (name "Net-(RA7B-2)") (class "Default")
      (node (ref "RA7") (pin "B2") (pinfunction "2_B2") (pintype "passive"))
      (node (ref "U20") (pin "14") (pinfunction "~{RESET_B}_14") (pintype "bidirectional"))
    )
    (net (code "178") (name "Net-(RA7C-2)") (class "Default")
      (node (ref "RA7") (pin "C2") (pinfunction "2_C2") (pintype "passive"))
      (node (ref "U20") (pin "15") (pinfunction "~{RESET_C}_15") (pintype "bidirectional"))
    )
    (net (code "179") (name "Net-(RA7D-2)") (class "Default")
      (node (ref "RA7") (pin "D2") (pinfunction "2_D2") (pintype "passive"))
      (node (ref "U20") (pin "16") (pinfunction "PWM_C_16") (pintype "bidirectional"))
    )
    (net (code "180") (name "Net-(RA8A-2)") (class "Default")
      (node (ref "RA8") (pin "A2") (pinfunction "2_A2") (pintype "passive"))
      (node (ref "U23") (pin "2") (pinfunction "~{OTW}_2") (pintype "bidirectional"))
    )
    (net (code "181") (name "Net-(RA8B-2)") (class "Default")
      (node (ref "RA8") (pin "B2") (pinfunction "2_B2") (pintype "passive"))
      (node (ref "U23") (pin "3") (pinfunction "~{FAULT}_3") (pintype "bidirectional"))
    )
    (net (code "182") (name "Net-(RA8C-2)") (class "Default")
      (node (ref "RA8") (pin "C2") (pinfunction "2_C2") (pintype "passive"))
      (node (ref "U23") (pin "4") (pinfunction "PWM_A_4") (pintype "bidirectional"))
    )
    (net (code "183") (name "Net-(RA8D-2)") (class "Default")
      (node (ref "RA8") (pin "D2") (pinfunction "2_D2") (pintype "passive"))
      (node (ref "U23") (pin "5") (pinfunction "~{RESET_A}_5") (pintype "bidirectional"))
    )
    (net (code "184") (name "Net-(RA9A-2)") (class "Default")
      (node (ref "RA9") (pin "A2") (pinfunction "2_A2") (pintype "passive"))
      (node (ref "U23") (pin "6") (pinfunction "PWM_B_6") (pintype "bidirectional"))
    )
    (net (code "185") (name "Net-(RA9B-2)") (class "Default")
      (node (ref "RA9") (pin "B2") (pinfunction "2_B2") (pintype "passive"))
      (node (ref "U23") (pin "14") (pinfunction "~{RESET_B}_14") (pintype "bidirectional"))
    )
    (net (code "186") (name "Net-(RA9C-2)") (class "Default")
      (node (ref "RA9") (pin "C2") (pinfunction "2_C2") (pintype "passive"))
      (node (ref "U23") (pin "15") (pinfunction "~{RESET_C}_15") (pintype "bidirectional"))
    )
    (net (code "187") (name "Net-(RA9D-2)") (class "Default")
      (node (ref "RA9") (pin "D2") (pinfunction "2_D2") (pintype "passive"))
      (node (ref "U23") (pin "16") (pinfunction "PWM_C_16") (pintype "bidirectional"))
    )
    (net (code "188") (name "Net-(RA10A-2)") (class "Default")
      (node (ref "RA10") (pin "A2") (pinfunction "2_A2") (pintype "passive"))
      (node (ref "U37") (pin "2") (pinfunction "~{OTW}_2") (pintype "bidirectional"))
    )
    (net (code "189") (name "Net-(RA10B-2)") (class "Default")
      (node (ref "RA10") (pin "B2") (pinfunction "2_B2") (pintype "passive"))
      (node (ref "U37") (pin "3") (pinfunction "~{FAULT}_3") (pintype "bidirectional"))
    )
    (net (code "190") (name "Net-(RA10C-2)") (class "Default")
      (node (ref "RA10") (pin "C2") (pinfunction "2_C2") (pintype "passive"))
      (node (ref "U37") (pin "4") (pinfunction "PWM_A_4") (pintype "bidirectional"))
    )
    (net (code "191") (name "Net-(RA10D-2)") (class "Default")
      (node (ref "RA10") (pin "D2") (pinfunction "2_D2") (pintype "passive"))
      (node (ref "U37") (pin "5") (pinfunction "~{RESET_A}_5") (pintype "bidirectional"))
    )
    (net (code "192") (name "Net-(RA11A-2)") (class "Default")
      (node (ref "RA11") (pin "A2") (pinfunction "2_A2") (pintype "passive"))
      (node (ref "U37") (pin "6") (pinfunction "PWM_B_6") (pintype "bidirectional"))
    )
    (net (code "193") (name "Net-(RA11B-2)") (class "Default")
      (node (ref "RA11") (pin "B2") (pinfunction "2_B2") (pintype "passive"))
      (node (ref "U37") (pin "14") (pinfunction "~{RESET_B}_14") (pintype "bidirectional"))
    )
    (net (code "194") (name "Net-(RA11C-2)") (class "Default")
      (node (ref "RA11") (pin "C2") (pinfunction "2_C2") (pintype "passive"))
      (node (ref "U37") (pin "15") (pinfunction "~{RESET_C}_15") (pintype "bidirectional"))
    )
    (net (code "195") (name "Net-(RA11D-2)") (class "Default")
      (node (ref "RA11") (pin "D2") (pinfunction "2_D2") (pintype "passive"))
      (node (ref "U37") (pin "16") (pinfunction "PWM_C_16") (pintype "bidirectional"))
    )
    (net (code "196") (name "Net-(RF3-Pad2)") (class "Default")
      (node (ref "RF3") (pin "2") (pinfunction "2_2") (pintype "passive"))
      (node (ref "U34") (pin "2") (pinfunction "OUT_2") (pintype "bidirectional"))
      (node (ref "U34") (pin "3") (pinfunction "OUT_3") (pintype "bidirectional"))
    )
    (net (code "197") (name "Net-(RF4-Pad2)") (class "Default")
      (node (ref "RF4") (pin "2") (pinfunction "2_2") (pintype "passive"))
      (node (ref "U35") (pin "2") (pinfunction "OUT_2") (pintype "bidirectional"))
      (node (ref "U35") (pin "3") (pinfunction "OUT_3") (pintype "bidirectional"))
    )
    (net (code "198") (name "Net-(SW1-A)") (class "Default")
      (node (ref "R1") (pin "V2") (pinfunction "V2_V2") (pintype "passive"))
      (node (ref "SW1") (pin "P") (pinfunction "A_P") (pintype "passive"))
    )
    (net (code "199") (name "Net-(U1-VIN+)") (class "Default")
      (node (ref "R1") (pin "I1") (pinfunction "I1_I1") (pintype "passive"))
      (node (ref "U1") (pin "1") (pinfunction "VIN+_1") (pintype "input"))
    )
    (net (code "200") (name "Net-(U1-VIN-)") (class "Default")
      (node (ref "R1") (pin "I2") (pinfunction "I2_I2") (pintype "passive"))
      (node (ref "U1") (pin "2") (pinfunction "VIN-_2") (pintype "input"))
    )
    (net (code "201") (name "Net-(U2-DA1)") (class "Default")
      (node (ref "D5") (pin "A") (pinfunction "A_A") (pintype "passive"))
      (node (ref "U2") (pin "6") (pinfunction "DA1_6") (pintype "bidirectional"))
    )
    (net (code "202") (name "Net-(U2-DA2)") (class "Default")
      (node (ref "D6") (pin "A") (pinfunction "A_A") (pintype "passive"))
      (node (ref "U2") (pin "1") (pinfunction "DA2_1") (pintype "bidirectional"))
    )
    (net (code "203") (name "Net-(U2-DA3)") (class "Default")
      (node (ref "D7") (pin "A") (pinfunction "A_A") (pintype "passive"))
      (node (ref "U2") (pin "3") (pinfunction "DA3_3") (pintype "bidirectional"))
    )
    (net (code "204") (name "Net-(U2-DA4)") (class "Default")
      (node (ref "D8") (pin "A") (pinfunction "A_A") (pintype "passive"))
      (node (ref "U2") (pin "8") (pinfunction "DA4_8") (pintype "bidirectional"))
    )
    (net (code "205") (name "Net-(U2-EN{slash}UVLO)") (class "Default")
      (node (ref "R10") (pin "2") (pinfunction "2_2") (pintype "passive"))
      (node (ref "R9") (pin "1") (pinfunction "1_1") (pintype "passive"))
      (node (ref "U2") (pin "16") (pinfunction "EN/UVLO_16") (pintype "bidirectional"))
    )
    (net (code "206") (name "Net-(U2-FB1)") (class "Default")
      (node (ref "R14") (pin "1") (pinfunction "1_1") (pintype "passive"))
      (node (ref "R15") (pin "2") (pinfunction "2_2") (pintype "passive"))
      (node (ref "U2") (pin "20") (pinfunction "FB1_20") (pintype "bidirectional"))
    )
    (net (code "207") (name "Net-(U2-FB2)") (class "Default")
      (node (ref "R16") (pin "1") (pinfunction "1_1") (pintype "passive"))
      (node (ref "R17") (pin "2") (pinfunction "2_2") (pintype "passive"))
      (node (ref "U2") (pin "22") (pinfunction "FB2_22") (pintype "bidirectional"))
    )
    (net (code "208") (name "Net-(U2-FB3)") (class "Default")
      (node (ref "R18") (pin "1") (pinfunction "1_1") (pintype "passive"))
      (node (ref "R19") (pin "2") (pinfunction "2_2") (pintype "passive"))
      (node (ref "U2") (pin "21") (pinfunction "FB3_21") (pintype "bidirectional"))
    )
    (net (code "209") (name "Net-(U2-FB4)") (class "Default")
      (node (ref "R20") (pin "1") (pinfunction "1_1") (pintype "passive"))
      (node (ref "R21") (pin "2") (pinfunction "2_2") (pintype "passive"))
      (node (ref "U2") (pin "19") (pinfunction "FB4_19") (pintype "bidirectional"))
    )
    (net (code "210") (name "Net-(U2-RT{slash}SYNC)") (class "Default")
      (node (ref "R12") (pin "2") (pinfunction "2_2") (pintype "passive"))
      (node (ref "U2") (pin "17") (pinfunction "RT/SYNC_17") (pintype "bidirectional"))
    )
    (net (code "211") (name "Net-(U2-RUN{slash}SS1)") (class "Default")
      (node (ref "C12") (pin "1") (pinfunction "1_1") (pintype "passive"))
      (node (ref "U2") (pin "12") (pinfunction "RUN/SS4_12") (pintype "bidirectional"))
      (node (ref "U2") (pin "13") (pinfunction "RUN/SS1_13") (pintype "bidirectional"))
      (node (ref "U2") (pin "15") (pinfunction "RUN/SS3_15") (pintype "bidirectional"))
    )
    (net (code "212") (name "Net-(U2-RUN{slash}SS2)") (class "Default")
      (node (ref "C8") (pin "1") (pinfunction "1_1") (pintype "passive"))
      (node (ref "R11") (pin "2") (pinfunction "2_2") (pintype "passive"))
      (node (ref "R8") (pin "2") (pinfunction "2_2") (pintype "passive"))
      (node (ref "U2") (pin "14") (pinfunction "RUN/SS2_14") (pintype "bidirectional"))
    )
    (net (code "213") (name "Net-(U2-SKY)") (class "Default")
      (node (ref "C10") (pin "1") (pinfunction "1_1") (pintype "passive"))
      (node (ref "U2") (pin "25") (pinfunction "SKY_25") (pintype "bidirectional"))
    )
    (net (code "214") (name "Net-(U2-SW1)") (class "Default")
      (node (ref "D5") (pin "K") (pinfunction "K_K") (pintype "passive"))
      (node (ref "L2") (pin "1") (pinfunction "1_1") (pintype "passive"))
      (node (ref "U2") (pin "5") (pinfunction "SW1_5") (pintype "bidirectional"))
    )
    (net (code "215") (name "Net-(U2-SW2)") (class "Default")
      (node (ref "D6") (pin "K") (pinfunction "K_K") (pintype "passive"))
      (node (ref "L3") (pin "1") (pinfunction "1_1") (pintype "passive"))
      (node (ref "R13") (pin "2") (pinfunction "2_2") (pintype "passive"))
      (node (ref "U2") (pin "2") (pinfunction "SW2_2") (pintype "bidirectional"))
    )
    (net (code "216") (name "Net-(U2-SW3)") (class "Default")
      (node (ref "D7") (pin "K") (pinfunction "K_K") (pintype "passive"))
      (node (ref "L4") (pin "1") (pinfunction "1_1") (pintype "passive"))
      (node (ref "U2") (pin "4") (pinfunction "SW3_4") (pintype "bidirectional"))
    )
    (net (code "217") (name "Net-(U2-SW4)") (class "Default")
      (node (ref "D8") (pin "K") (pinfunction "K_K") (pintype "passive"))
      (node (ref "L5") (pin "1") (pinfunction "1_1") (pintype "passive"))
      (node (ref "U2") (pin "7") (pinfunction "SW4_7") (pintype "bidirectional"))
    )
    (net (code "218") (name "Net-(U2-SW5)") (class "Default")
      (node (ref "L1") (pin "2") (pinfunction "2_2") (pintype "passive"))
      (node (ref "U2") (pin "24") (pinfunction "SW5_24") (pintype "bidirectional"))
    )
    (net (code "219") (name "Net-(U3-IN)") (class "Default")
      (node (ref "C17") (pin "1") (pinfunction "1_1") (pintype "passive"))
      (node (ref "C19") (pin "1") (pinfunction "1_1") (pintype "passive"))
      (node (ref "L4") (pin "2") (pinfunction "2_2") (pintype "passive"))
      (node (ref "R18") (pin "2") (pinfunction "2_2") (pintype "passive"))
      (node (ref "U3") (pin "1") (pinfunction "IN_1") (pintype "bidirectional"))
    )
    (net (code "220") (name "Net-(U3-NR)") (class "Default")
      (node (ref "C20") (pin "1") (pinfunction "1_1") (pintype "passive"))
      (node (ref "U3") (pin "4") (pinfunction "NR_4") (pintype "bidirectional"))
    )
    (net (code "221") (name "Net-(U4-I1)") (class "Default")
      (node (ref "R34") (pin "1") (pinfunction "1_1") (pintype "passive"))
      (node (ref "U4") (pin "3") (pinfunction "I1_3") (pintype "bidirectional"))
    )
    (net (code "222") (name "Net-(U4-I2)") (class "Default")
      (node (ref "R35") (pin "1") (pinfunction "1_1") (pintype "passive"))
      (node (ref "U4") (pin "4") (pinfunction "I2_4") (pintype "bidirectional"))
    )
    (net (code "223") (name "Net-(U5-DM)") (class "Default")
      (node (ref "R35") (pin "2") (pinfunction "2_2") (pintype "passive"))
      (node (ref "U5") (pin "51") (pinfunction "DM_51") (pintype "bidirectional"))
    )
    (net (code "224") (name "Net-(U5-DP)") (class "Default")
      (node (ref "R34") (pin "2") (pinfunction "2_2") (pintype "passive"))
      (node (ref "U5") (pin "50") (pinfunction "DP_50") (pintype "bidirectional"))
    )
    (net (code "225") (name "Net-(U5-PA26{slash}TC-A0{slash}USB_ID{slash}USART2-TXD{slash}ABDAC-DATA1)") (class "Default")
      (node (ref "R38") (pin "1") (pinfunction "1_1") (pintype "passive"))
      (node (ref "U5") (pin "61") (pinfunction "PA26/TC-A0/USB_ID/USART2-TXD/ABDAC-DATA1_61") (pintype "bidirectional"))
    )
    (net (code "226") (name "Net-(U5-PA27{slash}TC-B0{slash}USB_VBOF{slash}USART2-RXD{slash}ABDAC-DATAN1)") (class "Default")
      (node (ref "R39") (pin "1") (pinfunction "1_1") (pintype "passive"))
      (node (ref "U5") (pin "62") (pinfunction "PA27/TC-B0/USB_VBOF/USART2-RXD/ABDAC-DATAN1_62") (pintype "bidirectional"))
    )
    (net (code "227") (name "Net-(U5-VBUS)") (class "Default")
      (node (ref "R33") (pin "1") (pinfunction "1_1") (pintype "passive"))
      (node (ref "U5") (pin "52") (pinfunction "VBUS_52") (pintype "bidirectional"))
    )
    (net (code "228") (name "Net-(U5-VDDOUT)") (class "Default")
      (node (ref "C25") (pin "1") (pinfunction "1_1") (pintype "passive"))
      (node (ref "C27") (pin "1") (pinfunction "1_1") (pintype "passive"))
      (node (ref "C29") (pin "1") (pinfunction "1_1") (pintype "passive"))
      (node (ref "C31") (pin "1") (pinfunction "1_1") (pintype "passive"))
      (node (ref "C32") (pin "1") (pinfunction "1_1") (pintype "passive"))
      (node (ref "C34") (pin "1") (pinfunction "1_1") (pintype "passive"))
      (node (ref "U5") (pin "20") (pinfunction "VDDOUT_20") (pintype "bidirectional"))
      (node (ref "U5") (pin "22") (pinfunction "VDDCORE_22") (pintype "bidirectional"))
      (node (ref "U5") (pin "53") (pinfunction "VDDPLL_53") (pintype "bidirectional"))
      (node (ref "U5") (pin "56") (pinfunction "VDDCORE_56") (pintype "bidirectional"))
      (node (ref "U5") (pin "8") (pinfunction "VDDCORE_8") (pintype "bidirectional"))
    )
    (net (code "229") (name "Net-(U8A-Y)") (class "Default")
      (node (ref "U8") (pin "4") (pinfunction "Y_4") (pintype "bidirectional"))
      (node (ref "U9") (pin "37") (pinfunction "PROGRAM_B_2_37") (pintype "bidirectional"))
    )
    (net (code "230") (name "Net-(U10A-Y)") (class "Default")
      (node (ref "U10") (pin "4") (pinfunction "Y_4") (pintype "bidirectional"))
      (node (ref "U9") (pin "70") (pinfunction "IO_L1P_CCLK_2_70") (pintype "bidirectional"))
    )
    (net (code "231") (name "Net-(U11-QA)") (class "Default")
      (node (ref "R45") (pin "2") (pinfunction "2_2") (pintype "passive"))
      (node (ref "U11") (pin "3") (pinfunction "QA_3") (pintype "bidirectional"))
    )
    (net (code "232") (name "Net-(U11-QB)") (class "Default")
      (node (ref "R52") (pin "2") (pinfunction "2_2") (pintype "passive"))
      (node (ref "U11") (pin "4") (pinfunction "QB_4") (pintype "bidirectional"))
    )
    (net (code "233") (name "Net-(U11-QC)") (class "Default")
      (node (ref "R51") (pin "2") (pinfunction "2_2") (pintype "passive"))
      (node (ref "U11") (pin "5") (pinfunction "QC_5") (pintype "bidirectional"))
    )
    (net (code "234") (name "Net-(U11-QD)") (class "Default")
      (node (ref "R50") (pin "2") (pinfunction "2_2") (pintype "passive"))
      (node (ref "U11") (pin "6") (pinfunction "QD_6") (pintype "bidirectional"))
    )
    (net (code "235") (name "Net-(U11-QE)") (class "Default")
      (node (ref "R49") (pin "2") (pinfunction "2_2") (pintype "passive"))
      (node (ref "U11") (pin "10") (pinfunction "QE_10") (pintype "bidirectional"))
    )
    (net (code "236") (name "Net-(U11-QF)") (class "Default")
      (node (ref "R48") (pin "2") (pinfunction "2_2") (pintype "passive"))
      (node (ref "U11") (pin "11") (pinfunction "QF_11") (pintype "bidirectional"))
    )
    (net (code "237") (name "Net-(U11-QG)") (class "Default")
      (node (ref "R47") (pin "2") (pinfunction "2_2") (pintype "passive"))
      (node (ref "U11") (pin "12") (pinfunction "QG_12") (pintype "bidirectional"))
    )
    (net (code "238") (name "Net-(U11-QH)") (class "Default")
      (node (ref "R46") (pin "2") (pinfunction "2_2") (pintype "passive"))
      (node (ref "U11") (pin "13") (pinfunction "QH_13") (pintype "bidirectional"))
    )
    (net (code "239") (name "Net-(U12-IN)") (class "Default")
      (node (ref "R61") (pin "2") (pinfunction "2_2") (pintype "passive"))
      (node (ref "RF1") (pin "1") (pinfunction "1_1") (pintype "passive"))
      (node (ref "RF2") (pin "1") (pinfunction "1_1") (pintype "passive"))
      (node (ref "U12") (pin "4") (pinfunction "IN_4") (pintype "bidirectional"))
    )
    (net (code "240") (name "Net-(U12-R1)") (class "Default")
      (node (ref "R61") (pin "1") (pinfunction "1_1") (pintype "passive"))
      (node (ref "U12") (pin "6") (pinfunction "R1_6") (pintype "bidirectional"))
    )
    (net (code "241") (name "Net-(U13-VO1)") (class "Default")
      (node (ref "BZ1") (pin "1") (pinfunction "1_1") (pintype "passive"))
      (node (ref "U13") (pin "8") (pinfunction "VO1_8") (pintype "bidirectional"))
    )
    (net (code "242") (name "Net-(U13-VO2)") (class "Default")
      (node (ref "BZ1") (pin "2") (pinfunction "2_2") (pintype "passive"))
      (node (ref "U13") (pin "7") (pinfunction "VO2_7") (pintype "bidirectional"))
    )
    (net (code "243") (name "Net-(U14-BST_A)") (class "Default")
      (node (ref "C74") (pin "1") (pinfunction "1_1") (pintype "passive"))
      (node (ref "U14") (pin "35") (pinfunction "BST_A_35") (pintype "bidirectional"))
    )
    (net (code "244") (name "Net-(U14-BST_B)") (class "Default")
      (node (ref "C75") (pin "1") (pinfunction "1_1") (pintype "passive"))
      (node (ref "U14") (pin "28") (pinfunction "BST_B_28") (pintype "bidirectional"))
    )
    (net (code "245") (name "Net-(U14-BST_C)") (class "Default")
      (node (ref "C76") (pin "1") (pinfunction "1_1") (pintype "passive"))
      (node (ref "U14") (pin "20") (pinfunction "BST_C_20") (pintype "bidirectional"))
    )
    (net (code "246") (name "Net-(U14-M1)") (class "Default")
      (node (ref "C72") (pin "1") (pinfunction "1_1") (pintype "passive"))
      (node (ref "U14") (pin "10") (pinfunction "VREG_10") (pintype "bidirectional"))
      (node (ref "U14") (pin "11") (pinfunction "M3_11") (pintype "bidirectional"))
      (node (ref "U14") (pin "13") (pinfunction "M1_13") (pintype "bidirectional"))
    )
    (net (code "247") (name "Net-(U14-OC_ADJ)") (class "Default")
      (node (ref "R62") (pin "2") (pinfunction "2_2") (pintype "passive"))
      (node (ref "U14") (pin "7") (pinfunction "OC_ADJ_7") (pintype "bidirectional"))
    )
    (net (code "248") (name "Net-(U14-OUT_B)") (class "Default")
      (node (ref "C75") (pin "2") (pinfunction "2_2") (pintype "passive"))
      (node (ref "R64") (pin "1") (pinfunction "1_1") (pintype "passive"))
      (node (ref "U14") (pin "30") (pinfunction "OUT_B_30") (pintype "bidirectional"))
      (node (ref "U15") (pin "4") (pinfunction "VIN+_4") (pintype "input"))
    )
    (net (code "249") (name "Net-(U14-OUT_C)") (class "Default")
      (node (ref "C76") (pin "2") (pinfunction "2_2") (pintype "passive"))
      (node (ref "R65") (pin "1") (pinfunction "1_1") (pintype "passive"))
      (node (ref "U14") (pin "22") (pinfunction "OUT_C_22") (pintype "bidirectional"))
      (node (ref "U16") (pin "4") (pinfunction "VIN+_4") (pintype "input"))
    )
    (net (code "250") (name "Net-(U17-BST_A)") (class "Default")
      (node (ref "C89") (pin "1") (pinfunction "1_1") (pintype "passive"))
      (node (ref "U17") (pin "35") (pinfunction "BST_A_35") (pintype "bidirectional"))
    )
    (net (code "251") (name "Net-(U17-BST_B)") (class "Default")
      (node (ref "C90") (pin "1") (pinfunction "1_1") (pintype "passive"))
      (node (ref "U17") (pin "28") (pinfunction "BST_B_28") (pintype "bidirectional"))
    )
    (net (code "252") (name "Net-(U17-BST_C)") (class "Default")
      (node (ref "C91") (pin "1") (pinfunction "1_1") (pintype "passive"))
      (node (ref "U17") (pin "20") (pinfunction "BST_C_20") (pintype "bidirectional"))
    )
    (net (code "253") (name "Net-(U17-M1)") (class "Default")
      (node (ref "C87") (pin "1") (pinfunction "1_1") (pintype "passive"))
      (node (ref "U17") (pin "10") (pinfunction "VREG_10") (pintype "bidirectional"))
      (node (ref "U17") (pin "11") (pinfunction "M3_11") (pintype "bidirectional"))
      (node (ref "U17") (pin "13") (pinfunction "M1_13") (pintype "bidirectional"))
    )
    (net (code "254") (name "Net-(U17-OC_ADJ)") (class "Default")
      (node (ref "R66") (pin "2") (pinfunction "2_2") (pintype "passive"))
      (node (ref "U17") (pin "7") (pinfunction "OC_ADJ_7") (pintype "bidirectional"))
    )
    (net (code "255") (name "Net-(U17-OUT_A)") (class "Default")
      (node (ref "C89") (pin "2") (pinfunction "2_2") (pintype "passive"))
      (node (ref "R68") (pin "1") (pinfunction "1_1") (pintype "passive"))
      (node (ref "U17") (pin "33") (pinfunction "OUT_A_33") (pintype "bidirectional"))
      (node (ref "U18") (pin "5") (pinfunction "VIN-_5") (pintype "input"))
    )
    (net (code "256") (name "Net-(U17-OUT_B)") (class "Default")
      (node (ref "C90") (pin "2") (pinfunction "2_2") (pintype "passive"))
      (node (ref "R69") (pin "1") (pinfunction "1_1") (pintype "passive"))
      (node (ref "U17") (pin "30") (pinfunction "OUT_B_30") (pintype "bidirectional"))
      (node (ref "U19") (pin "5") (pinfunction "VIN-_5") (pintype "input"))
    )
    (net (code "257") (name "Net-(U20-BST_A)") (class "Default")
      (node (ref "C104") (pin "1") (pinfunction "1_1") (pintype "passive"))
      (node (ref "U20") (pin "35") (pinfunction "BST_A_35") (pintype "bidirectional"))
    )
    (net (code "258") (name "Net-(U20-BST_B)") (class "Default")
      (node (ref "C105") (pin "1") (pinfunction "1_1") (pintype "passive"))
      (node (ref "U20") (pin "28") (pinfunction "BST_B_28") (pintype "bidirectional"))
    )
    (net (code "259") (name "Net-(U20-BST_C)") (class "Default")
      (node (ref "C106") (pin "1") (pinfunction "1_1") (pintype "passive"))
      (node (ref "U20") (pin "20") (pinfunction "BST_C_20") (pintype "bidirectional"))
    )
    (net (code "260") (name "Net-(U20-M1)") (class "Default")
      (node (ref "C102") (pin "1") (pinfunction "1_1") (pintype "passive"))
      (node (ref "U20") (pin "10") (pinfunction "VREG_10") (pintype "bidirectional"))
      (node (ref "U20") (pin "11") (pinfunction "M3_11") (pintype "bidirectional"))
      (node (ref "U20") (pin "13") (pinfunction "M1_13") (pintype "bidirectional"))
    )
    (net (code "261") (name "Net-(U20-OC_ADJ)") (class "Default")
      (node (ref "R70") (pin "2") (pinfunction "2_2") (pintype "passive"))
      (node (ref "U20") (pin "7") (pinfunction "OC_ADJ_7") (pintype "bidirectional"))
    )
    (net (code "262") (name "Net-(U20-OUT_B)") (class "Default")
      (node (ref "C105") (pin "2") (pinfunction "2_2") (pintype "passive"))
      (node (ref "R72") (pin "1") (pinfunction "1_1") (pintype "passive"))
      (node (ref "U20") (pin "30") (pinfunction "OUT_B_30") (pintype "bidirectional"))
      (node (ref "U21") (pin "4") (pinfunction "VIN+_4") (pintype "input"))
    )
    (net (code "263") (name "Net-(U20-OUT_C)") (class "Default")
      (node (ref "C106") (pin "2") (pinfunction "2_2") (pintype "passive"))
      (node (ref "R73") (pin "1") (pinfunction "1_1") (pintype "passive"))
      (node (ref "U20") (pin "22") (pinfunction "OUT_C_22") (pintype "bidirectional"))
      (node (ref "U22") (pin "4") (pinfunction "VIN+_4") (pintype "input"))
    )
    (net (code "264") (name "Net-(U23-BST_A)") (class "Default")
      (node (ref "C119") (pin "1") (pinfunction "1_1") (pintype "passive"))
      (node (ref "U23") (pin "35") (pinfunction "BST_A_35") (pintype "bidirectional"))
    )
    (net (code "265") (name "Net-(U23-BST_B)") (class "Default")
      (node (ref "C120") (pin "1") (pinfunction "1_1") (pintype "passive"))
      (node (ref "U23") (pin "28") (pinfunction "BST_B_28") (pintype "bidirectional"))
    )
    (net (code "266") (name "Net-(U23-BST_C)") (class "Default")
      (node (ref "C121") (pin "1") (pinfunction "1_1") (pintype "passive"))
      (node (ref "U23") (pin "20") (pinfunction "BST_C_20") (pintype "bidirectional"))
    )
    (net (code "267") (name "Net-(U23-M1)") (class "Default")
      (node (ref "C117") (pin "1") (pinfunction "1_1") (pintype "passive"))
      (node (ref "U23") (pin "10") (pinfunction "VREG_10") (pintype "bidirectional"))
      (node (ref "U23") (pin "11") (pinfunction "M3_11") (pintype "bidirectional"))
      (node (ref "U23") (pin "13") (pinfunction "M1_13") (pintype "bidirectional"))
    )
    (net (code "268") (name "Net-(U23-OC_ADJ)") (class "Default")
      (node (ref "R74") (pin "2") (pinfunction "2_2") (pintype "passive"))
      (node (ref "U23") (pin "7") (pinfunction "OC_ADJ_7") (pintype "bidirectional"))
    )
    (net (code "269") (name "Net-(U23-OUT_A)") (class "Default")
      (node (ref "C119") (pin "2") (pinfunction "2_2") (pintype "passive"))
      (node (ref "R76") (pin "1") (pinfunction "1_1") (pintype "passive"))
      (node (ref "U23") (pin "33") (pinfunction "OUT_A_33") (pintype "bidirectional"))
      (node (ref "U24") (pin "5") (pinfunction "VIN-_5") (pintype "input"))
    )
    (net (code "270") (name "Net-(U23-OUT_B)") (class "Default")
      (node (ref "C120") (pin "2") (pinfunction "2_2") (pintype "passive"))
      (node (ref "R77") (pin "1") (pinfunction "1_1") (pintype "passive"))
      (node (ref "U23") (pin "30") (pinfunction "OUT_B_30") (pintype "bidirectional"))
      (node (ref "U25") (pin "5") (pinfunction "VIN-_5") (pintype "input"))
    )
    (net (code "271") (name "Net-(U26-QH)") (class "Default")
      (node (ref "U26") (pin "9") (pinfunction "QH_9") (pintype "bidirectional"))
      (node (ref "U27") (pin "10") (pinfunction "SI_10") (pintype "bidirectional"))
    )
    (net (code "272") (name "Net-(U27-A)") (class "Default")
      (node (ref "R98") (pin "2") (pinfunction "2_2") (pintype "passive"))
      (node (ref "R99") (pin "1") (pinfunction "1_1") (pintype "passive"))
      (node (ref "U27") (pin "11") (pinfunction "A_11") (pintype "bidirectional"))
    )
    (net (code "273") (name "Net-(U29-AINP)") (class "Default")
      (node (ref "U29") (pin "3") (pinfunction "MXO_3") (pintype "bidirectional"))
      (node (ref "U29") (pin "4") (pinfunction "AINP_4") (pintype "bidirectional"))
    )
    (net (code "274") (name "Net-(U29-SDO)") (class "Default")
      (node (ref "R102") (pin "1") (pinfunction "1_1") (pintype "passive"))
      (node (ref "U29") (pin "19") (pinfunction "SDO_19") (pintype "bidirectional"))
    )
    (net (code "275") (name "Net-(U30-E)") (class "Default")
      (node (ref "R104") (pin "2") (pinfunction "2_2") (pintype "passive"))
      (node (ref "R105") (pin "2") (pinfunction "2_2") (pintype "passive"))
      (node (ref "U30") (pin "3") (pinfunction "E_3") (pintype "bidirectional"))
    )
    (net (code "276") (name "Net-(U30-QH)") (class "Default")
      (node (ref "U30") (pin "9") (pinfunction "QH_9") (pintype "bidirectional"))
      (node (ref "U31") (pin "10") (pinfunction "SI_10") (pintype "bidirectional"))
    )
    (net (code "277") (name "Net-(U33-AINP)") (class "Default")
      (node (ref "U33") (pin "3") (pinfunction "MXO_3") (pintype "bidirectional"))
      (node (ref "U33") (pin "4") (pinfunction "AINP_4") (pintype "bidirectional"))
    )
    (net (code "278") (name "Net-(U33-SDO)") (class "Default")
      (node (ref "R108") (pin "1") (pinfunction "1_1") (pintype "passive"))
      (node (ref "U33") (pin "19") (pinfunction "SDO_19") (pintype "bidirectional"))
    )
    (net (code "279") (name "Net-(U34-R1)") (class "Default")
      (node (ref "R111") (pin "1") (pinfunction "1_1") (pintype "passive"))
      (node (ref "U34") (pin "6") (pinfunction "R1_6") (pintype "bidirectional"))
    )
    (net (code "280") (name "Net-(U35-R1)") (class "Default")
      (node (ref "R113") (pin "1") (pinfunction "1_1") (pintype "passive"))
      (node (ref "U35") (pin "6") (pinfunction "R1_6") (pintype "bidirectional"))
    )
    (net (code "281") (name "Net-(U36-VIN-)") (class "Default")
      (node (ref "C158") (pin "1") (pinfunction "1_1") (pintype "passive"))
      (node (ref "C159") (pin "1") (pinfunction "1_1") (pintype "passive"))
      (node (ref "C160") (pin "1") (pinfunction "1_1") (pintype "passive"))
      (node (ref "C161") (pin "P") (pinfunction "P_P") (pintype "passive"))
      (node (ref "R114") (pin "2") (pinfunction "2_2") (pintype "passive"))
      (node (ref "U36") (pin "2") (pinfunction "VIN-_2") (pintype "input"))
      (node (ref "U37") (pin "21") (pinfunction "PVDD_C_21") (pintype "bidirectional"))
      (node (ref "U37") (pin "29") (pinfunction "PVDD_B_29") (pintype "bidirectional"))
      (node (ref "U37") (pin "34") (pinfunction "PVDD_A_34") (pintype "bidirectional"))
    )
    (net (code "282") (name "Net-(U37-BST_A)") (class "Default")
      (node (ref "C155") (pin "1") (pinfunction "1_1") (pintype "passive"))
      (node (ref "U37") (pin "35") (pinfunction "BST_A_35") (pintype "bidirectional"))
    )
    (net (code "283") (name "Net-(U37-BST_B)") (class "Default")
      (node (ref "C156") (pin "1") (pinfunction "1_1") (pintype "passive"))
      (node (ref "U37") (pin "28") (pinfunction "BST_B_28") (pintype "bidirectional"))
    )
    (net (code "284") (name "Net-(U37-BST_C)") (class "Default")
      (node (ref "C157") (pin "1") (pinfunction "1_1") (pintype "passive"))
      (node (ref "U37") (pin "20") (pinfunction "BST_C_20") (pintype "bidirectional"))
    )
    (net (code "285") (name "Net-(U37-M1)") (class "Default")
      (node (ref "C153") (pin "1") (pinfunction "1_1") (pintype "passive"))
      (node (ref "U37") (pin "10") (pinfunction "VREG_10") (pintype "bidirectional"))
      (node (ref "U37") (pin "11") (pinfunction "M3_11") (pintype "bidirectional"))
      (node (ref "U37") (pin "13") (pinfunction "M1_13") (pintype "bidirectional"))
    )
    (net (code "286") (name "Net-(U37-OC_ADJ)") (class "Default")
      (node (ref "R117") (pin "2") (pinfunction "2_2") (pintype "passive"))
      (node (ref "U37") (pin "7") (pinfunction "OC_ADJ_7") (pintype "bidirectional"))
    )
    (net (code "287") (name "Net-(X1-OUT)") (class "Default")
      (node (ref "R31") (pin "1") (pinfunction "1_1") (pintype "passive"))
      (node (ref "R32") (pin "1") (pinfunction "1_1") (pintype "passive"))
      (node (ref "X1") (pin "3") (pinfunction "OUT_3") (pintype "bidirectional"))
    )
    (net (code "288") (name "OSC_EN") (class "Default")
      (node (ref "U5") (pin "42") (pinfunction "PA29/XOUT1/TC-CLK0/TC-CLK1/SPI0-MOSI_42") (pintype "bidirectional"))
      (node (ref "X1") (pin "1") (pinfunction "EN_1") (pintype "bidirectional"))
    )
    (net (code "289") (name "POWER_SCL") (class "Default")
      (node (ref "R2") (pin "1") (pinfunction "1_1") (pintype "passive"))
      (node (ref "U1") (pin "5") (pinfunction "SCL_5") (pintype "bidirectional"))
      (node (ref "U5") (pin "28") (pinfunction "PA09/SCL/SPI0-NPCS2/USART1-CTS_28") (pintype "bidirectional"))
      (node (ref "U5") (pin "46") (pinfunction "PA22/TC-B1/PWM6/TRIGGER/ABDAC-DATA0_46") (pintype "bidirectional"))
    )
    (net (code "290") (name "POWER_SDA") (class "Default")
      (node (ref "R3") (pin "1") (pinfunction "1_1") (pintype "passive"))
      (node (ref "U1") (pin "6") (pinfunction "SDA_6") (pintype "bidirectional"))
      (node (ref "U5") (pin "29") (pinfunction "PA10/SDA/SPI0-NPCS3/USART1-RTS_29") (pintype "bidirectional"))
      (node (ref "U5") (pin "45") (pinfunction "PA21/TC-A1/PWM2/USART2-TXD/SSC-TXFRM_45") (pintype "bidirectional"))
    )
    (net (code "291") (name "PWR_5V") (class "Default")
      (node (ref "R22") (pin "2") (pinfunction "2_2") (pintype "passive"))
      (node (ref "U3") (pin "3") (pinfunction "EN_3") (pintype "bidirectional"))
      (node (ref "U9") (pin "40") (pinfunction "IO_L64N_D9_2_40") (pintype "bidirectional"))
    )
    (net (code "292") (name "PWR_12V") (class "Default")
      (node (ref "R8") (pin "1") (pinfunction "1_1") (pintype "passive"))
      (node (ref "U5") (pin "43") (pinfunction "PB07/SSC-RXDAT/USART1-DSR/ABDAC-DATAN0_43") (pintype "bidirectional"))
    )
    (net (code "293") (name "PWR_MOTOR1") (class "Default")
      (node (ref "R27") (pin "2") (pinfunction "2_2") (pintype "passive"))
      (node (ref "R29") (pin "2") (pinfunction "2_2") (pintype "passive"))
      (node (ref "U5") (pin "6") (pinfunction "PB00/TC-A0/USART2-CTS_6") (pintype "bidirectional"))
    )
    (net (code "294") (name "PWR_MOTOR2") (class "Default")
      (node (ref "R28") (pin "2") (pinfunction "2_2") (pintype "passive"))
      (node (ref "R30") (pin "2") (pinfunction "2_2") (pintype "passive"))
      (node (ref "U5") (pin "44") (pinfunction "PA20/TC-CLK0/USART1-CLK/USART2-RXD/SSC-TXDAT_44") (pintype "bidirectional"))
    )
    (net (code "295") (name "SPI_MISO") (class "Default")
      (node (ref "CN18") (pin "7") (pinfunction "7_7") (pintype "passive"))
      (node (ref "U5") (pin "39") (pinfunction "PA18/XIN0/PWM5/USART0-RXD/SPI0-MISO/SSC-RXFRM_39") (pintype "bidirectional"))
      (node (ref "U7") (pin "2") (pinfunction "SO/SIO1_2") (pintype "bidirectional"))
      (node (ref "U9") (pin "66") (pinfunction "IO_L2N_CMPMOSI_2_66") (pintype "bidirectional"))
    )
    (net (code "296") (name "SPI_MOSI") (class "Default")
      (node (ref "CN18") (pin "6") (pinfunction "6_6") (pintype "passive"))
      (node (ref "U5") (pin "34") (pinfunction "PA14/PWM3/INT2/SPI0-MOSI/GCLK2_34") (pintype "bidirectional"))
      (node (ref "U7") (pin "5") (pinfunction "SI/SIO0_5") (pintype "bidirectional"))
      (node (ref "U9") (pin "65") (pinfunction "IO_L3P_D0_DIN_MISO_MISO1_2_65") (pintype "bidirectional"))
    )
    (net (code "297") (name "SPI_SCLK") (class "Default")
      (node (ref "CN18") (pin "5") (pinfunction "5_5") (pintype "passive"))
      (node (ref "U10") (pin "2") (pinfunction "B_2") (pintype "bidirectional"))
      (node (ref "U5") (pin "35") (pinfunction "PA15/PWM4/USART2-CLK/SPI0-SCK_35") (pintype "bidirectional"))
      (node (ref "U7") (pin "6") (pinfunction "SCLK_6") (pintype "bidirectional"))
      (node (ref "U9") (pin "56") (pinfunction "IO_L30P_GCLK1_D13_2_56") (pintype "bidirectional"))
    )
    (net (code "298") (name "VBAT") (class "Default")
      (node (ref "C2") (pin "1") (pinfunction "1_1") (pintype "passive"))
      (node (ref "C3") (pin "P") (pinfunction "P_P") (pintype "passive"))
      (node (ref "C4") (pin "P") (pinfunction "P_P") (pintype "passive"))
      (node (ref "CN2") (pin "4") (pinfunction "4_4") (pintype "passive"))
      (node (ref "CN2") (pin "8") (pinfunction "8_8") (pintype "passive"))
      (node (ref "D2") (pin "K") (pinfunction "K_K") (pintype "passive"))
      (node (ref "D3") (pin "A") (pinfunction "A_A") (pintype "passive"))
      (node (ref "Q3") (pin "1") (pinfunction "S_1") (pintype "passive"))
      (node (ref "Q3") (pin "2") (pinfunction "S_2") (pintype "passive"))
      (node (ref "Q3") (pin "3") (pinfunction "S_3") (pintype "passive"))
      (node (ref "Q4") (pin "1") (pinfunction "S_1") (pintype "passive"))
      (node (ref "Q4") (pin "2") (pinfunction "S_2") (pintype "passive"))
      (node (ref "Q4") (pin "3") (pinfunction "S_3") (pintype "passive"))
      (node (ref "R23") (pin "2") (pinfunction "2_2") (pintype "passive"))
      (node (ref "R24") (pin "2") (pinfunction "2_2") (pintype "passive"))
      (node (ref "R4") (pin "2") (pinfunction "2_2") (pintype "passive"))
      (node (ref "SW1") (pin "1") (pinfunction "B_1") (pintype "passive"))
    )
    (net (code "299") (name "VCC{slash}1") (class "Default")
      (node (ref "C77") (pin "1") (pinfunction "1_1") (pintype "passive"))
      (node (ref "C78") (pin "1") (pinfunction "1_1") (pintype "passive"))
      (node (ref "C79") (pin "1") (pinfunction "1_1") (pintype "passive"))
      (node (ref "C80") (pin "P") (pinfunction "P_P") (pintype "passive"))
      (node (ref "C92") (pin "1") (pinfunction "1_1") (pintype "passive"))
      (node (ref "C93") (pin "1") (pinfunction "1_1") (pintype "passive"))
      (node (ref "C94") (pin "1") (pinfunction "1_1") (pintype "passive"))
      (node (ref "C95") (pin "P") (pinfunction "P_P") (pintype "passive"))
      (node (ref "F2") (pin "2") (pinfunction "2_2") (pintype "passive"))
      (node (ref "R99") (pin "2") (pinfunction "2_2") (pintype "passive"))
      (node (ref "U14") (pin "21") (pinfunction "PVDD_C_21") (pintype "bidirectional"))
      (node (ref "U14") (pin "29") (pinfunction "PVDD_B_29") (pintype "bidirectional"))
      (node (ref "U14") (pin "34") (pinfunction "PVDD_A_34") (pintype "bidirectional"))
      (node (ref "U17") (pin "21") (pinfunction "PVDD_C_21") (pintype "bidirectional"))
      (node (ref "U17") (pin "29") (pinfunction "PVDD_B_29") (pintype "bidirectional"))
      (node (ref "U17") (pin "34") (pinfunction "PVDD_A_34") (pintype "bidirectional"))
    )
    (net (code "300") (name "VCC{slash}2") (class "Default")
      (node (ref "C107") (pin "1") (pinfunction "1_1") (pintype "passive"))
      (node (ref "C108") (pin "1") (pinfunction "1_1") (pintype "passive"))
      (node (ref "C109") (pin "1") (pinfunction "1_1") (pintype "passive"))
      (node (ref "C110") (pin "P") (pinfunction "P_P") (pintype "passive"))
      (node (ref "C122") (pin "1") (pinfunction "1_1") (pintype "passive"))
      (node (ref "C123") (pin "1") (pinfunction "1_1") (pintype "passive"))
      (node (ref "C124") (pin "1") (pinfunction "1_1") (pintype "passive"))
      (node (ref "C125") (pin "P") (pinfunction "P_P") (pintype "passive"))
      (node (ref "F3") (pin "2") (pinfunction "2_2") (pintype "passive"))
      (node (ref "R104") (pin "1") (pinfunction "1_1") (pintype "passive"))
      (node (ref "R114") (pin "1") (pinfunction "1_1") (pintype "passive"))
      (node (ref "U20") (pin "21") (pinfunction "PVDD_C_21") (pintype "bidirectional"))
      (node (ref "U20") (pin "29") (pinfunction "PVDD_B_29") (pintype "bidirectional"))
      (node (ref "U20") (pin "34") (pinfunction "PVDD_A_34") (pintype "bidirectional"))
      (node (ref "U23") (pin "21") (pinfunction "PVDD_C_21") (pintype "bidirectional"))
      (node (ref "U23") (pin "29") (pinfunction "PVDD_B_29") (pintype "bidirectional"))
      (node (ref "U23") (pin "34") (pinfunction "PVDD_A_34") (pintype "bidirectional"))
      (node (ref "U36") (pin "1") (pinfunction "VIN+_1") (pintype "input"))
    )
    (net (code "301") (name "VOLT_12V") (class "Default")
      (node (ref "C6") (pin "1") (pinfunction "1_1") (pintype "passive"))
      (node (ref "R123") (pin "2") (pinfunction "2_2") (pintype "passive"))
      (node (ref "U5") (pin "14") (pinfunction "PA08/AD5/PWM1/USART1-RI/SSC-RXCLK_14") (pintype "bidirectional"))
    )
    (net (code "302") (name "VOLT_BAT") (class "Default")
      (node (ref "C5") (pin "1") (pinfunction "1_1") (pintype "passive"))
      (node (ref "R122") (pin "2") (pinfunction "2_2") (pintype "passive"))
      (node (ref "U5") (pin "9") (pinfunction "PA03/AD0/GCLK0/USB_ID/ABDAC-DATA0_9") (pintype "bidirectional"))
    )
    (net (code "303") (name "XBEE_RX") (class "Default")
      (node (ref "CN7") (pin "2") (pinfunction "DOUT_2") (pintype "bidirectional"))
      (node (ref "U9") (pin "118") (pinfunction "IO_L63N_SCP6_0_118") (pintype "bidirectional"))
    )
    (net (code "304") (name "XBEE_TX") (class "Default")
      (node (ref "CN7") (pin "3") (pinfunction "DIN/~{CONFIG}_3") (pintype "bidirectional"))
      (node (ref "U9") (pin "120") (pinfunction "IO_L62N_VREF_0_120") (pintype "bidirectional"))
    )
    (net (code "305") (name "unconnected-(CN3-ID-Pad4)") (class "Default")
      (node (ref "CN3") (pin "4") (pinfunction "ID_4") (pintype "passive"))
    )
    (net (code "306") (name "unconnected-(CN7-AD1{slash}DIO1-Pad19)") (class "Default")
      (node (ref "CN7") (pin "19") (pinfunction "AD1/DIO1_19") (pintype "bidirectional"))
    )
    (net (code "307") (name "unconnected-(CN7-AD2{slash}DIO2-Pad18)") (class "Default")
      (node (ref "CN7") (pin "18") (pinfunction "AD2/DIO2_18") (pintype "bidirectional"))
    )
    (net (code "308") (name "unconnected-(CN7-AD3{slash}DIO3-Pad17)") (class "Default")
      (node (ref "CN7") (pin "17") (pinfunction "AD3/DIO3_17") (pintype "bidirectional"))
    )
    (net (code "309") (name "unconnected-(CN7-ASSOC{slash}DIO5-Pad15)") (class "Default")
      (node (ref "CN7") (pin "15") (pinfunction "ASSOC/DIO5_15") (pintype "bidirectional"))
    )
    (net (code "310") (name "unconnected-(CN7-COM_BTN{slash}AD0{slash}DIO0-Pad20)") (class "Default")
      (node (ref "CN7") (pin "20") (pinfunction "COM_BTN/AD0/DIO0_20") (pintype "bidirectional"))
    )
    (net (code "311") (name "unconnected-(CN7-DIO4-Pad11)") (class "Default")
      (node (ref "CN7") (pin "11") (pinfunction "DIO4_11") (pintype "bidirectional"))
    )
    (net (code "312") (name "unconnected-(CN7-DIO11-Pad7)") (class "Default")
      (node (ref "CN7") (pin "7") (pinfunction "DIO11_7") (pintype "bidirectional"))
    )
    (net (code "313") (name "unconnected-(CN7-DIO12-Pad4)") (class "Default")
      (node (ref "CN7") (pin "4") (pinfunction "DIO12_4") (pintype "bidirectional"))
    )
    (net (code "314") (name "unconnected-(CN7-ON{slash}~{SLEEP}-Pad13)") (class "Default")
      (node (ref "CN7") (pin "13") (pinfunction "ON/~{SLEEP}_13") (pintype "bidirectional"))
    )
    (net (code "315") (name "unconnected-(CN7-RSSI{slash}PWM{slash}DIO10-Pad6)") (class "Default")
      (node (ref "CN7") (pin "6") (pinfunction "RSSI/PWM/DIO10_6") (pintype "bidirectional"))
    )
    (net (code "316") (name "unconnected-(CN7-RSVD-Pad8)") (class "Default")
      (node (ref "CN7") (pin "8") (pinfunction "RSVD_8") (pintype "bidirectional"))
    )
    (net (code "317") (name "unconnected-(CN7-VREF-Pad14)") (class "Default")
      (node (ref "CN7") (pin "14") (pinfunction "VREF_14") (pintype "bidirectional"))
    )
    (net (code "318") (name "unconnected-(CN7-~{DTR}{slash}SLEEP_RQ{slash}DIO8-Pad9)") (class "Default")
      (node (ref "CN7") (pin "9") (pinfunction "~{DTR}/SLEEP_RQ/DIO8_9") (pintype "bidirectional"))
    )
    (net (code "319") (name "unconnected-(CN7-~{RTS}{slash}DIO6-Pad16)") (class "Default")
      (node (ref "CN7") (pin "16") (pinfunction "~{RTS}/DIO6_16") (pintype "bidirectional"))
    )
    (net (code "320") (name "unconnected-(SW2-PadB1)") (class "Default")
      (node (ref "SW2") (pin "B1") (pinfunction "B1_B1") (pintype "passive"))
    )
    (net (code "321") (name "unconnected-(SW3-PadB1)") (class "Default")
      (node (ref "SW3") (pin "B1") (pinfunction "B1_B1") (pintype "passive"))
    )
    (net (code "322") (name "unconnected-(U2-PG-Pad23)") (class "Default")
      (node (ref "U2") (pin "23") (pinfunction "PG_23") (pintype "bidirectional"))
    )
    (net (code "323") (name "unconnected-(U5-PA25{slash}INT5{slash}PWM3{slash}SPI0-MISO-Pad60)") (class "Default")
      (node (ref "U5") (pin "60") (pinfunction "PA25/INT5/PWM3/SPI0-MISO_60") (pintype "bidirectional"))
    )
    (net (code "324") (name "unconnected-(U6-IREDC-Pad2)") (class "Default")
      (node (ref "U6") (pin "2") (pinfunction "IREDC_2") (pintype "bidirectional"))
    )
    (net (code "325") (name "unconnected-(U7-NC{slash}SIO3-Pad7)") (class "Default")
      (node (ref "U7") (pin "7") (pinfunction "NC/SIO3_7") (pintype "bidirectional"))
    )
    (net (code "326") (name "unconnected-(U9A-IO_L12N_D2_MISO3_2-Pad61)") (class "Default")
      (node (ref "U9") (pin "61") (pinfunction "IO_L12N_D2_MISO3_2_61") (pintype "bidirectional"))
    )
    (net (code "327") (name "unconnected-(U9A-IO_L12P_D1_MISO2_2-Pad62)") (class "Default")
      (node (ref "U9") (pin "62") (pinfunction "IO_L12P_D1_MISO2_2_62") (pintype "bidirectional"))
    )
    (net (code "328") (name "unconnected-(U9A-IO_L13N_D10_2-Pad59)") (class "Default")
      (node (ref "U9") (pin "59") (pinfunction "IO_L13N_D10_2_59") (pintype "bidirectional"))
    )
    (net (code "329") (name "unconnected-(U9A-IO_L13P_M1_2-Pad60)") (class "Default")
      (node (ref "U9") (pin "60") (pinfunction "IO_L13P_M1_2_60") (pintype "bidirectional"))
    )
    (net (code "330") (name "unconnected-(U9A-IO_L14N_D12_2-Pad57)") (class "Default")
      (node (ref "U9") (pin "57") (pinfunction "IO_L14N_D12_2_57") (pintype "bidirectional"))
    )
    (net (code "331") (name "unconnected-(U9A-IO_L14P_D11_2-Pad58)") (class "Default")
      (node (ref "U9") (pin "58") (pinfunction "IO_L14P_D11_2_58") (pintype "bidirectional"))
    )
    (net (code "332") (name "unconnected-(U9A-IO_L30N_GCLK0_USERCCLK_2-Pad55)") (class "Default")
      (node (ref "U9") (pin "55") (pinfunction "IO_L30N_GCLK0_USERCCLK_2_55") (pintype "bidirectional"))
    )
    (net (code "333") (name "unconnected-(U9A-IO_L31P_GCLK31_D14_2-Pad51)") (class "Default")
      (node (ref "U9") (pin "51") (pinfunction "IO_L31P_GCLK31_D14_2_51") (pintype "bidirectional"))
    )
    (net (code "334") (name "unconnected-(U9A-IO_L48N_RDWR_B_VREF_2-Pad47)") (class "Default")
      (node (ref "U9") (pin "47") (pinfunction "IO_L48N_RDWR_B_VREF_2_47") (pintype "bidirectional"))
    )
    (net (code "335") (name "unconnected-(U9A-IO_L49N_D4_2-Pad45)") (class "Default")
      (node (ref "U9") (pin "45") (pinfunction "IO_L49N_D4_2_45") (pintype "bidirectional"))
    )
    (net (code "336") (name "unconnected-(U9A-IO_L49P_D3_2-Pad46)") (class "Default")
      (node (ref "U9") (pin "46") (pinfunction "IO_L49P_D3_2_46") (pintype "bidirectional"))
    )
    (net (code "337") (name "unconnected-(U9A-IO_L62N_D6_2-Pad43)") (class "Default")
      (node (ref "U9") (pin "43") (pinfunction "IO_L62N_D6_2_43") (pintype "bidirectional"))
    )
    (net (code "338") (name "unconnected-(U9A-IO_L62P_D5_2-Pad44)") (class "Default")
      (node (ref "U9") (pin "44") (pinfunction "IO_L62P_D5_2_44") (pintype "bidirectional"))
    )
    (net (code "339") (name "unconnected-(U9A-IO_L64P_D8_2-Pad41)") (class "Default")
      (node (ref "U9") (pin "41") (pinfunction "IO_L64P_D8_2_41") (pintype "bidirectional"))
    )
    (net (code "340") (name "unconnected-(U9A-IO_L65N_CSO_B_2-Pad38)") (class "Default")
      (node (ref "U9") (pin "38") (pinfunction "IO_L65N_CSO_B_2_38") (pintype "bidirectional"))
    )
    (net (code "341") (name "unconnected-(U26-~{QH}-Pad7)") (class "Default")
      (node (ref "U26") (pin "7") (pinfunction "~{QH}_7") (pintype "bidirectional"))
    )
    (net (code "342") (name "unconnected-(U27-QH-Pad9)") (class "Default")
      (node (ref "U27") (pin "9") (pinfunction "QH_9") (pintype "bidirectional"))
    )
    (net (code "343") (name "unconnected-(U29-GPIO0-Pad22)") (class "Default")
      (node (ref "U29") (pin "22") (pinfunction "GPIO0_22") (pintype "bidirectional"))
    )
    (net (code "344") (name "unconnected-(U30-~{QH}-Pad7)") (class "Default")
      (node (ref "U30") (pin "7") (pinfunction "~{QH}_7") (pintype "bidirectional"))
    )
    (net (code "345") (name "unconnected-(U31-QH-Pad9)") (class "Default")
      (node (ref "U31") (pin "9") (pinfunction "QH_9") (pintype "bidirectional"))
    )
    (net (code "346") (name "unconnected-(U33-GPIO0-Pad22)") (class "Default")
      (node (ref "U33") (pin "22") (pinfunction "GPIO0_22") (pintype "bidirectional"))
    )
    (net (code "347") (name "unconnected-(U38-CONV{slash}IN-Pad2)") (class "Default")
      (node (ref "U38") (pin "2") (pinfunction "CONV/IN_2") (pintype "bidirectional"))
    )
    (net (code "348") (name "unconnected-(U38-FUNC-Pad3)") (class "Default")
      (node (ref "U38") (pin "3") (pinfunction "FUNC_3") (pintype "bidirectional"))
    )
    (net (code "349") (name "unconnected-(U40-CONV{slash}IN-Pad2)") (class "Default")
      (node (ref "U40") (pin "2") (pinfunction "CONV/IN_2") (pintype "bidirectional"))
    )
    (net (code "350") (name "unconnected-(U40-FUNC-Pad3)") (class "Default")
      (node (ref "U40") (pin "3") (pinfunction "FUNC_3") (pintype "bidirectional"))
    )
    (net (code "351") (name "unconnected-(U41-CONV{slash}IN-Pad2)") (class "Default")
      (node (ref "U41") (pin "2") (pinfunction "CONV/IN_2") (pintype "bidirectional"))
    )
    (net (code "352") (name "unconnected-(U41-FUNC-Pad3)") (class "Default")
      (node (ref "U41") (pin "3") (pinfunction "FUNC_3") (pintype "bidirectional"))
    )
    (net (code "353") (name "~{ADC1_CS}") (class "Default")
      (node (ref "R103") (pin "1") (pinfunction "1_1") (pintype "passive"))
      (node (ref "U29") (pin "16") (pinfunction "~{CS}_16") (pintype "bidirectional"))
      (node (ref "U9") (pin "92") (pinfunction "IO_L41N_GCLK8_1_92") (pintype "bidirectional"))
    )
    (net (code "354") (name "~{ADC2_CS}") (class "Default")
      (node (ref "R109") (pin "1") (pinfunction "1_1") (pintype "passive"))
      (node (ref "U33") (pin "16") (pinfunction "~{CS}_16") (pintype "bidirectional"))
      (node (ref "U9") (pin "17") (pinfunction "IO_L43P_GCLK23_3_17") (pintype "bidirectional"))
    )
    (net (code "355") (name "~{FLASH_CS}") (class "Default")
      (node (ref "U5") (pin "37") (pinfunction "PA17/TC-CLK2/SPI0-SCK/SPI0-NPCS1/USART1-RXD_37") (pintype "bidirectional"))
      (node (ref "U7") (pin "1") (pinfunction "~{CS}_1") (pintype "bidirectional"))
    )
    (net (code "356") (name "~{FPGA_CS}") (class "Default")
      (node (ref "U5") (pin "27") (pinfunction "PB05/USART1-RTS/SPI0-NPCS2/PWM5_27") (pintype "bidirectional"))
      (node (ref "U9") (pin "67") (pinfunction "IO_L2P_CMPCLK_2_67") (pintype "bidirectional"))
    )
    (net (code "357") (name "~{FPGA_INIT}") (class "Default")
      (node (ref "U5") (pin "38") (pinfunction "PB06/SSC-RXCLK/USART1-DCD/ABDAC-DATA0_38") (pintype "bidirectional"))
      (node (ref "U9") (pin "39") (pinfunction "IO_L65P_INIT_B_2_39") (pintype "bidirectional"))
    )
    (net (code "358") (name "~{FPGA_PROG}") (class "Default")
      (node (ref "R44") (pin "2") (pinfunction "2_2") (pintype "passive"))
      (node (ref "U5") (pin "36") (pinfunction "PA16/PWM4/TC-CLK1/SPI0-NPCS0_36") (pintype "bidirectional"))
      (node (ref "U8") (pin "1") (pinfunction "A_1") (pintype "bidirectional"))
      (node (ref "U8") (pin "2") (pinfunction "B_2") (pintype "bidirectional"))
    )
    (net (code "359") (name "~{LED3}") (class "Default")
      (node (ref "LED3") (pin "K") (pinfunction "K_K") (pintype "passive"))
      (node (ref "U5") (pin "55") (pinfunction "PB09/SSC-TXCLK/USART1-RI/ABDAC-DATAN1_55") (pintype "bidirectional"))
    )
    (net (code "360") (name "~{MCU_RESET}") (class "Default")
      (node (ref "R36") (pin "1") (pinfunction "1_1") (pintype "passive"))
      (node (ref "SW2") (pin "B2") (pinfunction "B2_B2") (pintype "passive"))
      (node (ref "U5") (pin "63") (pinfunction "~{RESET}_63") (pintype "bidirectional"))
    )
    (net (code "361") (name "~{MOT1_2_DO}") (class "Default")
      (node (ref "U27") (pin "7") (pinfunction "~{QH}_7") (pintype "bidirectional"))
      (node (ref "U9") (pin "93") (pinfunction "IO_L41P_GCLK9_IRDY1_1_93") (pintype "bidirectional"))
    )
    (net (code "362") (name "~{MOT1_2_LATCH}") (class "Default")
      (node (ref "U26") (pin "1") (pinfunction "S/~{L}_1") (pintype "bidirectional"))
      (node (ref "U27") (pin "1") (pinfunction "S/~{L}_1") (pintype "bidirectional"))
      (node (ref "U9") (pin "95") (pinfunction "IO_L40P_GCLK11_1_95") (pintype "bidirectional"))
    )
    (net (code "363") (name "~{MOT1_FAULT}") (class "Default")
      (node (ref "RA2") (pin "B1") (pinfunction "1_B1") (pintype "passive"))
      (node (ref "U9") (pin "104") (pinfunction "IO_L1N__VREF_1_104") (pintype "bidirectional"))
    )
    (net (code "364") (name "~{MOT1_HU_5}") (class "Default")
      (node (ref "CN9") (pin "1.3") (pinfunction "HU_1.3") (pintype "bidirectional"))
      (node (ref "CN9") (pin "2.2") (pinfunction "HU_2.2") (pintype "bidirectional"))
      (node (ref "R80") (pin "2") (pinfunction "2_2") (pintype "passive"))
      (node (ref "U26") (pin "5") (pinfunction "G_5") (pintype "bidirectional"))
    )
    (net (code "365") (name "~{MOT1_HV_5}") (class "Default")
      (node (ref "CN9") (pin "1.4") (pinfunction "HV_1.4") (pintype "bidirectional"))
      (node (ref "CN9") (pin "2.3") (pinfunction "HV_2.3") (pintype "bidirectional"))
      (node (ref "R81") (pin "2") (pinfunction "2_2") (pintype "passive"))
      (node (ref "U26") (pin "6") (pinfunction "H_6") (pintype "bidirectional"))
    )
    (net (code "366") (name "~{MOT1_HW_5}") (class "Default")
      (node (ref "CN9") (pin "1.2") (pinfunction "HW_1.2") (pintype "bidirectional"))
      (node (ref "CN9") (pin "2.4") (pinfunction "HW_2.4") (pintype "bidirectional"))
      (node (ref "R82") (pin "2") (pinfunction "2_2") (pintype "passive"))
      (node (ref "U26") (pin "4") (pinfunction "F_4") (pintype "bidirectional"))
    )
    (net (code "367") (name "~{MOT1_OTW}") (class "Default")
      (node (ref "RA2") (pin "A1") (pinfunction "1_A1") (pintype "passive"))
      (node (ref "U9") (pin "105") (pinfunction "IO_L1P_1_105") (pintype "bidirectional"))
    )
    (net (code "368") (name "~{MOT1_RESET_A}") (class "Default")
      (node (ref "RA2") (pin "D1") (pinfunction "1_D1") (pintype "passive"))
      (node (ref "U9") (pin "101") (pinfunction "IO_L32N_1_101") (pintype "bidirectional"))
    )
    (net (code "369") (name "~{MOT1_RESET_B}") (class "Default")
      (node (ref "RA3") (pin "B1") (pinfunction "1_B1") (pintype "passive"))
      (node (ref "U9") (pin "99") (pinfunction "IO_L33N_1_99") (pintype "bidirectional"))
    )
    (net (code "370") (name "~{MOT1_RESET_C}") (class "Default")
      (node (ref "RA3") (pin "C1") (pinfunction "1_C1") (pintype "passive"))
      (node (ref "U9") (pin "98") (pinfunction "IO_L34P_1_98") (pintype "bidirectional"))
    )
    (net (code "371") (name "~{MOT2_FAULT}") (class "Default")
      (node (ref "RA4") (pin "B1") (pinfunction "1_B1") (pintype "passive"))
      (node (ref "U9") (pin "82") (pinfunction "IO_L45N_1_82") (pintype "bidirectional"))
    )
    (net (code "372") (name "~{MOT2_HU_5}") (class "Default")
      (node (ref "CN11") (pin "1.3") (pinfunction "HU_1.3") (pintype "bidirectional"))
      (node (ref "CN11") (pin "2.2") (pinfunction "HU_2.2") (pintype "bidirectional"))
      (node (ref "R85") (pin "2") (pinfunction "2_2") (pintype "passive"))
      (node (ref "U27") (pin "13") (pinfunction "C_13") (pintype "bidirectional"))
    )
    (net (code "373") (name "~{MOT2_HV_5}") (class "Default")
      (node (ref "CN11") (pin "1.4") (pinfunction "HV_1.4") (pintype "bidirectional"))
      (node (ref "CN11") (pin "2.3") (pinfunction "HV_2.3") (pintype "bidirectional"))
      (node (ref "R86") (pin "2") (pinfunction "2_2") (pintype "passive"))
      (node (ref "U27") (pin "12") (pinfunction "B_12") (pintype "bidirectional"))
    )
    (net (code "374") (name "~{MOT2_HW_5}") (class "Default")
      (node (ref "CN11") (pin "1.2") (pinfunction "HW_1.2") (pintype "bidirectional"))
      (node (ref "CN11") (pin "2.4") (pinfunction "HW_2.4") (pintype "bidirectional"))
      (node (ref "R87") (pin "2") (pinfunction "2_2") (pintype "passive"))
      (node (ref "U27") (pin "14") (pinfunction "D_14") (pintype "bidirectional"))
    )
    (net (code "375") (name "~{MOT2_OTW}") (class "Default")
      (node (ref "RA4") (pin "A1") (pinfunction "1_A1") (pintype "passive"))
      (node (ref "U9") (pin "83") (pinfunction "IO_L45P_1_83") (pintype "bidirectional"))
    )
    (net (code "376") (name "~{MOT2_RESET_A}") (class "Default")
      (node (ref "RA4") (pin "D1") (pinfunction "1_D1") (pintype "passive"))
      (node (ref "U9") (pin "80") (pinfunction "IO_L46N_1_80") (pintype "bidirectional"))
    )
    (net (code "377") (name "~{MOT2_RESET_B}") (class "Default")
      (node (ref "RA5") (pin "B1") (pinfunction "1_B1") (pintype "passive"))
      (node (ref "U9") (pin "78") (pinfunction "IO_L47N_1_78") (pintype "bidirectional"))
    )
    (net (code "378") (name "~{MOT2_RESET_C}") (class "Default")
      (node (ref "RA5") (pin "C1") (pinfunction "1_C1") (pintype "passive"))
      (node (ref "U9") (pin "75") (pinfunction "IO_L74P_AWAKE_1_75") (pintype "bidirectional"))
    )
    (net (code "379") (name "~{MOT3_4_5_DO}") (class "Default")
      (node (ref "U31") (pin "7") (pinfunction "~{QH}_7") (pintype "bidirectional"))
      (node (ref "U9") (pin "21") (pinfunction "IO_L42N_GCLK24_3_21") (pintype "bidirectional"))
    )
    (net (code "380") (name "~{MOT3_4_5_LATCH}") (class "Default")
      (node (ref "U30") (pin "1") (pinfunction "S/~{L}_1") (pintype "bidirectional"))
      (node (ref "U31") (pin "1") (pinfunction "S/~{L}_1") (pintype "bidirectional"))
      (node (ref "U9") (pin "23") (pinfunction "IO_L41N_GCLK26_3_23") (pintype "bidirectional"))
    )
    (net (code "381") (name "~{MOT3_FAULT}") (class "Default")
      (node (ref "RA6") (pin "B1") (pinfunction "1_B1") (pintype "passive"))
      (node (ref "U9") (pin "33") (pinfunction "IO_L2P_3_33") (pintype "bidirectional"))
    )
    (net (code "382") (name "~{MOT3_HU_5}") (class "Default")
      (node (ref "CN13") (pin "1.3") (pinfunction "HU_1.3") (pintype "bidirectional"))
      (node (ref "CN13") (pin "2.2") (pinfunction "HU_2.2") (pintype "bidirectional"))
      (node (ref "R90") (pin "2") (pinfunction "2_2") (pintype "passive"))
      (node (ref "U30") (pin "5") (pinfunction "G_5") (pintype "bidirectional"))
    )
    (net (code "383") (name "~{MOT3_HV_5}") (class "Default")
      (node (ref "CN13") (pin "1.4") (pinfunction "HV_1.4") (pintype "bidirectional"))
      (node (ref "CN13") (pin "2.3") (pinfunction "HV_2.3") (pintype "bidirectional"))
      (node (ref "R91") (pin "2") (pinfunction "2_2") (pintype "passive"))
      (node (ref "U30") (pin "6") (pinfunction "H_6") (pintype "bidirectional"))
    )
    (net (code "384") (name "~{MOT3_HW_5}") (class "Default")
      (node (ref "CN13") (pin "1.2") (pinfunction "HW_1.2") (pintype "bidirectional"))
      (node (ref "CN13") (pin "2.4") (pinfunction "HW_2.4") (pintype "bidirectional"))
      (node (ref "R92") (pin "2") (pinfunction "2_2") (pintype "passive"))
      (node (ref "U30") (pin "4") (pinfunction "F_4") (pintype "bidirectional"))
    )
    (net (code "385") (name "~{MOT3_OTW}") (class "Default")
      (node (ref "RA6") (pin "A1") (pinfunction "1_A1") (pintype "passive"))
      (node (ref "U9") (pin "34") (pinfunction "IO_L1N_VREF_3_34") (pintype "bidirectional"))
    )
    (net (code "386") (name "~{MOT3_RESET_A}") (class "Default")
      (node (ref "RA6") (pin "D1") (pinfunction "1_D1") (pintype "passive"))
      (node (ref "U9") (pin "30") (pinfunction "IO_L36P_3_30") (pintype "bidirectional"))
    )
    (net (code "387") (name "~{MOT3_RESET_B}") (class "Default")
      (node (ref "RA7") (pin "B1") (pinfunction "1_B1") (pintype "passive"))
      (node (ref "U9") (pin "27") (pinfunction "IO_L37P_3_27") (pintype "bidirectional"))
    )
    (net (code "388") (name "~{MOT3_RESET_C}") (class "Default")
      (node (ref "RA7") (pin "C1") (pinfunction "1_C1") (pintype "passive"))
      (node (ref "U9") (pin "26") (pinfunction "IO_L37N_3_26") (pintype "bidirectional"))
    )
    (net (code "389") (name "~{MOT4_FAULT}") (class "Default")
      (node (ref "RA8") (pin "B1") (pinfunction "1_B1") (pintype "passive"))
      (node (ref "U9") (pin "10") (pinfunction "IO_L50P_3_10") (pintype "bidirectional"))
    )
    (net (code "390") (name "~{MOT4_HU_5}") (class "Default")
      (node (ref "CN15") (pin "1.3") (pinfunction "HU_1.3") (pintype "bidirectional"))
      (node (ref "CN15") (pin "2.2") (pinfunction "HU_2.2") (pintype "bidirectional"))
      (node (ref "R95") (pin "2") (pinfunction "2_2") (pintype "passive"))
      (node (ref "U31") (pin "12") (pinfunction "B_12") (pintype "bidirectional"))
    )
    (net (code "391") (name "~{MOT4_HV_5}") (class "Default")
      (node (ref "CN15") (pin "1.4") (pinfunction "HV_1.4") (pintype "bidirectional"))
      (node (ref "CN15") (pin "2.3") (pinfunction "HV_2.3") (pintype "bidirectional"))
      (node (ref "R96") (pin "2") (pinfunction "2_2") (pintype "passive"))
      (node (ref "U31") (pin "11") (pinfunction "A_11") (pintype "bidirectional"))
    )
    (net (code "392") (name "~{MOT4_HW_5}") (class "Default")
      (node (ref "CN15") (pin "1.2") (pinfunction "HW_1.2") (pintype "bidirectional"))
      (node (ref "CN15") (pin "2.4") (pinfunction "HW_2.4") (pintype "bidirectional"))
      (node (ref "R97") (pin "2") (pinfunction "2_2") (pintype "passive"))
      (node (ref "U31") (pin "13") (pinfunction "C_13") (pintype "bidirectional"))
    )
    (net (code "393") (name "~{MOT4_OTW}") (class "Default")
      (node (ref "RA8") (pin "A1") (pinfunction "1_A1") (pintype "passive"))
      (node (ref "U9") (pin "11") (pinfunction "IO_L49N_3_11") (pintype "bidirectional"))
    )
    (net (code "394") (name "~{MOT4_RESET_A}") (class "Default")
      (node (ref "RA8") (pin "D1") (pinfunction "1_D1") (pintype "passive"))
      (node (ref "U9") (pin "8") (pinfunction "IO_L51P_3_8") (pintype "bidirectional"))
    )
    (net (code "395") (name "~{MOT4_RESET_B}") (class "Default")
      (node (ref "RA9") (pin "B1") (pinfunction "1_B1") (pintype "passive"))
      (node (ref "U9") (pin "6") (pinfunction "IO_L52P_3_6") (pintype "bidirectional"))
    )
    (net (code "396") (name "~{MOT4_RESET_C}") (class "Default")
      (node (ref "RA9") (pin "C1") (pinfunction "1_C1") (pintype "passive"))
      (node (ref "U9") (pin "5") (pinfunction "IO_L52N_3_5") (pintype "bidirectional"))
    )
    (net (code "397") (name "~{MOT5_FAULT}") (class "Default")
      (node (ref "RA10") (pin "B1") (pinfunction "1_B1") (pintype "passive"))
      (node (ref "U9") (pin "141") (pinfunction "IO_L2N_0_141") (pintype "bidirectional"))
    )
    (net (code "398") (name "~{MOT5_HU_5}") (class "Default")
      (node (ref "CN17") (pin "6") (pinfunction "6_6") (pintype "passive"))
      (node (ref "R119") (pin "1") (pinfunction "1_1") (pintype "passive"))
      (node (ref "U31") (pin "5") (pinfunction "G_5") (pintype "bidirectional"))
    )
    (net (code "399") (name "~{MOT5_HV_5}") (class "Default")
      (node (ref "CN17") (pin "7") (pinfunction "7_7") (pintype "passive"))
      (node (ref "R120") (pin "1") (pinfunction "1_1") (pintype "passive"))
      (node (ref "U31") (pin "6") (pinfunction "H_6") (pintype "bidirectional"))
    )
    (net (code "400") (name "~{MOT5_HW_5}") (class "Default")
      (node (ref "CN17") (pin "8") (pinfunction "8_8") (pintype "passive"))
      (node (ref "R121") (pin "1") (pinfunction "1_1") (pintype "passive"))
      (node (ref "U31") (pin "14") (pinfunction "D_14") (pintype "bidirectional"))
    )
    (net (code "401") (name "~{MOT5_OTW}") (class "Default")
      (node (ref "RA10") (pin "A1") (pinfunction "1_A1") (pintype "passive"))
      (node (ref "U9") (pin "142") (pinfunction "IO_L2P_0_142") (pintype "bidirectional"))
    )
    (net (code "402") (name "~{MOT5_RESET_A}") (class "Default")
      (node (ref "RA10") (pin "D1") (pinfunction "1_D1") (pintype "passive"))
      (node (ref "U9") (pin "139") (pinfunction "IO_L3N_0_139") (pintype "bidirectional"))
    )
    (net (code "403") (name "~{MOT5_RESET_B}") (class "Default")
      (node (ref "RA11") (pin "B1") (pinfunction "1_B1") (pintype "passive"))
      (node (ref "U9") (pin "137") (pinfunction "IO_L4N_0_137") (pintype "bidirectional"))
    )
    (net (code "404") (name "~{MOT5_RESET_C}") (class "Default")
      (node (ref "RA11") (pin "C1") (pinfunction "1_C1") (pintype "passive"))
      (node (ref "U9") (pin "134") (pinfunction "IO_L34P_GCLK19_0_134") (pintype "bidirectional"))
    )
    (net (code "405") (name "~{SETTING_BOOTLOADER}") (class "Default")
      (node (ref "J1") (pin "2") (pinfunction "2_2") (pintype "passive"))
      (node (ref "U5") (pin "10") (pinfunction "PA04/AD1/GCLK1/USB_VBOF/ABDAC-DATAN0_10") (pintype "bidirectional"))
    )
    (net (code "406") (name "~{SETTING_CHARGER}") (class "Default")
      (node (ref "J1") (pin "4") (pinfunction "4_4") (pintype "passive"))
      (node (ref "U5") (pin "7") (pinfunction "PB01/TC-B0/USART2-RTS_7") (pintype "bidirectional"))
    )
    (net (code "407") (name "~{SETTING_ID0}") (class "Default")
      (node (ref "J1") (pin "6") (pinfunction "6_6") (pintype "passive"))
      (node (ref "U5") (pin "11") (pinfunction "PA05/AD2/INT0/USART1-DCD/ABDAC-DATA1_11") (pintype "bidirectional"))
    )
    (net (code "408") (name "~{SETTING_ID1}") (class "Default")
      (node (ref "J1") (pin "8") (pinfunction "8_8") (pintype "passive"))
      (node (ref "U5") (pin "12") (pinfunction "PA06/AD3/INT1/USART1-DSR/ABDAC-DATAN1_12") (pintype "bidirectional"))
    )
    (net (code "409") (name "~{SETTING_ID2}") (class "Default")
      (node (ref "J1") (pin "10") (pinfunction "10_10") (pintype "passive"))
      (node (ref "U5") (pin "13") (pinfunction "PA07/AD4/PWM0/USART1-DTR/SSC-RXFRM_13") (pintype "bidirectional"))
    )
    (net (code "410") (name "~{SW1}") (class "Default")
      (node (ref "SW3") (pin "B2") (pinfunction "B2_B2") (pintype "passive"))
      (node (ref "U5") (pin "16") (pinfunction "PA31/AD7/PWM6_16") (pintype "bidirectional"))
    )
    (net (code "411") (name "~{XBEE_CTS}") (class "Default")
      (node (ref "CN7") (pin "12") (pinfunction "~{CTS}/DIO7_12") (pintype "bidirectional"))
      (node (ref "U9") (pin "115") (pinfunction "IO_L65P_SCP3_0_115") (pintype "bidirectional"))
    )
    (net (code "412") (name "~{XBEE_RST}") (class "Default")
      (node (ref "CN7") (pin "5") (pinfunction "~{RESET}_5") (pintype "bidirectional"))
      (node (ref "R53") (pin "2") (pinfunction "2_2") (pintype "passive"))
      (node (ref "U9") (pin "123") (pinfunction "IO_L37N_GCLK12_0_123") (pintype "bidirectional"))
    )
  )
)
